# Z80_BMO_V1_2.net
KiCad netlist of a schematic drawn in EAGLE
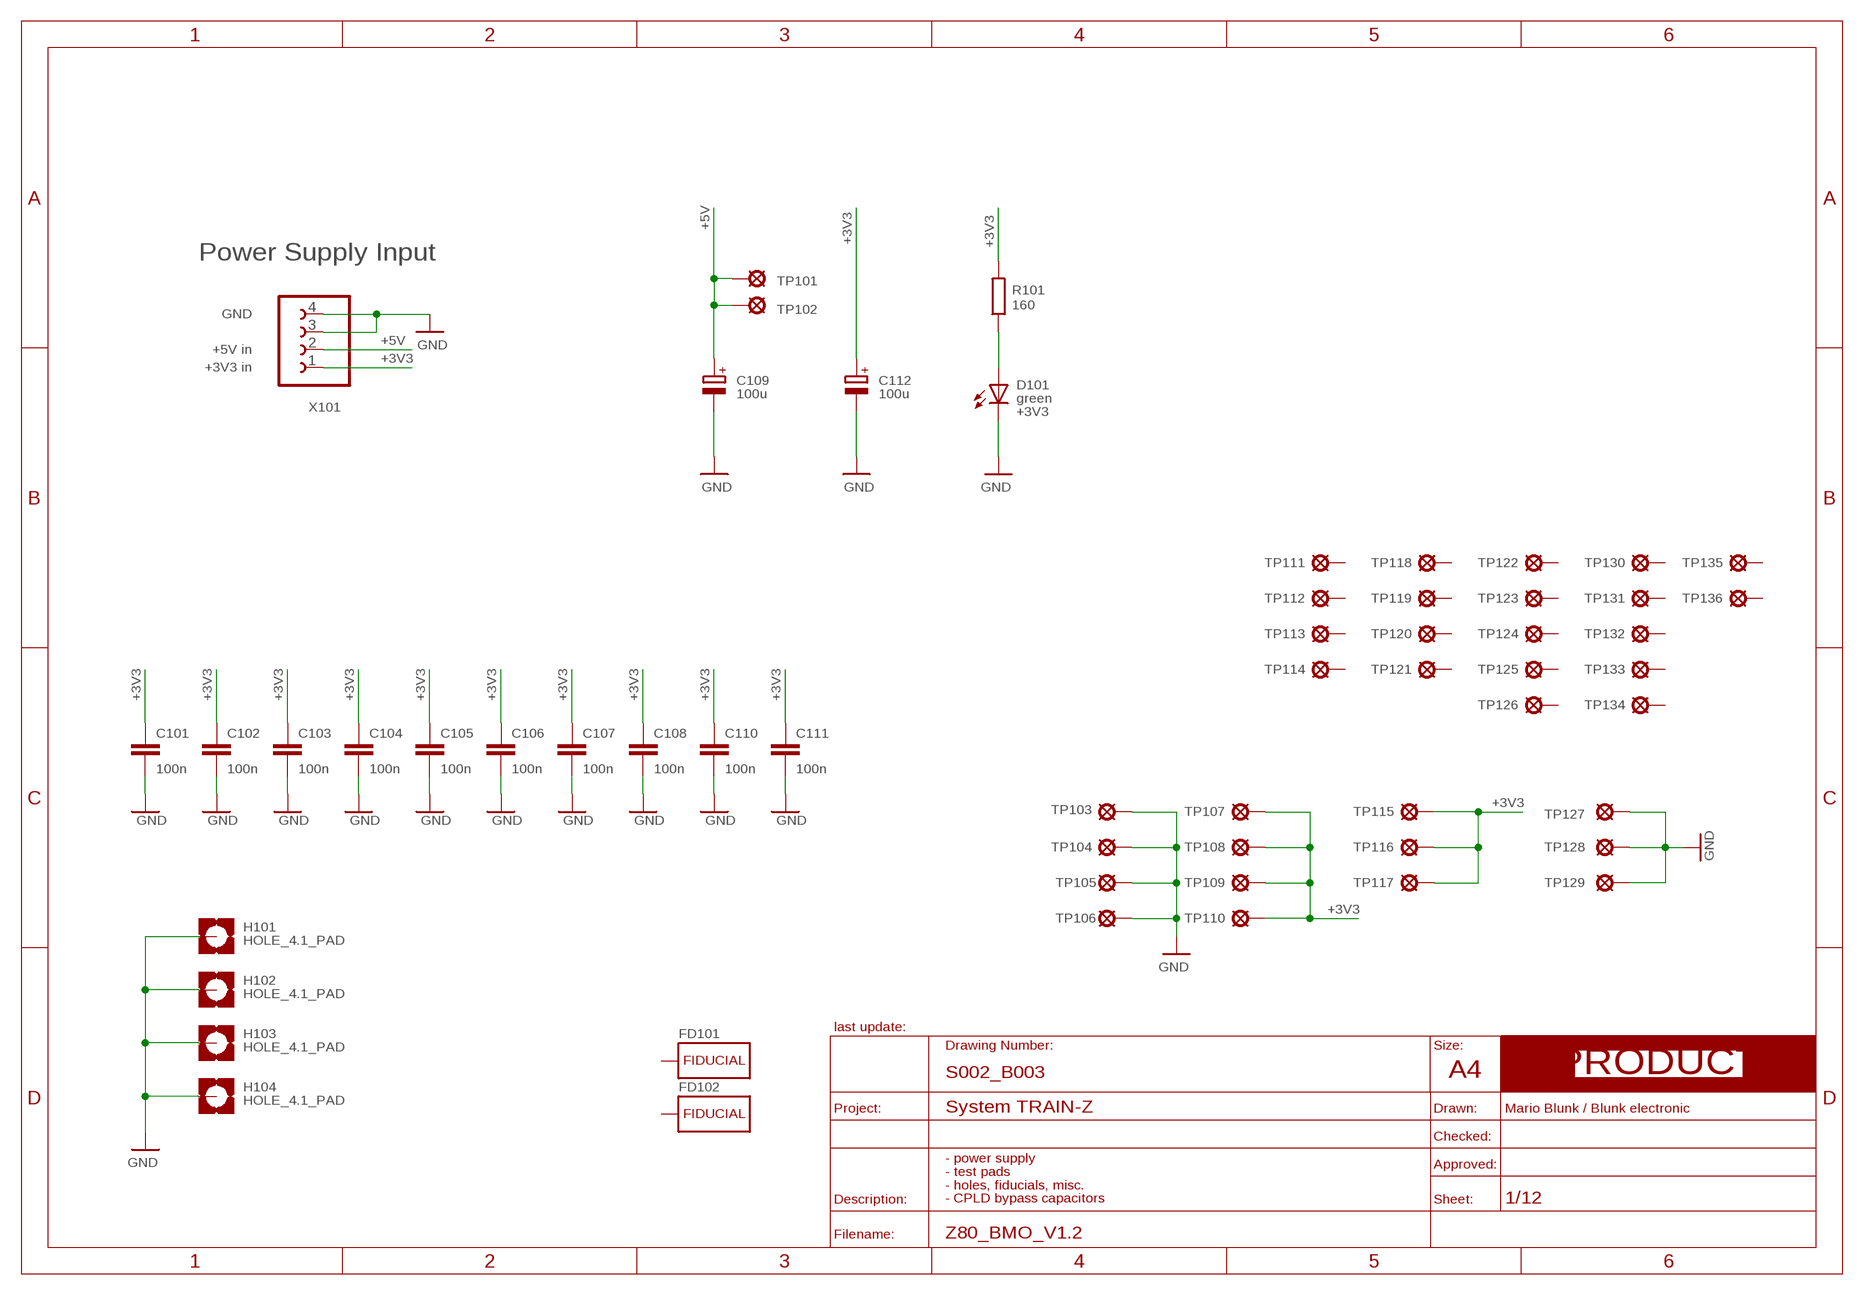
[diagram p0: schematic, sheet 1]
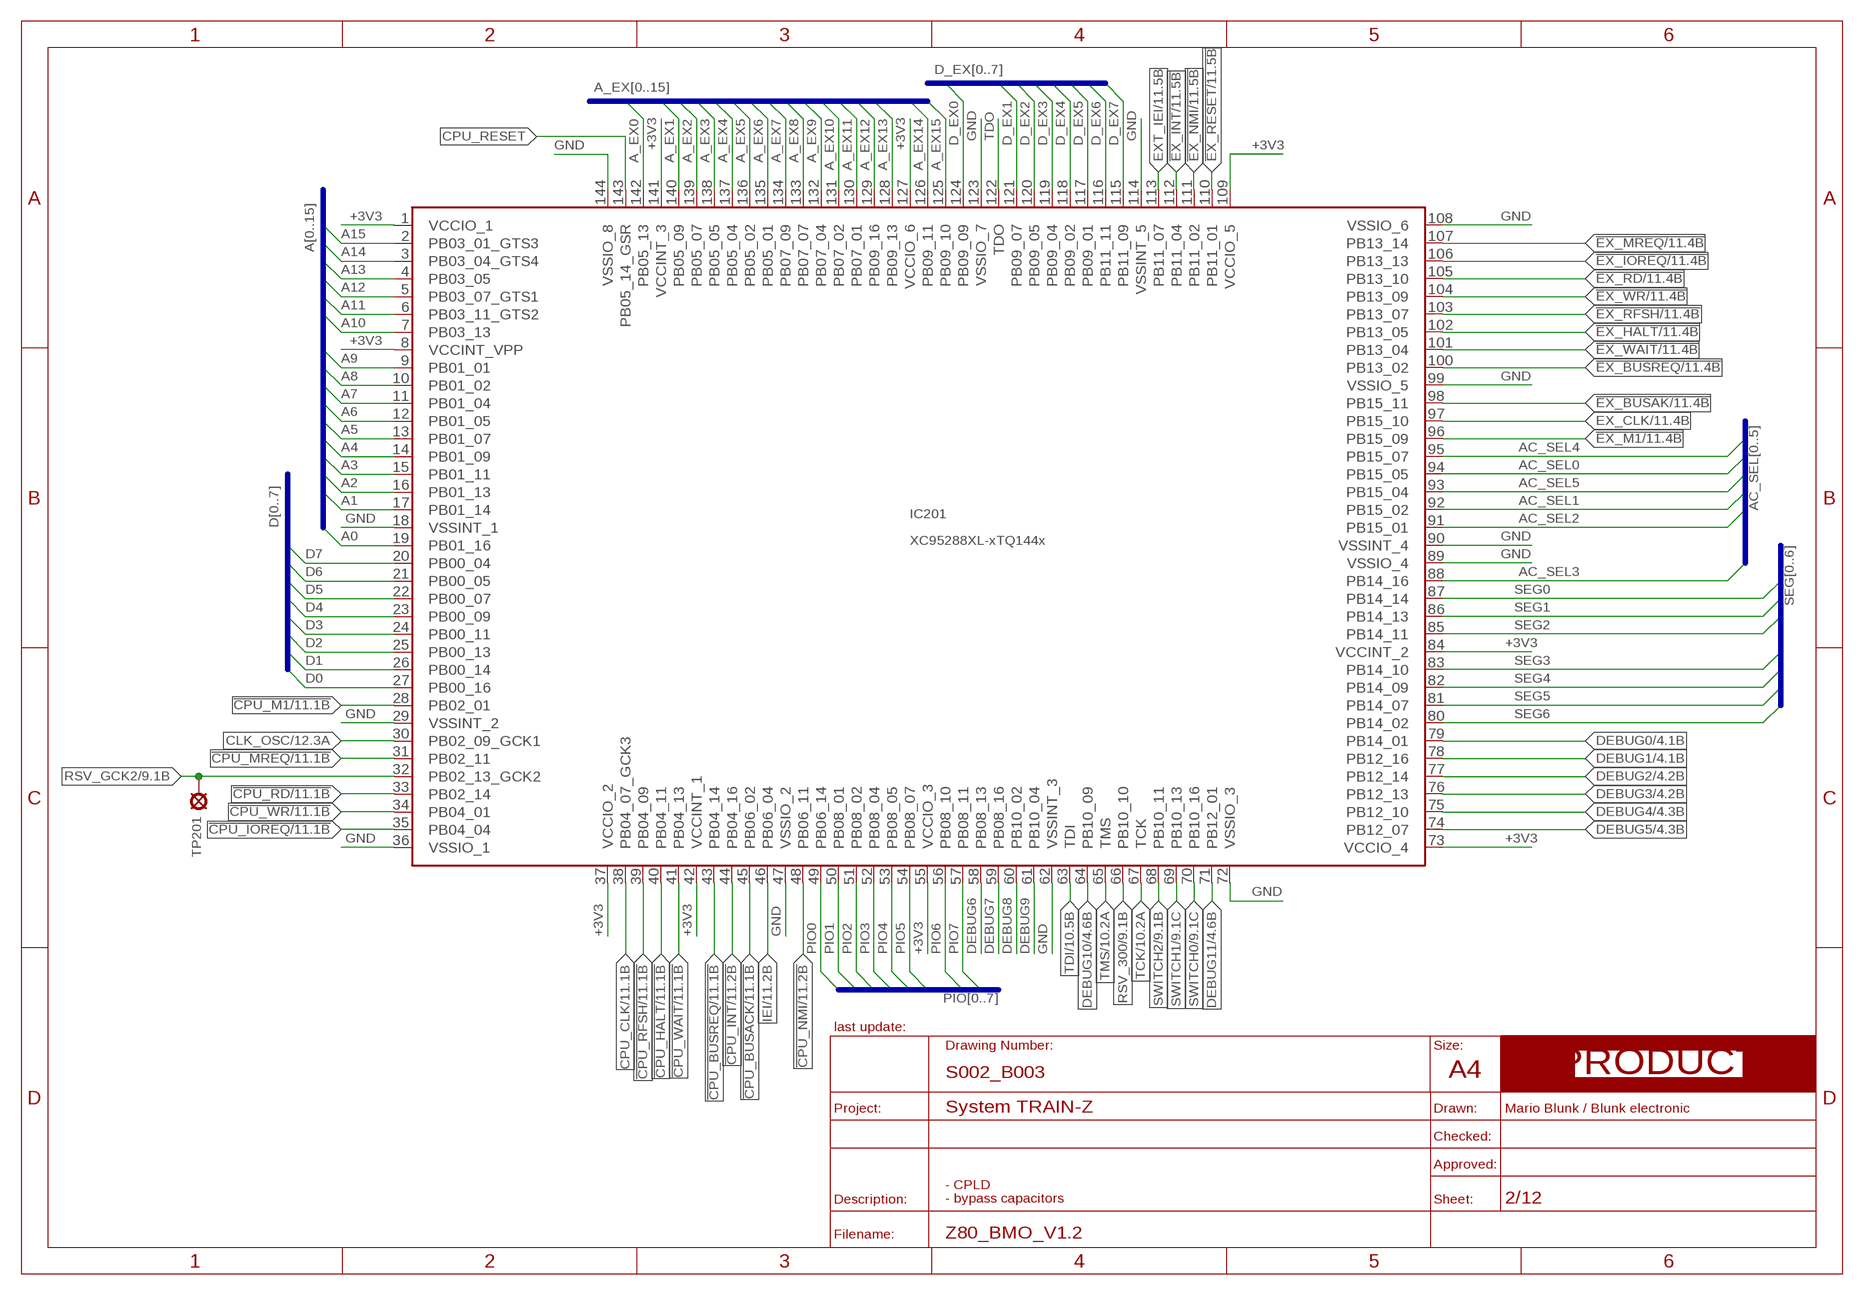
[diagram p1: schematic, sheet 2]
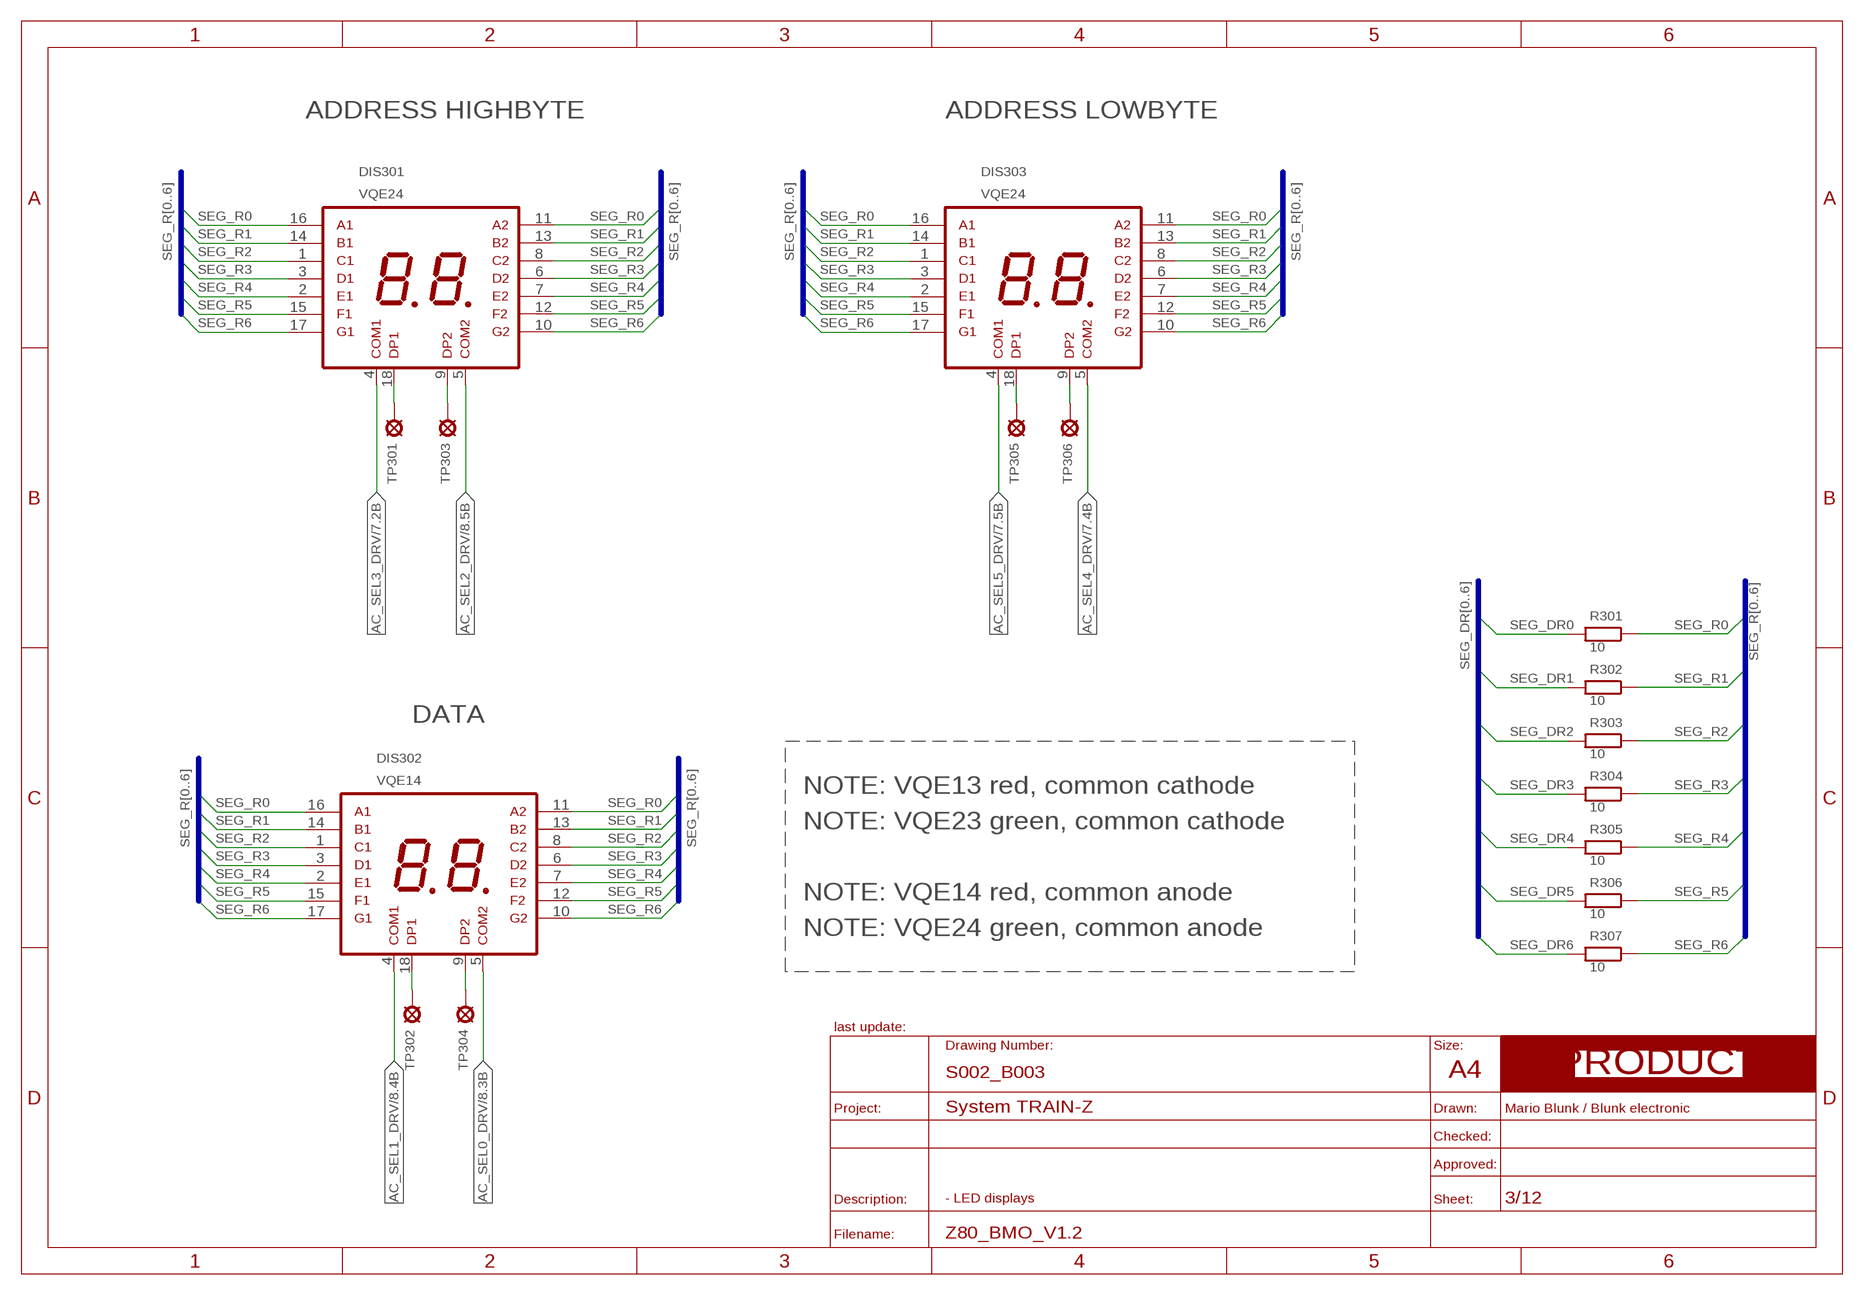
[diagram p2: schematic, sheet 3]
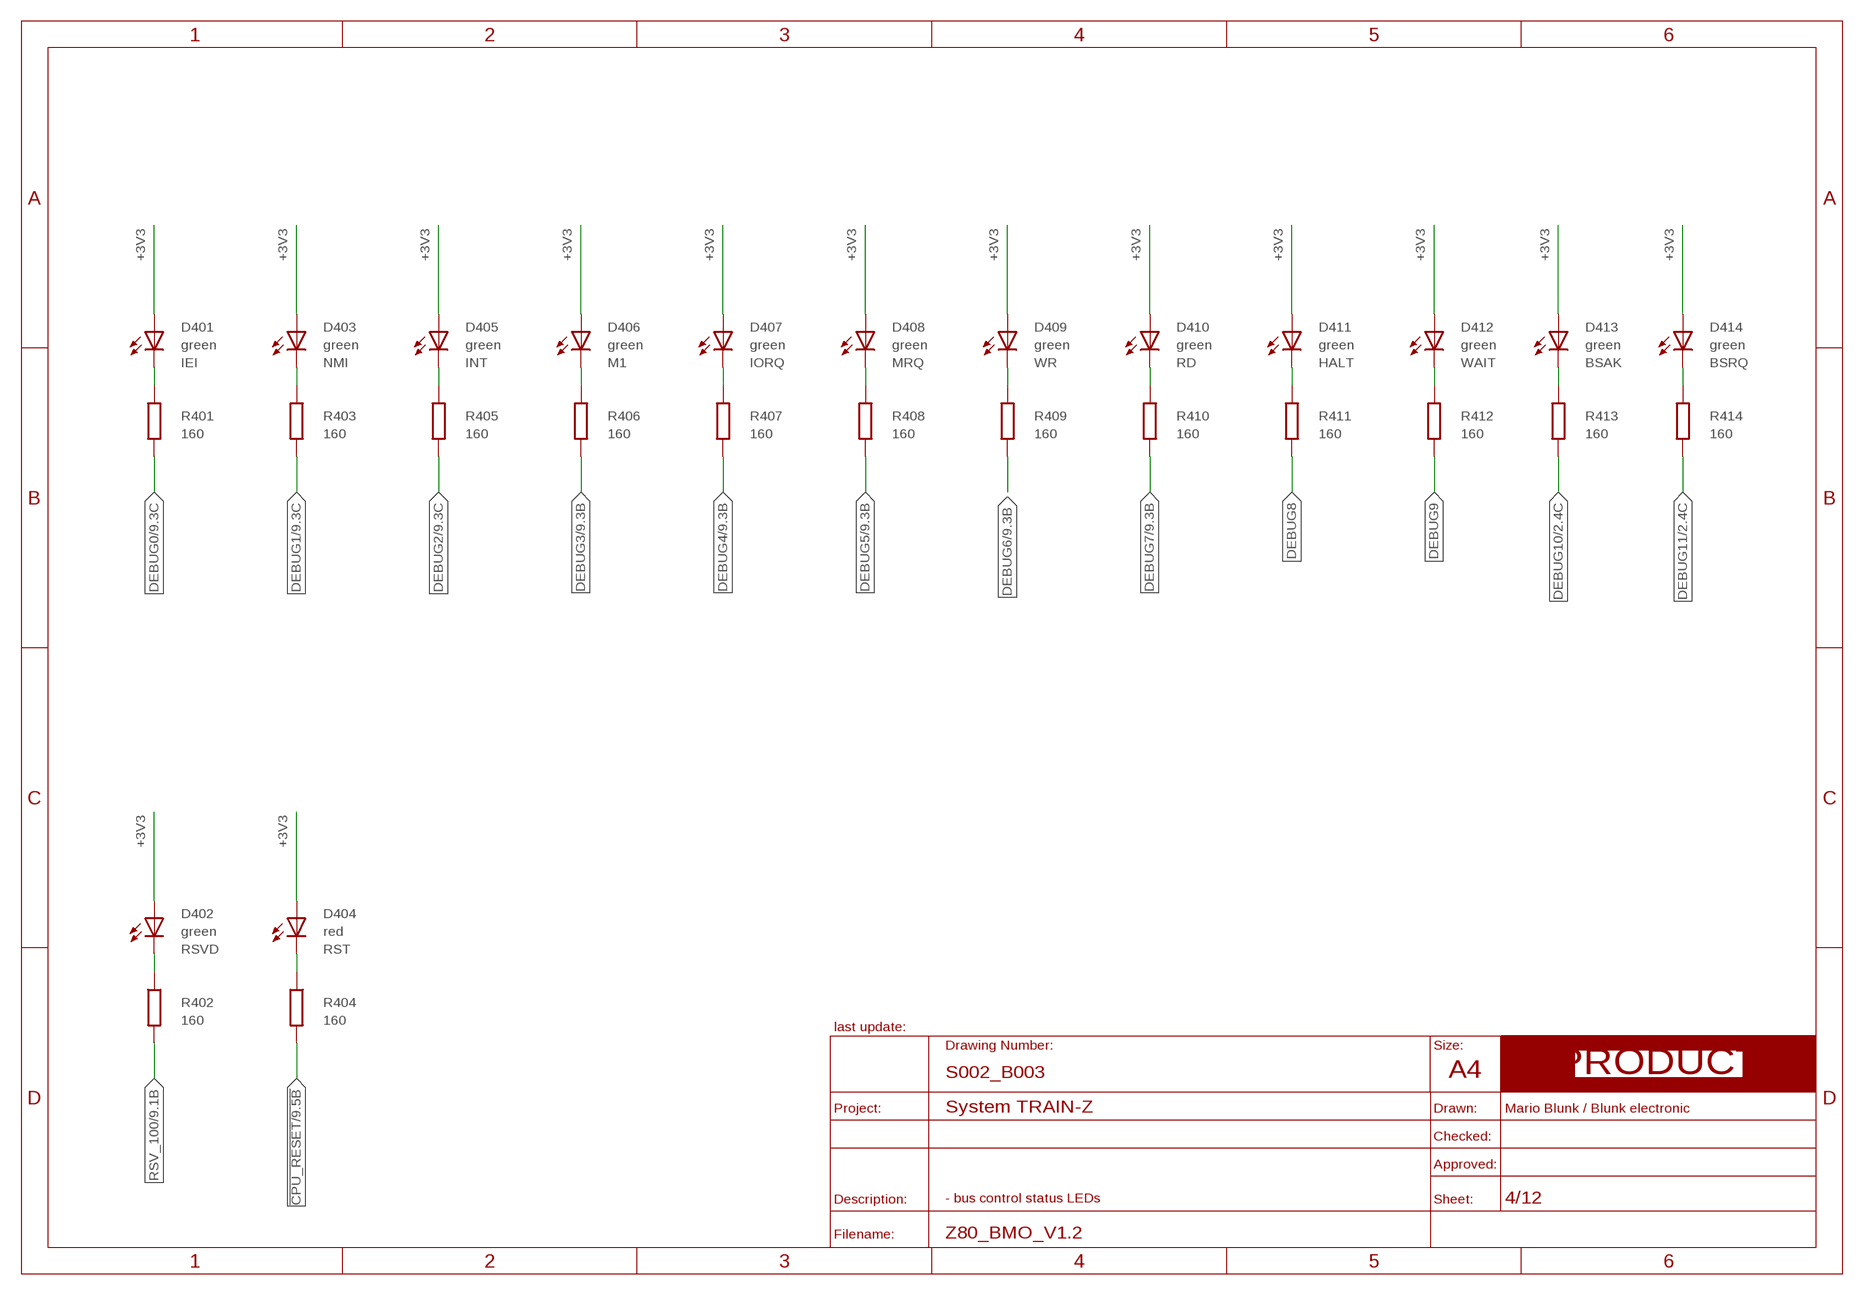
[diagram p3: schematic, sheet 4]
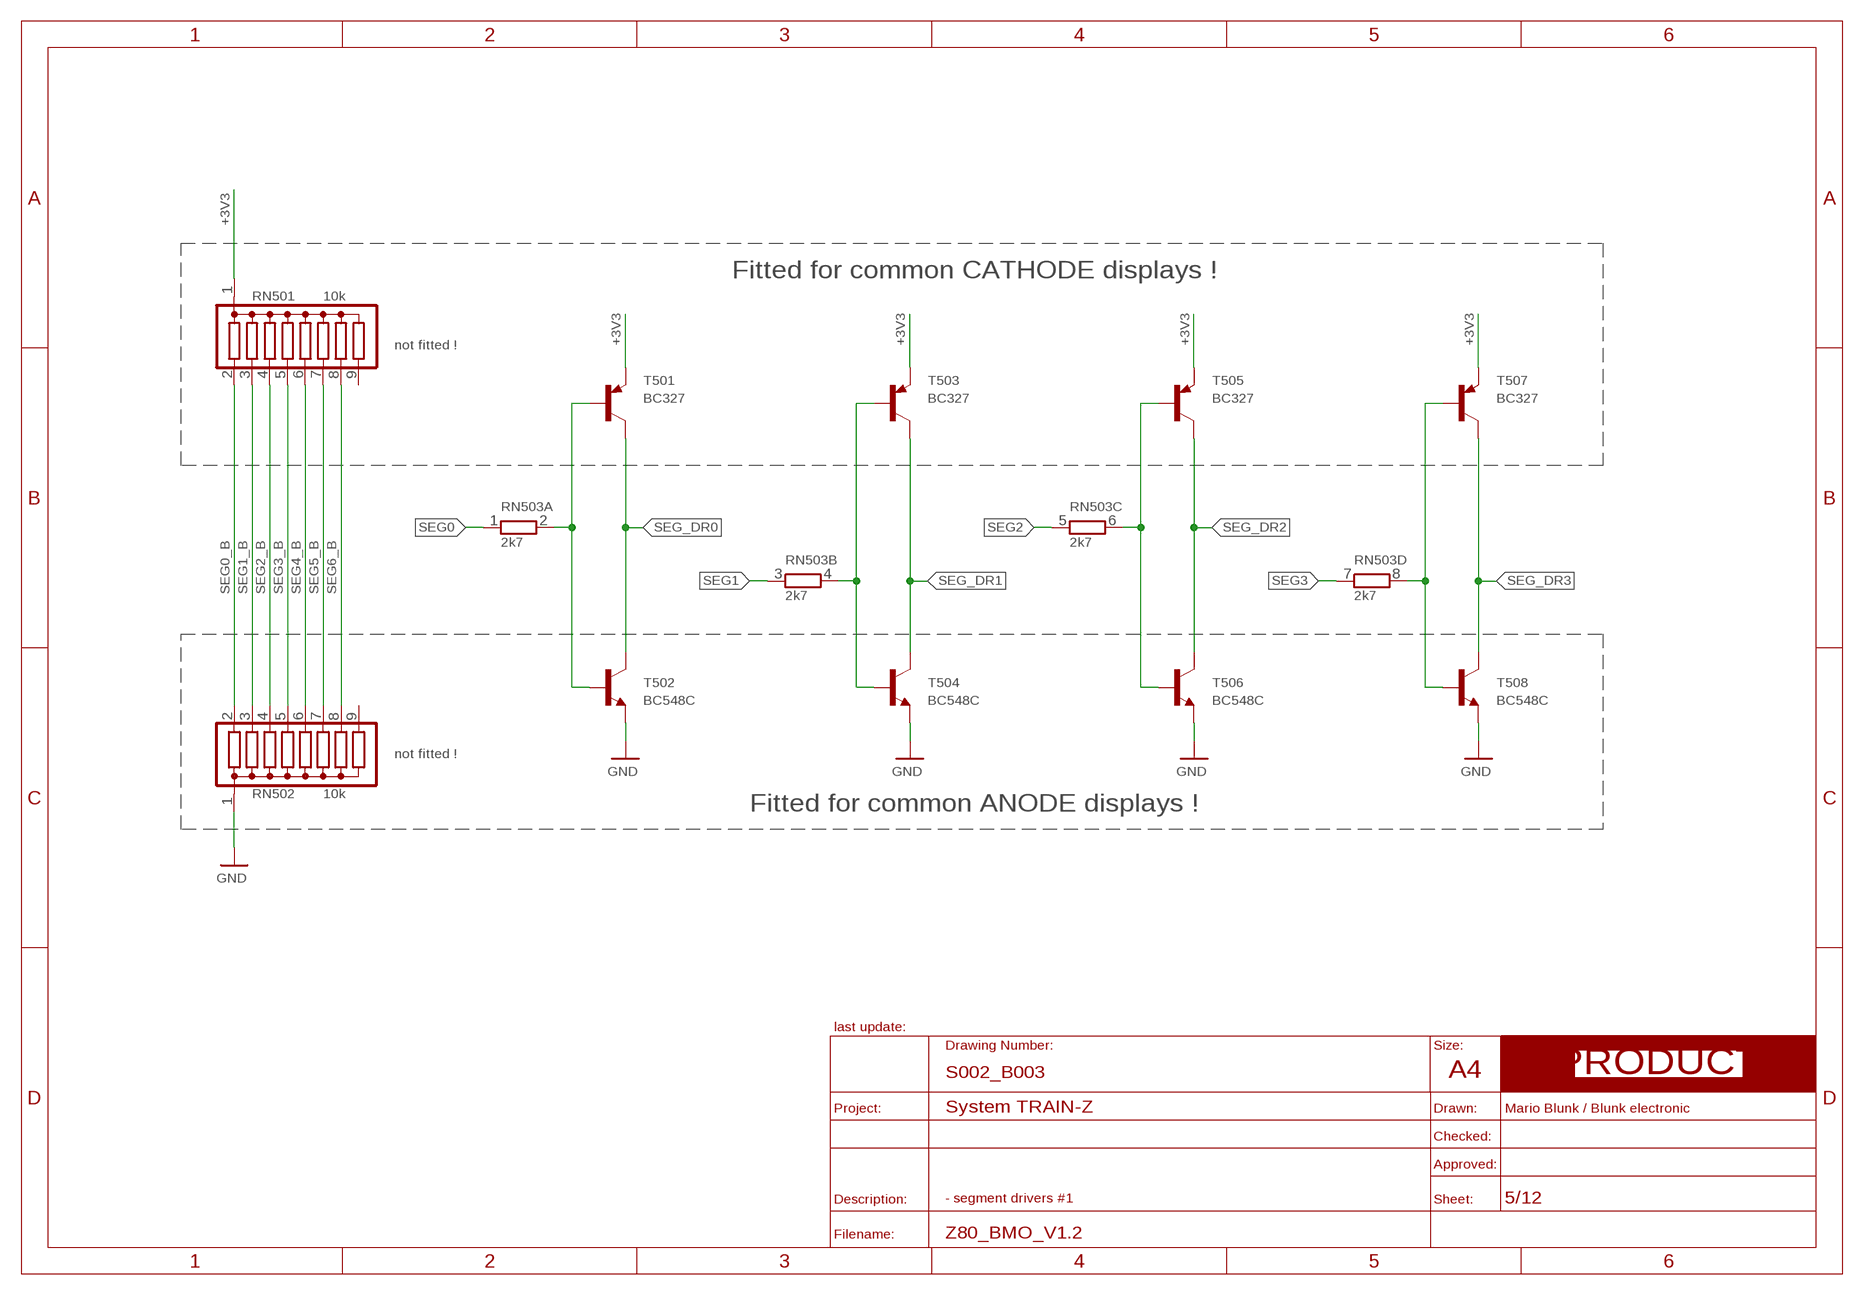
[diagram p4: schematic, sheet 5]
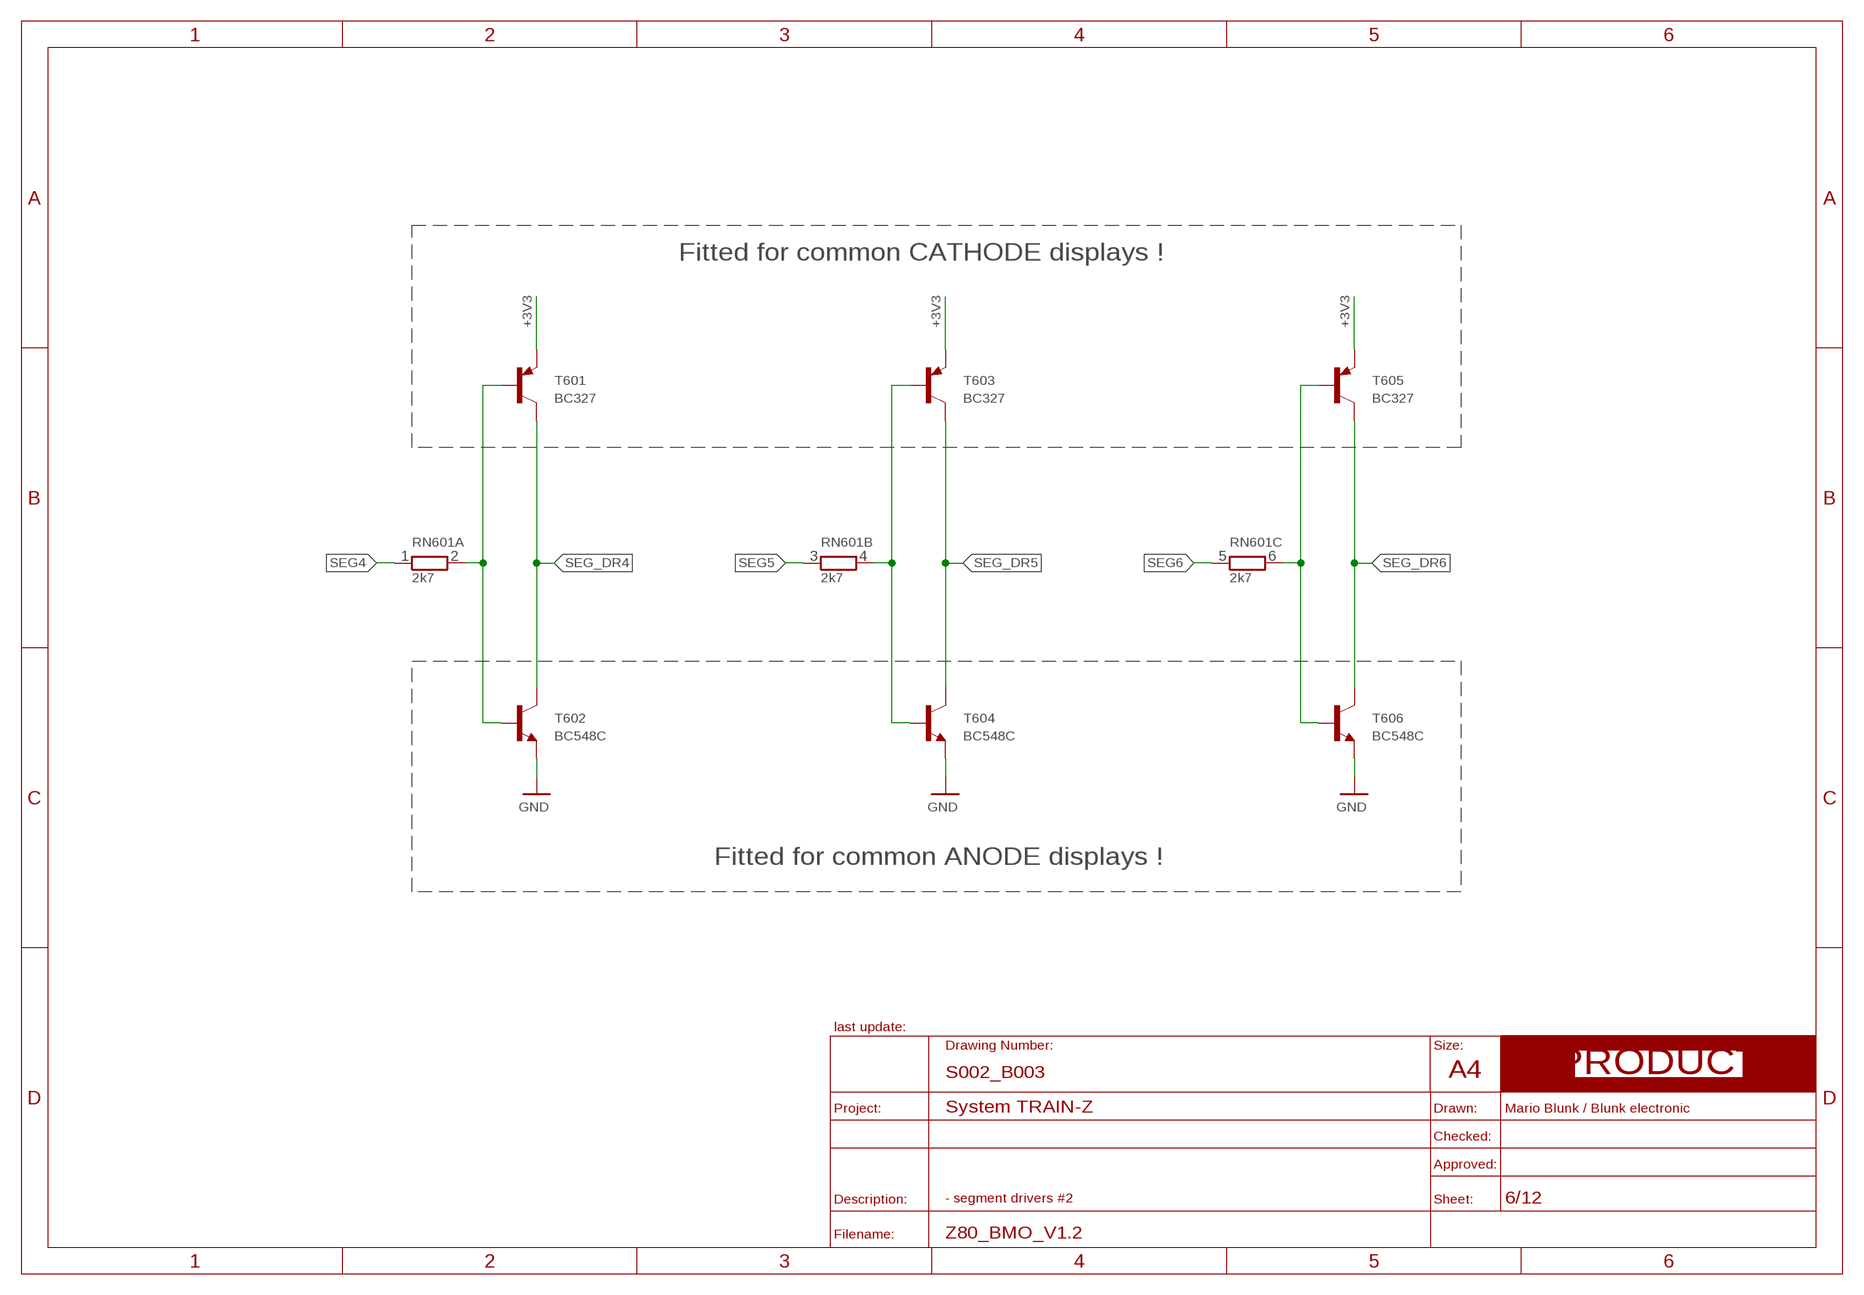
[diagram p5: schematic, sheet 6]
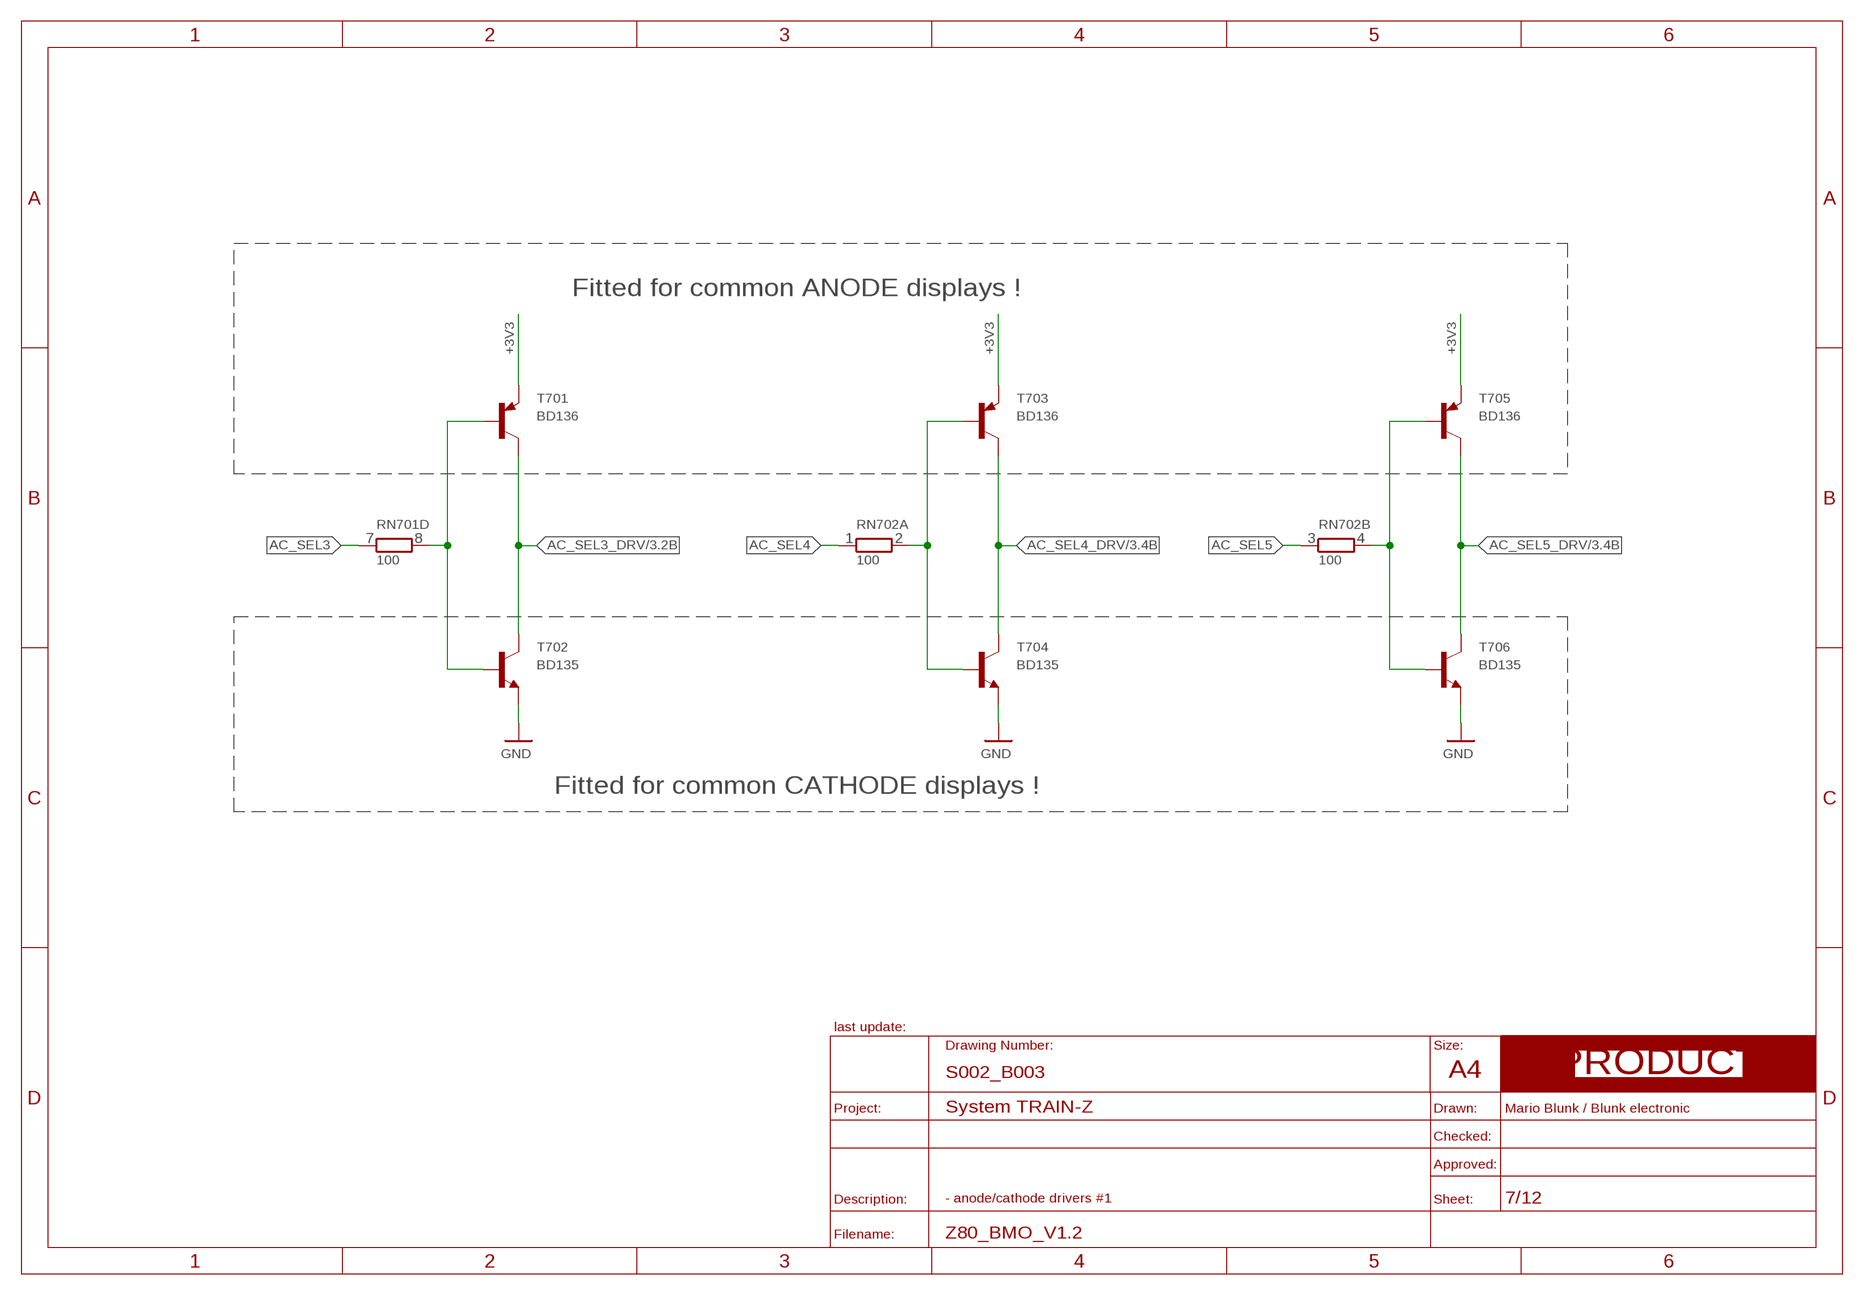
[diagram p6: schematic, sheet 7]
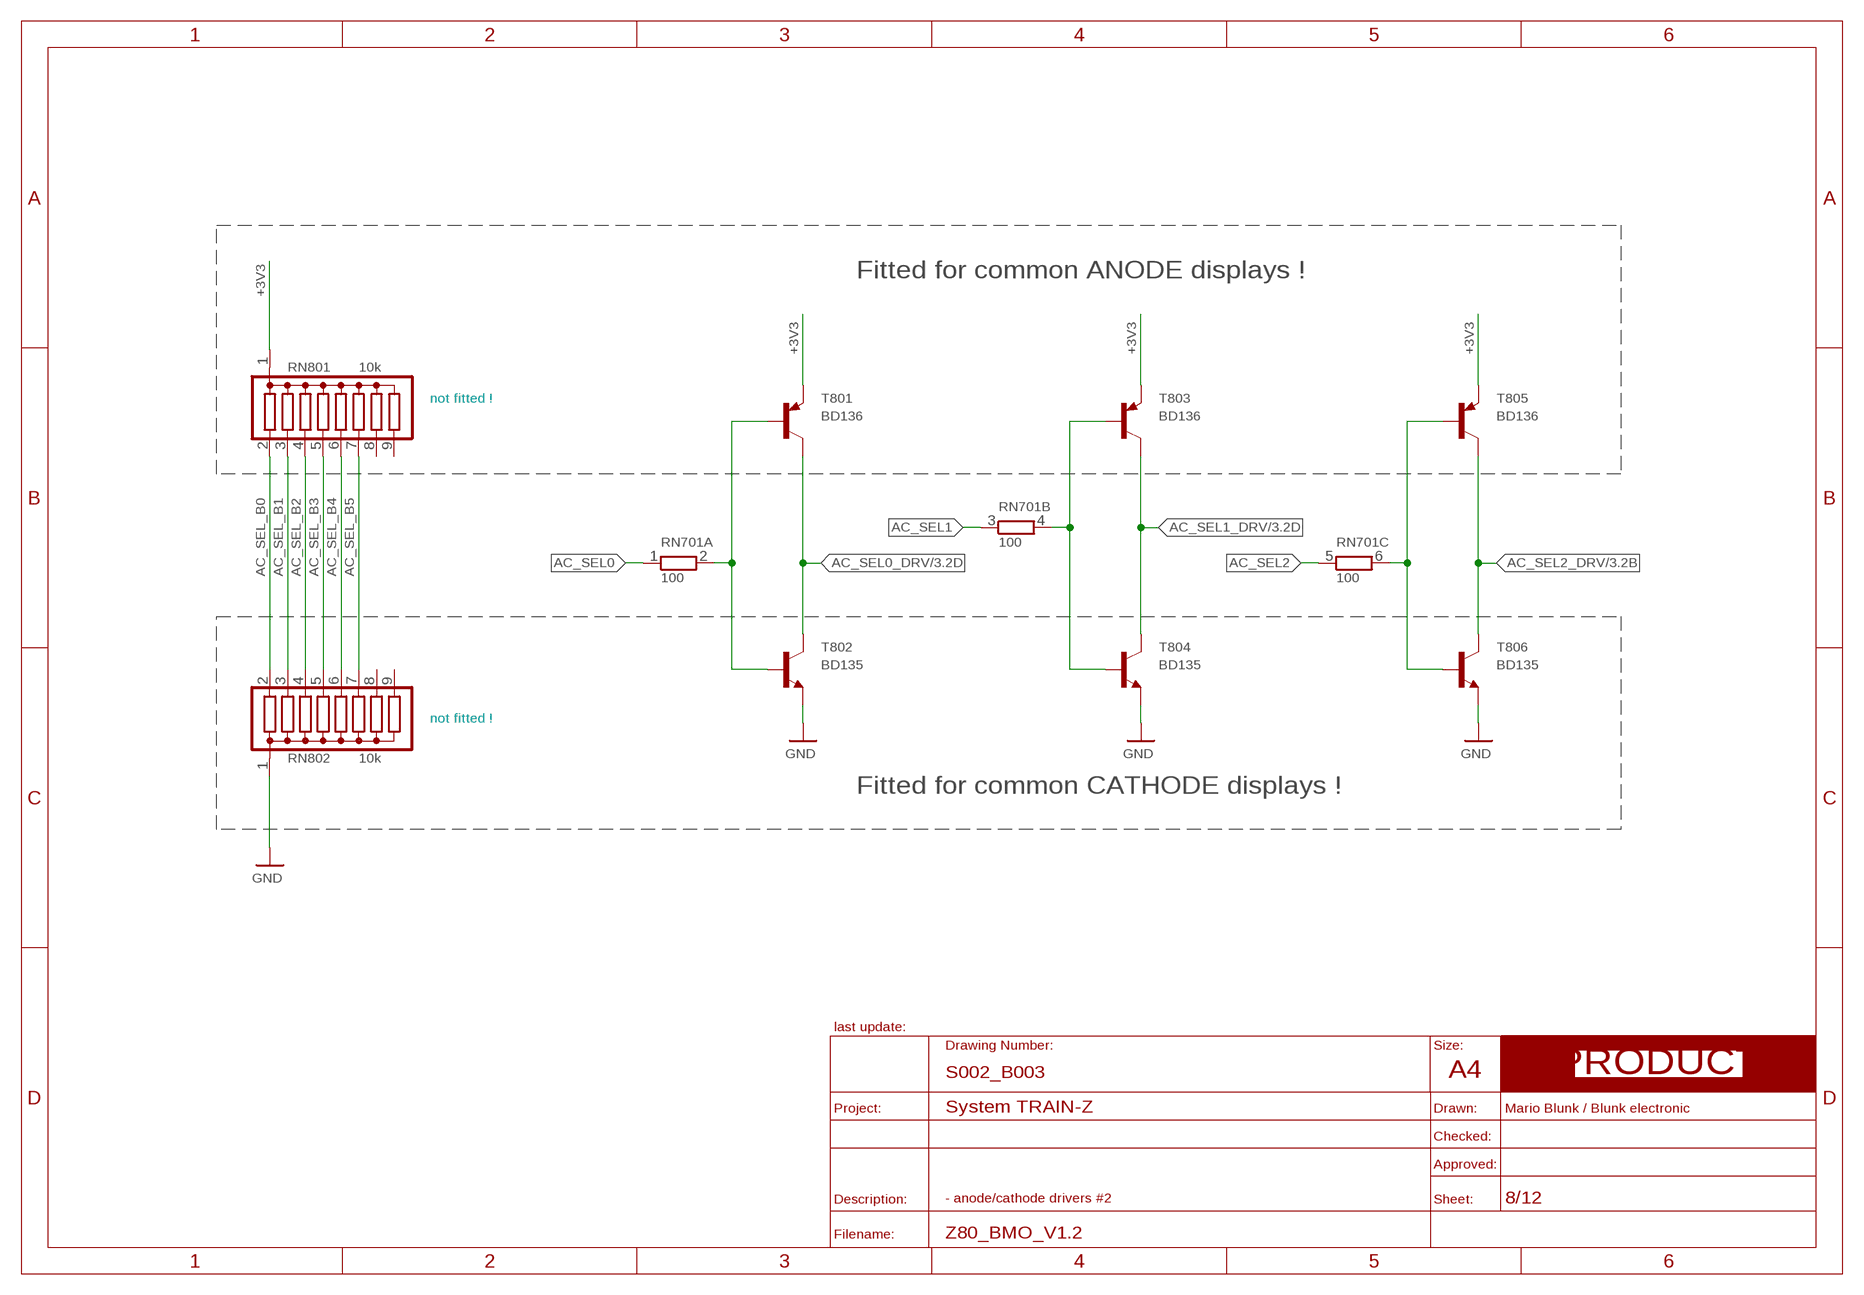
[diagram p7: schematic, sheet 8]
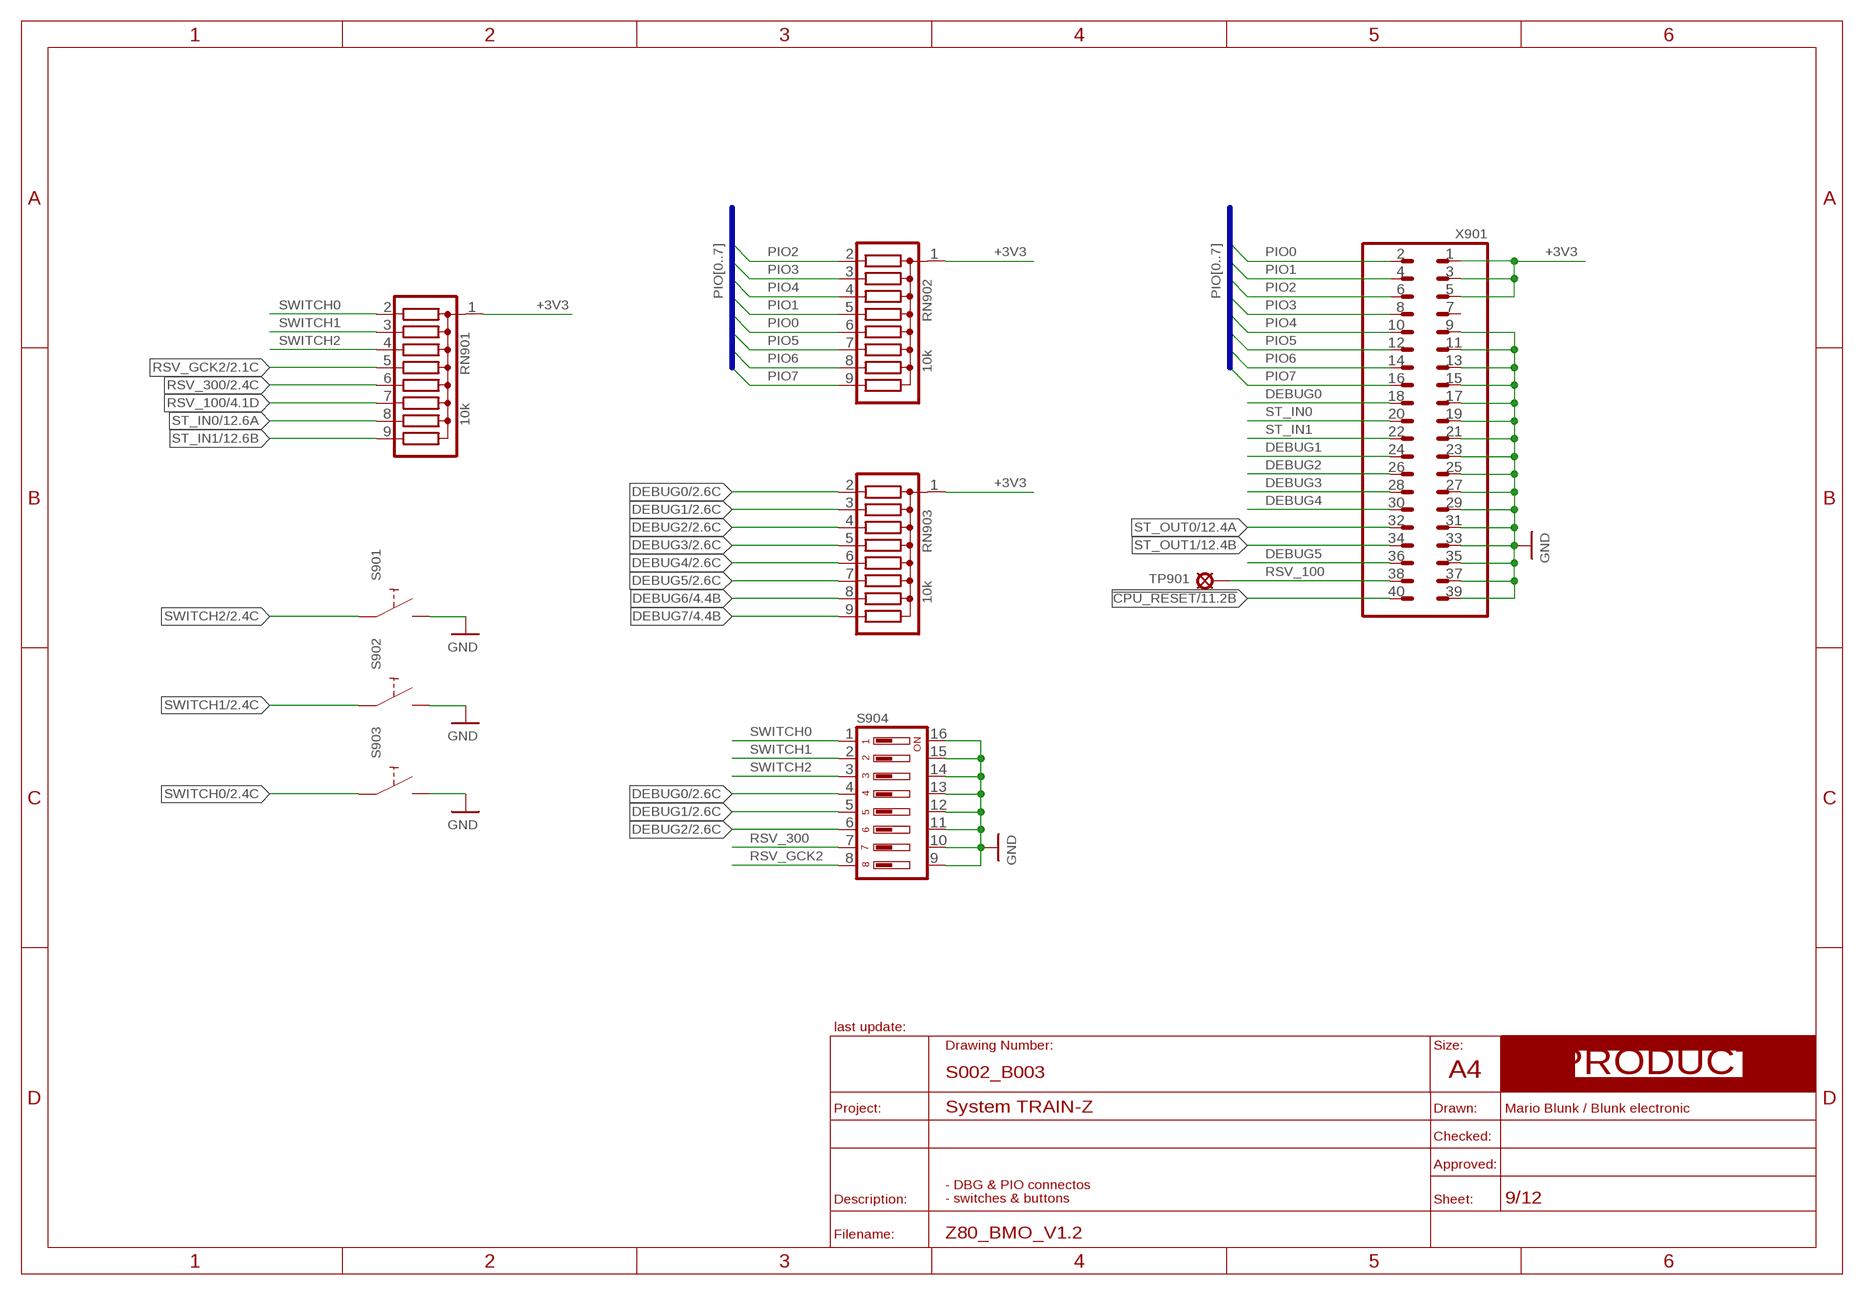
[diagram p8: schematic, sheet 9]
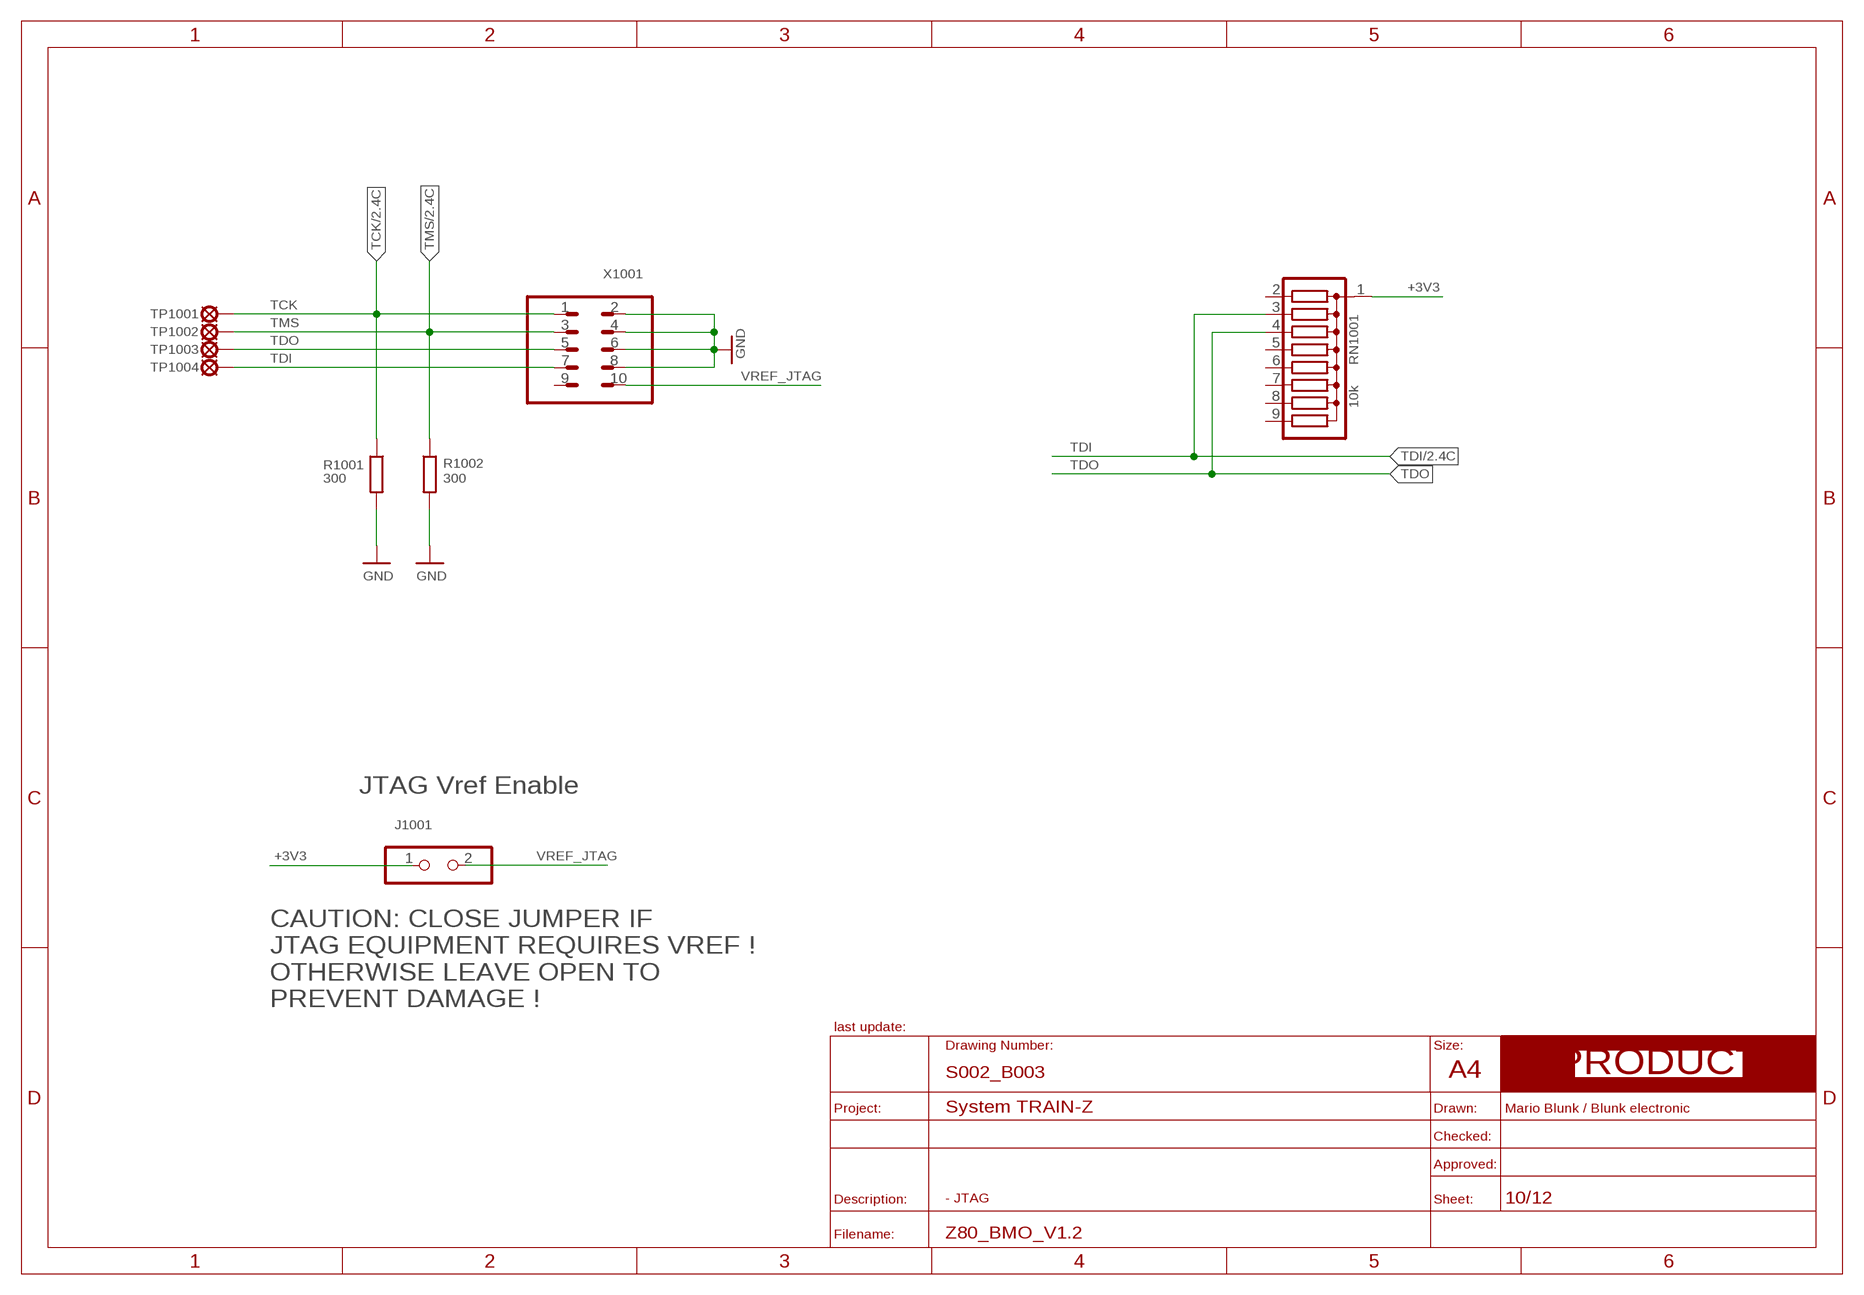
[diagram p9: schematic, sheet 10]
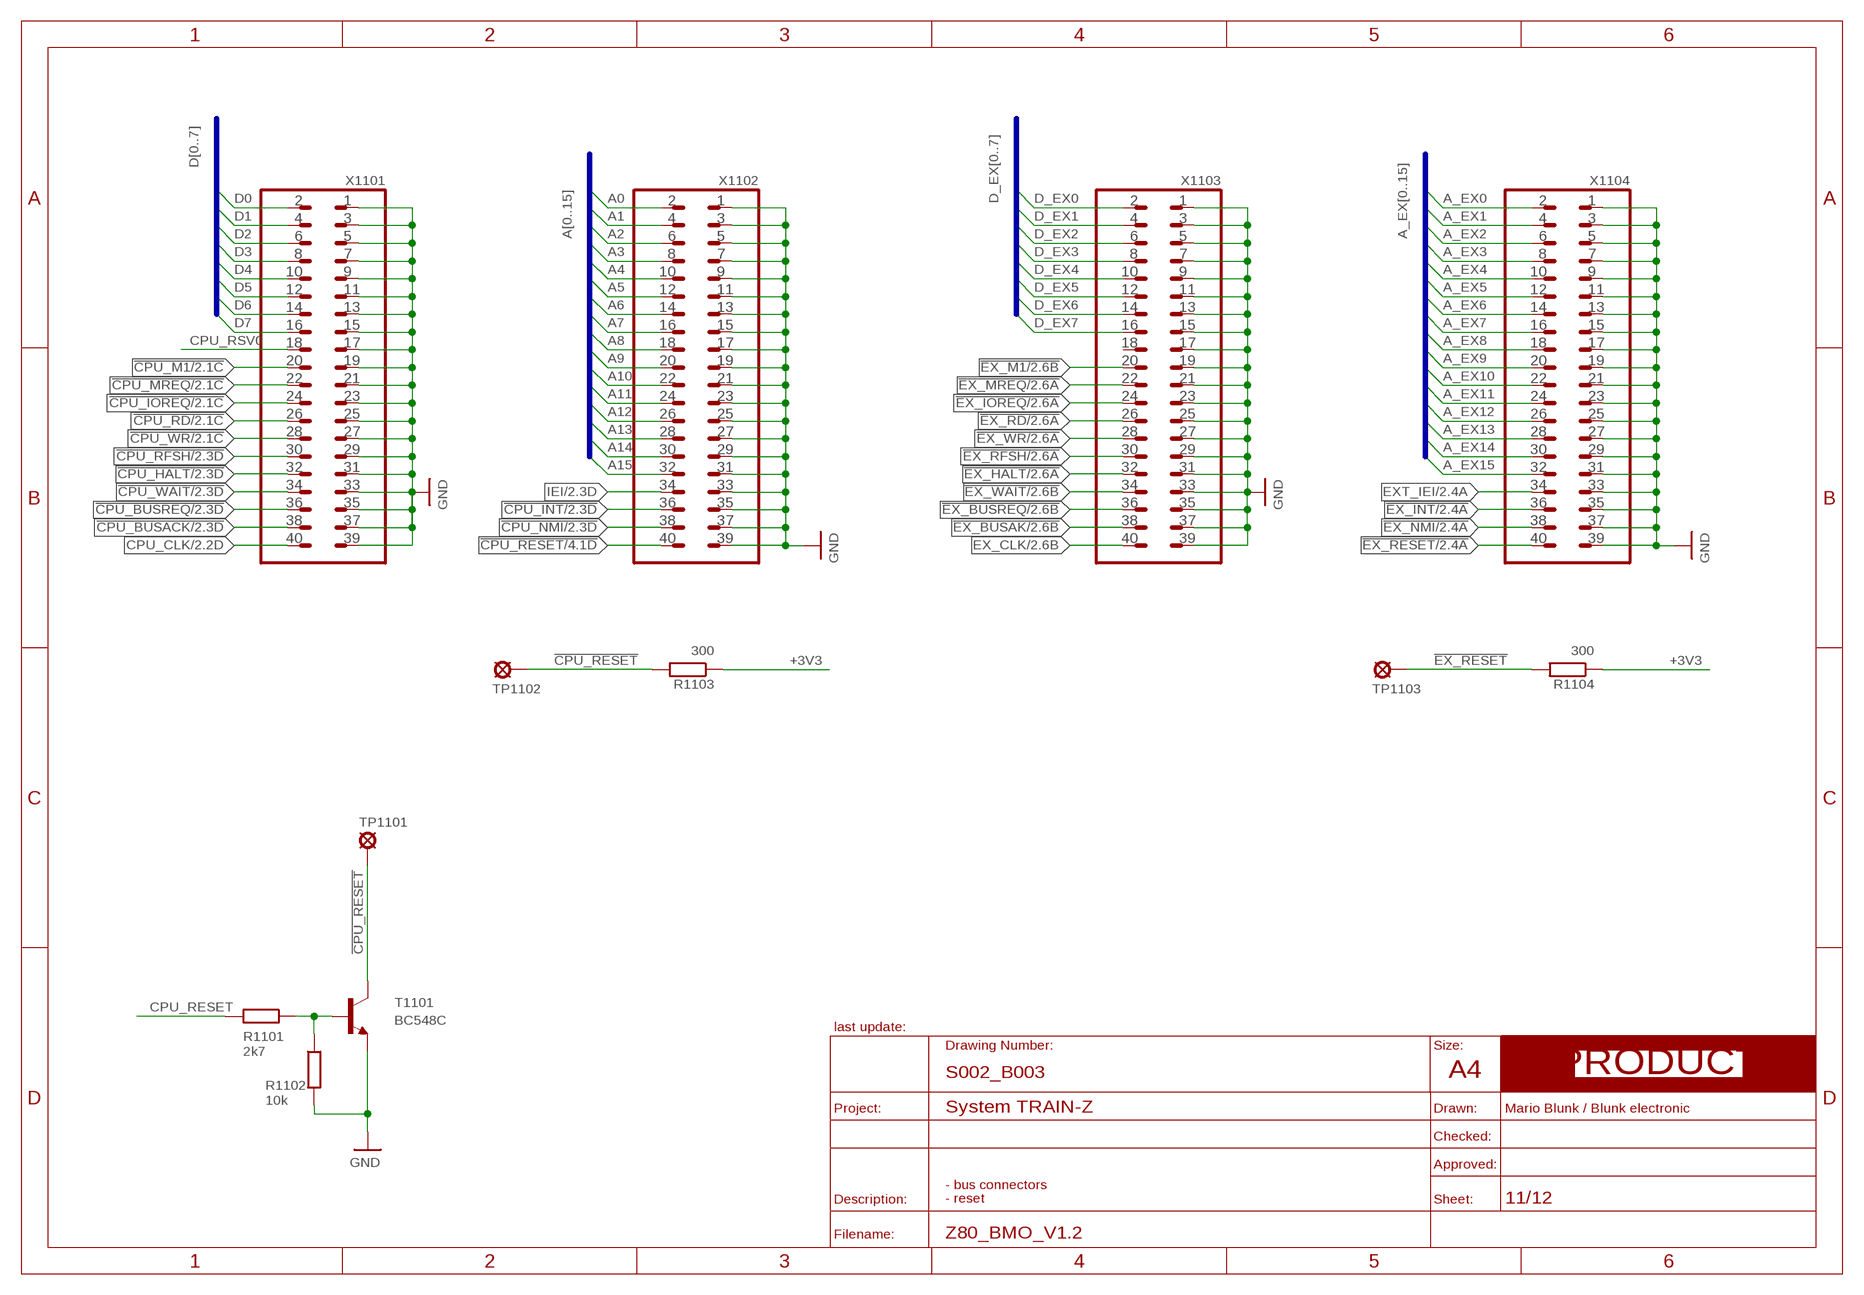
[diagram p10: schematic, sheet 11]
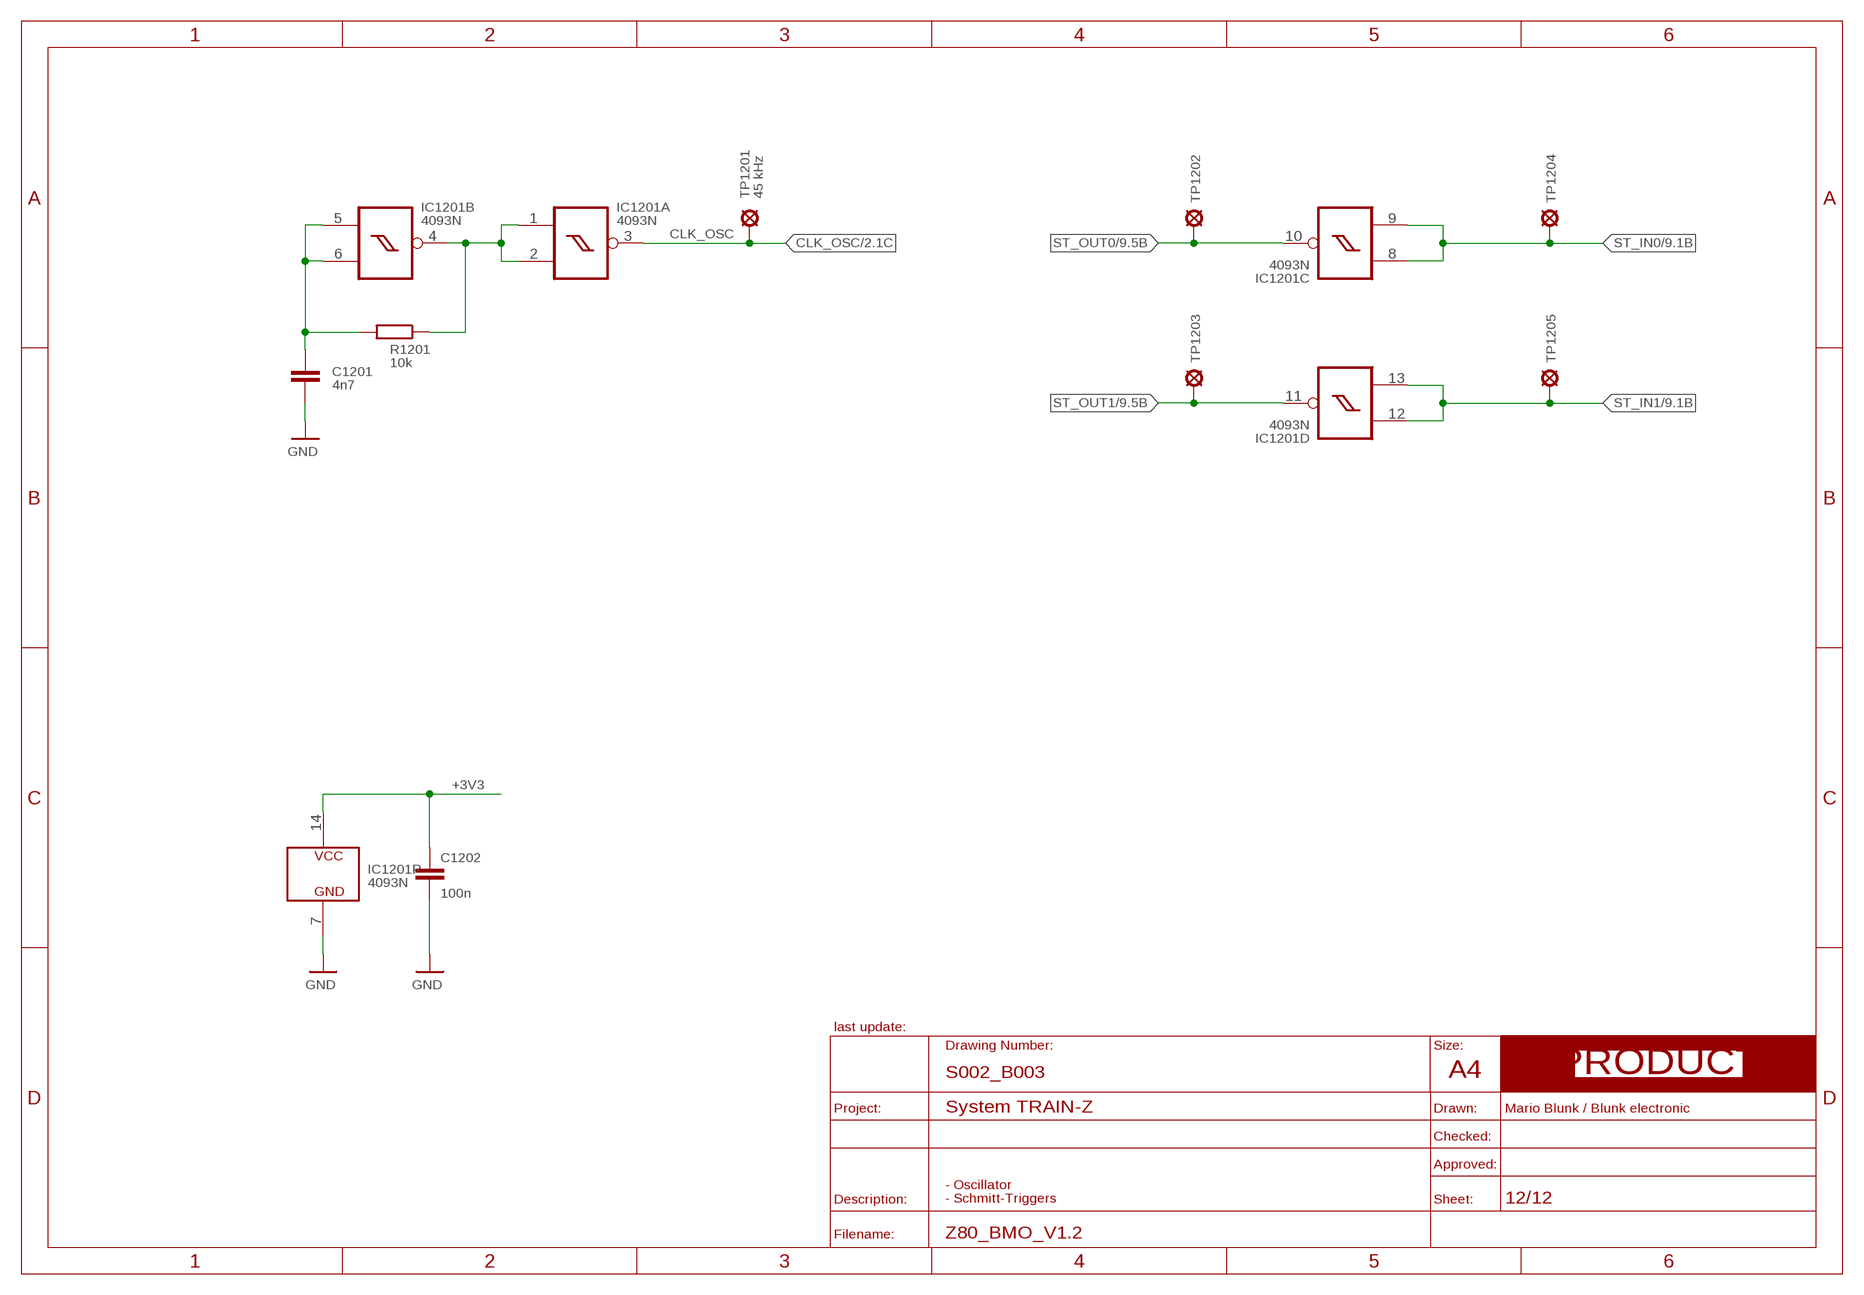
[diagram p11: schematic, sheet 12]

(export (version "E")
  (design (tool "Eeschema 10.0.6"))
  (components
    (comp (ref "RN501")
      (value "10k")
      (footprint "eagle-import:T_SIL9")
      (fields (field (name "PART_CODE_BEL") "RN_PAC_T_SIL9_VAL_10k"))
      (libsource (lib "eagle-import") (part "R_EU_ARRAY_1C_8_T_SIL9"))
    )
    (comp (ref "RN502")
      (value "10k")
      (footprint "eagle-import:T_SIL9")
      (fields (field (name "PART_CODE_BEL") "RN_PAC_T_SIL9_VAL_10k"))
      (libsource (lib "eagle-import") (part "R_EU_ARRAY_1C_8_T_SIL9"))
    )
    (comp (ref "RN503")
      (value "2k7")
      (footprint "eagle-import:T_SIL8")
      (fields (field (name "PART_CODE_BEL") "RN_PAC_T_SIL8_VAL_2k7"))
      (libsource (lib "eagle-import") (part "R_EU_ARRAY_4"))
    )
    (comp (ref "T501")
      (value "BC327")
      (footprint "eagle-import:T_TO92-CBE")
      (fields (field (name "PART_CODE_BEL") "T_PAC_T_TO92-CBE_VAL_BC327"))
      (libsource (lib "eagle-import") (part "PNP_T_TO92-CBE"))
    )
    (comp (ref "T502")
      (value "BC548C")
      (footprint "eagle-import:T_TO92-CBE")
      (fields (field (name "PART_CODE_BEL") "T_PAC_T_TO92-CBE_VAL_BC548C"))
      (libsource (lib "eagle-import") (part "NPN_T_TO92-CBE"))
    )
    (comp (ref "T503")
      (value "BC327")
      (footprint "eagle-import:T_TO92-CBE")
      (fields (field (name "PART_CODE_BEL") "T_PAC_T_TO92-CBE_VAL_BC327"))
      (libsource (lib "eagle-import") (part "PNP_T_TO92-CBE"))
    )
    (comp (ref "T504")
      (value "BC548C")
      (footprint "eagle-import:T_TO92-CBE")
      (fields (field (name "PART_CODE_BEL") "T_PAC_T_TO92-CBE_VAL_BC548C"))
      (libsource (lib "eagle-import") (part "NPN_T_TO92-CBE"))
    )
    (comp (ref "T505")
      (value "BC327")
      (footprint "eagle-import:T_TO92-CBE")
      (fields (field (name "PART_CODE_BEL") "T_PAC_T_TO92-CBE_VAL_BC327"))
      (libsource (lib "eagle-import") (part "PNP_T_TO92-CBE"))
    )
    (comp (ref "T506")
      (value "BC548C")
      (footprint "eagle-import:T_TO92-CBE")
      (fields (field (name "PART_CODE_BEL") "T_PAC_T_TO92-CBE_VAL_BC548C"))
      (libsource (lib "eagle-import") (part "NPN_T_TO92-CBE"))
    )
    (comp (ref "T507")
      (value "BC327")
      (footprint "eagle-import:T_TO92-CBE")
      (fields (field (name "PART_CODE_BEL") "T_PAC_T_TO92-CBE_VAL_BC327"))
      (libsource (lib "eagle-import") (part "PNP_T_TO92-CBE"))
    )
    (comp (ref "T508")
      (value "BC548C")
      (footprint "eagle-import:T_TO92-CBE")
      (fields (field (name "PART_CODE_BEL") "T_PAC_T_TO92-CBE_VAL_BC548C"))
      (libsource (lib "eagle-import") (part "NPN_T_TO92-CBE"))
    )
    (comp (ref "C101")
      (value "100n")
      (footprint "eagle-import:S_0805")
      (fields (field (name "PART_CODE_BEL") "C_PAC_S_0805_VAL_100n"))
      (libsource (lib "eagle-import") (part "C_EU_S_0805"))
    )
    (comp (ref "C102")
      (value "100n")
      (footprint "eagle-import:S_0805")
      (fields (field (name "PART_CODE_BEL") "C_PAC_S_0805_VAL_100n"))
      (libsource (lib "eagle-import") (part "C_EU_S_0805"))
    )
    (comp (ref "C103")
      (value "100n")
      (footprint "eagle-import:S_0805")
      (fields (field (name "PART_CODE_BEL") "C_PAC_S_0805_VAL_100n"))
      (libsource (lib "eagle-import") (part "C_EU_S_0805"))
    )
    (comp (ref "C104")
      (value "100n")
      (footprint "eagle-import:S_0805")
      (fields (field (name "PART_CODE_BEL") "C_PAC_S_0805_VAL_100n"))
      (libsource (lib "eagle-import") (part "C_EU_S_0805"))
    )
    (comp (ref "C105")
      (value "100n")
      (footprint "eagle-import:S_0805")
      (fields (field (name "PART_CODE_BEL") "C_PAC_S_0805_VAL_100n"))
      (libsource (lib "eagle-import") (part "C_EU_S_0805"))
    )
    (comp (ref "C106")
      (value "100n")
      (footprint "eagle-import:S_0805")
      (fields (field (name "PART_CODE_BEL") "C_PAC_S_0805_VAL_100n"))
      (libsource (lib "eagle-import") (part "C_EU_S_0805"))
    )
    (comp (ref "C107")
      (value "100n")
      (footprint "eagle-import:S_0805")
      (fields (field (name "PART_CODE_BEL") "C_PAC_S_0805_VAL_100n"))
      (libsource (lib "eagle-import") (part "C_EU_S_0805"))
    )
    (comp (ref "C108")
      (value "100n")
      (footprint "eagle-import:S_0805")
      (fields (field (name "PART_CODE_BEL") "C_PAC_S_0805_VAL_100n"))
      (libsource (lib "eagle-import") (part "C_EU_S_0805"))
    )
    (comp (ref "C109")
      (value "100u")
      (footprint "eagle-import:T_RADIAL_7MM_GRID_2.54MM")
      (fields (field (name "PART_CODE_BEL") "C_PAC_T_RADIAL_7mm_GRID_2.54mm_VAL_100u_Vmax_35V"))
      (libsource (lib "eagle-import") (part "C_POL_EU_T_RAD7_GR2.54"))
    )
    (comp (ref "C110")
      (value "100n")
      (footprint "eagle-import:S_0805")
      (fields (field (name "PART_CODE_BEL") "C_PAC_S_0805_VAL_100n"))
      (libsource (lib "eagle-import") (part "C_EU_S_0805"))
    )
    (comp (ref "C111")
      (value "100n")
      (footprint "eagle-import:S_0805")
      (fields (field (name "PART_CODE_BEL") "C_PAC_S_0805_VAL_100n"))
      (libsource (lib "eagle-import") (part "C_EU_S_0805"))
    )
    (comp (ref "C112")
      (value "100u")
      (footprint "eagle-import:T_RADIAL_7MM_GRID_2.54MM")
      (fields (field (name "PART_CODE_BEL") "C_PAC_T_RADIAL_7mm_GRID_2.54mm_VAL_100u_Vmax_35V"))
      (libsource (lib "eagle-import") (part "C_POL_EU_T_RAD7_GR2.54"))
    )
    (comp (ref "D101")
      (value "green")
      (footprint "eagle-import:T_LED_3MM")
      (fields (field (name "FUNCTION") "+3V3") (field (name "PART_CODE_BEL") "LED_PAC_T_3mm_VAL_green"))
      (libsource (lib "eagle-import") (part "LED_T_3MM"))
    )
    (comp (ref "FD101")
      (value "FIDUCIAL_CROSSHAIR")
      (footprint "eagle-import:CROSSHAIR")
      (libsource (lib "eagle-import") (part "FIDUCIAL_CROSSHAIR"))
    )
    (comp (ref "FD102")
      (value "FIDUCIAL_CROSSHAIR")
      (footprint "eagle-import:CROSSHAIR")
      (libsource (lib "eagle-import") (part "FIDUCIAL_CROSSHAIR"))
    )
    (comp (ref "H101")
      (value "HOLE_4.1_PAD")
      (footprint "eagle-import:4.1_PAD")
      (libsource (lib "eagle-import") (part "HOLE_4.1_PAD"))
    )
    (comp (ref "H102")
      (value "HOLE_4.1_PAD")
      (footprint "eagle-import:4.1_PAD")
      (libsource (lib "eagle-import") (part "HOLE_4.1_PAD"))
    )
    (comp (ref "H103")
      (value "HOLE_4.1_PAD")
      (footprint "eagle-import:4.1_PAD")
      (libsource (lib "eagle-import") (part "HOLE_4.1_PAD"))
    )
    (comp (ref "H104")
      (value "HOLE_4.1_PAD")
      (footprint "eagle-import:4.1_PAD")
      (libsource (lib "eagle-import") (part "HOLE_4.1_PAD"))
    )
    (comp (ref "R101")
      (value "160")
      (footprint "eagle-import:T_0207_GRID10MM")
      (fields (field (name "PART_CODE_BEL") "R_PAC_T_0207_GRID10mm_VAL_160"))
      (libsource (lib "eagle-import") (part "R_EU_T_0207_GRID10MM"))
    )
    (comp (ref "TP101")
      (value "TEST_POINT_T_SMALL")
      (footprint "eagle-import:T_TEST_POINT_SMALL")
      (libsource (lib "eagle-import") (part "TEST_POINT_T_SMALL"))
    )
    (comp (ref "TP102")
      (value "TEST_POINT_T_SMALL")
      (footprint "eagle-import:T_TEST_POINT_SMALL")
      (libsource (lib "eagle-import") (part "TEST_POINT_T_SMALL"))
    )
    (comp (ref "TP103")
      (value "TEST_POINT_T_SMALL")
      (footprint "eagle-import:T_TEST_POINT_SMALL")
      (libsource (lib "eagle-import") (part "TEST_POINT_T_SMALL"))
    )
    (comp (ref "TP104")
      (value "TEST_POINT_T_SMALL")
      (footprint "eagle-import:T_TEST_POINT_SMALL")
      (libsource (lib "eagle-import") (part "TEST_POINT_T_SMALL"))
    )
    (comp (ref "TP105")
      (value "TEST_POINT_T_SMALL")
      (footprint "eagle-import:T_TEST_POINT_SMALL")
      (libsource (lib "eagle-import") (part "TEST_POINT_T_SMALL"))
    )
    (comp (ref "TP106")
      (value "TEST_POINT_T_SMALL")
      (footprint "eagle-import:T_TEST_POINT_SMALL")
      (libsource (lib "eagle-import") (part "TEST_POINT_T_SMALL"))
    )
    (comp (ref "TP107")
      (value "TEST_POINT_T_SMALL")
      (footprint "eagle-import:T_TEST_POINT_SMALL")
      (libsource (lib "eagle-import") (part "TEST_POINT_T_SMALL"))
    )
    (comp (ref "TP108")
      (value "TEST_POINT_T_SMALL")
      (footprint "eagle-import:T_TEST_POINT_SMALL")
      (libsource (lib "eagle-import") (part "TEST_POINT_T_SMALL"))
    )
    (comp (ref "TP109")
      (value "TEST_POINT_T_SMALL")
      (footprint "eagle-import:T_TEST_POINT_SMALL")
      (libsource (lib "eagle-import") (part "TEST_POINT_T_SMALL"))
    )
    (comp (ref "TP110")
      (value "TEST_POINT_T_SMALL")
      (footprint "eagle-import:T_TEST_POINT_SMALL")
      (libsource (lib "eagle-import") (part "TEST_POINT_T_SMALL"))
    )
    (comp (ref "TP111")
      (value "TEST_POINT_T_SMALL")
      (footprint "eagle-import:T_TEST_POINT_SMALL")
      (libsource (lib "eagle-import") (part "TEST_POINT_T_SMALL"))
    )
    (comp (ref "TP112")
      (value "TEST_POINT_T_SMALL")
      (footprint "eagle-import:T_TEST_POINT_SMALL")
      (libsource (lib "eagle-import") (part "TEST_POINT_T_SMALL"))
    )
    (comp (ref "TP113")
      (value "TEST_POINT_T_SMALL")
      (footprint "eagle-import:T_TEST_POINT_SMALL")
      (libsource (lib "eagle-import") (part "TEST_POINT_T_SMALL"))
    )
    (comp (ref "TP114")
      (value "TEST_POINT_T_SMALL")
      (footprint "eagle-import:T_TEST_POINT_SMALL")
      (libsource (lib "eagle-import") (part "TEST_POINT_T_SMALL"))
    )
    (comp (ref "TP115")
      (value "TEST_POINT_T_SMALL")
      (footprint "eagle-import:T_TEST_POINT_SMALL")
      (libsource (lib "eagle-import") (part "TEST_POINT_T_SMALL"))
    )
    (comp (ref "TP116")
      (value "TEST_POINT_T_SMALL")
      (footprint "eagle-import:T_TEST_POINT_SMALL")
      (libsource (lib "eagle-import") (part "TEST_POINT_T_SMALL"))
    )
    (comp (ref "TP117")
      (value "TEST_POINT_T_SMALL")
      (footprint "eagle-import:T_TEST_POINT_SMALL")
      (libsource (lib "eagle-import") (part "TEST_POINT_T_SMALL"))
    )
    (comp (ref "TP118")
      (value "TEST_POINT_T_SMALL")
      (footprint "eagle-import:T_TEST_POINT_SMALL")
      (libsource (lib "eagle-import") (part "TEST_POINT_T_SMALL"))
    )
    (comp (ref "TP119")
      (value "TEST_POINT_T_SMALL")
      (footprint "eagle-import:T_TEST_POINT_SMALL")
      (libsource (lib "eagle-import") (part "TEST_POINT_T_SMALL"))
    )
    (comp (ref "TP120")
      (value "TEST_POINT_T_SMALL")
      (footprint "eagle-import:T_TEST_POINT_SMALL")
      (libsource (lib "eagle-import") (part "TEST_POINT_T_SMALL"))
    )
    (comp (ref "TP121")
      (value "TEST_POINT_T_SMALL")
      (footprint "eagle-import:T_TEST_POINT_SMALL")
      (libsource (lib "eagle-import") (part "TEST_POINT_T_SMALL"))
    )
    (comp (ref "TP122")
      (value "TEST_POINT_T_SMALL")
      (footprint "eagle-import:T_TEST_POINT_SMALL")
      (libsource (lib "eagle-import") (part "TEST_POINT_T_SMALL"))
    )
    (comp (ref "TP123")
      (value "TEST_POINT_T_SMALL")
      (footprint "eagle-import:T_TEST_POINT_SMALL")
      (libsource (lib "eagle-import") (part "TEST_POINT_T_SMALL"))
    )
    (comp (ref "TP124")
      (value "TEST_POINT_T_SMALL")
      (footprint "eagle-import:T_TEST_POINT_SMALL")
      (libsource (lib "eagle-import") (part "TEST_POINT_T_SMALL"))
    )
    (comp (ref "TP125")
      (value "TEST_POINT_T_SMALL")
      (footprint "eagle-import:T_TEST_POINT_SMALL")
      (libsource (lib "eagle-import") (part "TEST_POINT_T_SMALL"))
    )
    (comp (ref "TP126")
      (value "TEST_POINT_T_SMALL")
      (footprint "eagle-import:T_TEST_POINT_SMALL")
      (libsource (lib "eagle-import") (part "TEST_POINT_T_SMALL"))
    )
    (comp (ref "TP127")
      (value "TEST_POINT_T_SMALL")
      (footprint "eagle-import:T_TEST_POINT_SMALL")
      (libsource (lib "eagle-import") (part "TEST_POINT_T_SMALL"))
    )
    (comp (ref "TP128")
      (value "TEST_POINT_T_SMALL")
      (footprint "eagle-import:T_TEST_POINT_SMALL")
      (libsource (lib "eagle-import") (part "TEST_POINT_T_SMALL"))
    )
    (comp (ref "TP129")
      (value "TEST_POINT_T_SMALL")
      (footprint "eagle-import:T_TEST_POINT_SMALL")
      (libsource (lib "eagle-import") (part "TEST_POINT_T_SMALL"))
    )
    (comp (ref "TP130")
      (value "TEST_POINT_T_SMALL")
      (footprint "eagle-import:T_TEST_POINT_SMALL")
      (libsource (lib "eagle-import") (part "TEST_POINT_T_SMALL"))
    )
    (comp (ref "TP131")
      (value "TEST_POINT_T_SMALL")
      (footprint "eagle-import:T_TEST_POINT_SMALL")
      (libsource (lib "eagle-import") (part "TEST_POINT_T_SMALL"))
    )
    (comp (ref "TP132")
      (value "TEST_POINT_T_SMALL")
      (footprint "eagle-import:T_TEST_POINT_SMALL")
      (libsource (lib "eagle-import") (part "TEST_POINT_T_SMALL"))
    )
    (comp (ref "TP133")
      (value "TEST_POINT_T_SMALL")
      (footprint "eagle-import:T_TEST_POINT_SMALL")
      (libsource (lib "eagle-import") (part "TEST_POINT_T_SMALL"))
    )
    (comp (ref "TP134")
      (value "TEST_POINT_T_SMALL")
      (footprint "eagle-import:T_TEST_POINT_SMALL")
      (libsource (lib "eagle-import") (part "TEST_POINT_T_SMALL"))
    )
    (comp (ref "TP135")
      (value "TEST_POINT_T_SMALL")
      (footprint "eagle-import:T_TEST_POINT_SMALL")
      (libsource (lib "eagle-import") (part "TEST_POINT_T_SMALL"))
    )
    (comp (ref "TP136")
      (value "TEST_POINT_T_SMALL")
      (footprint "eagle-import:T_TEST_POINT_SMALL")
      (libsource (lib "eagle-import") (part "TEST_POINT_T_SMALL"))
    )
    (comp (ref "X101")
      (value "CLAMP_1X4-T-5MM")
      (footprint "eagle-import:T_WIRE_CLAMP_1X4_5MM")
      (fields (field (name "FUNCTION") "Power Supply Input"))
      (libsource (lib "eagle-import") (part "CLAMP_1X4-T-5MM"))
    )
    (comp (ref "DIS301")
      (value "VQE24")
      (footprint "eagle-import:T_VQE_XX_2DIGIT")
      (fields (field (name "PART_CODE_BEL") "DIS_T_PAC_VQExx_2DIGIT_VAL_VQE24"))
      (libsource (lib "eagle-import") (part "VQEXX_2DIGIT_T_VQEXX_2DIGIT"))
    )
    (comp (ref "DIS302")
      (value "VQE14")
      (footprint "eagle-import:T_VQE_XX_2DIGIT")
      (fields (field (name "PART_CODE_BEL") "DIS_T_PAC_VQExx_2DIGIT_VAL_VQE14"))
      (libsource (lib "eagle-import") (part "VQEXX_2DIGIT_T_VQEXX_2DIGIT"))
    )
    (comp (ref "DIS303")
      (value "VQE24")
      (footprint "eagle-import:T_VQE_XX_2DIGIT")
      (fields (field (name "PART_CODE_BEL") "DIS_T_PAC_VQExx_2DIGIT_VAL_VQE24"))
      (libsource (lib "eagle-import") (part "VQEXX_2DIGIT_T_VQEXX_2DIGIT"))
    )
    (comp (ref "R301")
      (value "10")
      (footprint "eagle-import:T_0207_GRID10MM")
      (fields (field (name "PART_CODE_BEL") "R_PAC_T_0207_GRID10mm_VAL_10"))
      (libsource (lib "eagle-import") (part "R_EU_T_0207_GRID10MM"))
    )
    (comp (ref "R302")
      (value "10")
      (footprint "eagle-import:T_0207_GRID10MM")
      (fields (field (name "PART_CODE_BEL") "R_PAC_T_0207_GRID10mm_VAL_10"))
      (libsource (lib "eagle-import") (part "R_EU_T_0207_GRID10MM"))
    )
    (comp (ref "R303")
      (value "10")
      (footprint "eagle-import:T_0207_GRID10MM")
      (fields (field (name "PART_CODE_BEL") "R_PAC_T_0207_GRID10mm_VAL_10"))
      (libsource (lib "eagle-import") (part "R_EU_T_0207_GRID10MM"))
    )
    (comp (ref "R304")
      (value "10")
      (footprint "eagle-import:T_0207_GRID10MM")
      (fields (field (name "PART_CODE_BEL") "R_PAC_T_0207_GRID10mm_VAL_10"))
      (libsource (lib "eagle-import") (part "R_EU_T_0207_GRID10MM"))
    )
    (comp (ref "R305")
      (value "10")
      (footprint "eagle-import:T_0207_GRID10MM")
      (fields (field (name "PART_CODE_BEL") "R_PAC_T_0207_GRID10mm_VAL_10"))
      (libsource (lib "eagle-import") (part "R_EU_T_0207_GRID10MM"))
    )
    (comp (ref "R306")
      (value "10")
      (footprint "eagle-import:T_0207_GRID10MM")
      (fields (field (name "PART_CODE_BEL") "R_PAC_T_0207_GRID10mm_VAL_10"))
      (libsource (lib "eagle-import") (part "R_EU_T_0207_GRID10MM"))
    )
    (comp (ref "R307")
      (value "10")
      (footprint "eagle-import:T_0207_GRID10MM")
      (fields (field (name "PART_CODE_BEL") "R_PAC_T_0207_GRID10mm_VAL_10"))
      (libsource (lib "eagle-import") (part "R_EU_T_0207_GRID10MM"))
    )
    (comp (ref "TP301")
      (value "TEST_POINT_T_SMALL")
      (footprint "eagle-import:T_TEST_POINT_SMALL")
      (libsource (lib "eagle-import") (part "TEST_POINT_T_SMALL"))
    )
    (comp (ref "TP302")
      (value "TEST_POINT_T_SMALL")
      (footprint "eagle-import:T_TEST_POINT_SMALL")
      (libsource (lib "eagle-import") (part "TEST_POINT_T_SMALL"))
    )
    (comp (ref "TP303")
      (value "TEST_POINT_T_SMALL")
      (footprint "eagle-import:T_TEST_POINT_SMALL")
      (libsource (lib "eagle-import") (part "TEST_POINT_T_SMALL"))
    )
    (comp (ref "TP304")
      (value "TEST_POINT_T_SMALL")
      (footprint "eagle-import:T_TEST_POINT_SMALL")
      (libsource (lib "eagle-import") (part "TEST_POINT_T_SMALL"))
    )
    (comp (ref "TP305")
      (value "TEST_POINT_T_SMALL")
      (footprint "eagle-import:T_TEST_POINT_SMALL")
      (libsource (lib "eagle-import") (part "TEST_POINT_T_SMALL"))
    )
    (comp (ref "TP306")
      (value "TEST_POINT_T_SMALL")
      (footprint "eagle-import:T_TEST_POINT_SMALL")
      (libsource (lib "eagle-import") (part "TEST_POINT_T_SMALL"))
    )
    (comp (ref "RN601")
      (value "2k7")
      (footprint "eagle-import:T_SIL8")
      (fields (field (name "PART_CODE_BEL") "RN_PAC_T_SIL8_VAL_2k7"))
      (libsource (lib "eagle-import") (part "R_EU_ARRAY_4"))
    )
    (comp (ref "T601")
      (value "BC327")
      (footprint "eagle-import:T_TO92-CBE")
      (fields (field (name "PART_CODE_BEL") "T_PAC_T_TO92-CBE_VAL_BC327"))
      (libsource (lib "eagle-import") (part "PNP_T_TO92-CBE"))
    )
    (comp (ref "T602")
      (value "BC548C")
      (footprint "eagle-import:T_TO92-CBE")
      (fields (field (name "PART_CODE_BEL") "T_PAC_T_TO92-CBE_VAL_BC548C"))
      (libsource (lib "eagle-import") (part "NPN_T_TO92-CBE"))
    )
    (comp (ref "T603")
      (value "BC327")
      (footprint "eagle-import:T_TO92-CBE")
      (fields (field (name "PART_CODE_BEL") "T_PAC_T_TO92-CBE_VAL_BC327"))
      (libsource (lib "eagle-import") (part "PNP_T_TO92-CBE"))
    )
    (comp (ref "T604")
      (value "BC548C")
      (footprint "eagle-import:T_TO92-CBE")
      (fields (field (name "PART_CODE_BEL") "T_PAC_T_TO92-CBE_VAL_BC548C"))
      (libsource (lib "eagle-import") (part "NPN_T_TO92-CBE"))
    )
    (comp (ref "T605")
      (value "BC327")
      (footprint "eagle-import:T_TO92-CBE")
      (fields (field (name "PART_CODE_BEL") "T_PAC_T_TO92-CBE_VAL_BC327"))
      (libsource (lib "eagle-import") (part "PNP_T_TO92-CBE"))
    )
    (comp (ref "T606")
      (value "BC548C")
      (footprint "eagle-import:T_TO92-CBE")
      (fields (field (name "PART_CODE_BEL") "T_PAC_T_TO92-CBE_VAL_BC548C"))
      (libsource (lib "eagle-import") (part "NPN_T_TO92-CBE"))
    )
    (comp (ref "D401")
      (value "green")
      (footprint "eagle-import:T_LED_3MM")
      (fields (field (name "FUNCTION") "IEI") (field (name "PART_CODE_BEL") "LED_PAC_T_3mm_VAL_green"))
      (libsource (lib "eagle-import") (part "LED_T_3MM"))
    )
    (comp (ref "D402")
      (value "green")
      (footprint "eagle-import:T_LED_3MM")
      (fields (field (name "FUNCTION") "RSVD") (field (name "PART_CODE_BEL") "LED_PAC_T_3mm_VAL_green"))
      (libsource (lib "eagle-import") (part "LED_T_3MM"))
    )
    (comp (ref "D403")
      (value "green")
      (footprint "eagle-import:T_LED_3MM")
      (fields (field (name "FUNCTION") "NMI") (field (name "PART_CODE_BEL") "LED_PAC_T_3mm_VAL_green"))
      (libsource (lib "eagle-import") (part "LED_T_3MM"))
    )
    (comp (ref "D404")
      (value "red")
      (footprint "eagle-import:T_LED_3MM")
      (fields (field (name "FUNCTION") "RST") (field (name "PART_CODE_BEL") "LED_PAC_T_3mm_VAL_red"))
      (libsource (lib "eagle-import") (part "LED_T_3MM"))
    )
    (comp (ref "D405")
      (value "green")
      (footprint "eagle-import:T_LED_3MM")
      (fields (field (name "FUNCTION") "INT") (field (name "PART_CODE_BEL") "LED_PAC_T_3mm_VAL_green"))
      (libsource (lib "eagle-import") (part "LED_T_3MM"))
    )
    (comp (ref "D406")
      (value "green")
      (footprint "eagle-import:T_LED_3MM")
      (fields (field (name "FUNCTION") "M1") (field (name "PART_CODE_BEL") "LED_PAC_T_3mm_VAL_green"))
      (libsource (lib "eagle-import") (part "LED_T_3MM"))
    )
    (comp (ref "D407")
      (value "green")
      (footprint "eagle-import:T_LED_3MM")
      (fields (field (name "FUNCTION") "IORQ") (field (name "PART_CODE_BEL") "LED_PAC_T_3mm_VAL_green"))
      (libsource (lib "eagle-import") (part "LED_T_3MM"))
    )
    (comp (ref "D408")
      (value "green")
      (footprint "eagle-import:T_LED_3MM")
      (fields (field (name "FUNCTION") "MRQ") (field (name "PART_CODE_BEL") "LED_PAC_T_3mm_VAL_green"))
      (libsource (lib "eagle-import") (part "LED_T_3MM"))
    )
    (comp (ref "D409")
      (value "green")
      (footprint "eagle-import:T_LED_3MM")
      (fields (field (name "FUNCTION") "WR") (field (name "PART_CODE_BEL") "LED_PAC_T_3mm_VAL_green"))
      (libsource (lib "eagle-import") (part "LED_T_3MM"))
    )
    (comp (ref "D410")
      (value "green")
      (footprint "eagle-import:T_LED_3MM")
      (fields (field (name "FUNCTION") "RD") (field (name "PART_CODE_BEL") "LED_PAC_T_3mm_VAL_green"))
      (libsource (lib "eagle-import") (part "LED_T_3MM"))
    )
    (comp (ref "D411")
      (value "green")
      (footprint "eagle-import:T_LED_3MM")
      (fields (field (name "FUNCTION") "HALT") (field (name "PART_CODE_BEL") "LED_PAC_T_3mm_VAL_green"))
      (libsource (lib "eagle-import") (part "LED_T_3MM"))
    )
    (comp (ref "D412")
      (value "green")
      (footprint "eagle-import:T_LED_3MM")
      (fields (field (name "FUNCTION") "WAIT") (field (name "PART_CODE_BEL") "LED_PAC_T_3mm_VAL_green"))
      (libsource (lib "eagle-import") (part "LED_T_3MM"))
    )
    (comp (ref "D413")
      (value "green")
      (footprint "eagle-import:T_LED_3MM")
      (fields (field (name "FUNCTION") "BSAK") (field (name "PART_CODE_BEL") "LED_PAC_T_3mm_VAL_green"))
      (libsource (lib "eagle-import") (part "LED_T_3MM"))
    )
    (comp (ref "D414")
      (value "green")
      (footprint "eagle-import:T_LED_3MM")
      (fields (field (name "FUNCTION") "BSRQ") (field (name "PART_CODE_BEL") "LED_PAC_T_3mm_VAL_green"))
      (libsource (lib "eagle-import") (part "LED_T_3MM"))
    )
    (comp (ref "R401")
      (value "160")
      (footprint "eagle-import:T_0207_GRID10MM")
      (fields (field (name "PART_CODE_BEL") "R_PAC_T_0207_GRID10mm_VAL_160"))
      (libsource (lib "eagle-import") (part "R_EU_T_0207_GRID10MM"))
    )
    (comp (ref "R402")
      (value "160")
      (footprint "eagle-import:T_0207_GRID10MM")
      (fields (field (name "PART_CODE_BEL") "R_PAC_T_0207_GRID10mm_VAL_160"))
      (libsource (lib "eagle-import") (part "R_EU_T_0207_GRID10MM"))
    )
    (comp (ref "R403")
      (value "160")
      (footprint "eagle-import:T_0207_GRID10MM")
      (fields (field (name "PART_CODE_BEL") "R_PAC_T_0207_GRID10mm_VAL_160"))
      (libsource (lib "eagle-import") (part "R_EU_T_0207_GRID10MM"))
    )
    (comp (ref "R404")
      (value "160")
      (footprint "eagle-import:T_0207_GRID10MM")
      (fields (field (name "PART_CODE_BEL") "R_PAC_T_0207_GRID10mm_VAL_160"))
      (libsource (lib "eagle-import") (part "R_EU_T_0207_GRID10MM"))
    )
    (comp (ref "R405")
      (value "160")
      (footprint "eagle-import:T_0207_GRID10MM")
      (fields (field (name "PART_CODE_BEL") "R_PAC_T_0207_GRID10mm_VAL_160"))
      (libsource (lib "eagle-import") (part "R_EU_T_0207_GRID10MM"))
    )
    (comp (ref "R406")
      (value "160")
      (footprint "eagle-import:T_0207_GRID10MM")
      (fields (field (name "PART_CODE_BEL") "R_PAC_T_0207_GRID10mm_VAL_160"))
      (libsource (lib "eagle-import") (part "R_EU_T_0207_GRID10MM"))
    )
    (comp (ref "R407")
      (value "160")
      (footprint "eagle-import:T_0207_GRID10MM")
      (fields (field (name "PART_CODE_BEL") "R_PAC_T_0207_GRID10mm_VAL_160"))
      (libsource (lib "eagle-import") (part "R_EU_T_0207_GRID10MM"))
    )
    (comp (ref "R408")
      (value "160")
      (footprint "eagle-import:T_0207_GRID10MM")
      (fields (field (name "PART_CODE_BEL") "R_PAC_T_0207_GRID10mm_VAL_160"))
      (libsource (lib "eagle-import") (part "R_EU_T_0207_GRID10MM"))
    )
    (comp (ref "R409")
      (value "160")
      (footprint "eagle-import:T_0207_GRID10MM")
      (fields (field (name "PART_CODE_BEL") "R_PAC_T_0207_GRID10mm_VAL_160"))
      (libsource (lib "eagle-import") (part "R_EU_T_0207_GRID10MM"))
    )
    (comp (ref "R410")
      (value "160")
      (footprint "eagle-import:T_0207_GRID10MM")
      (fields (field (name "PART_CODE_BEL") "R_PAC_T_0207_GRID10mm_VAL_160"))
      (libsource (lib "eagle-import") (part "R_EU_T_0207_GRID10MM"))
    )
    (comp (ref "R411")
      (value "160")
      (footprint "eagle-import:T_0207_GRID10MM")
      (fields (field (name "PART_CODE_BEL") "R_PAC_T_0207_GRID10mm_VAL_160"))
      (libsource (lib "eagle-import") (part "R_EU_T_0207_GRID10MM"))
    )
    (comp (ref "R412")
      (value "160")
      (footprint "eagle-import:T_0207_GRID10MM")
      (fields (field (name "PART_CODE_BEL") "R_PAC_T_0207_GRID10mm_VAL_160"))
      (libsource (lib "eagle-import") (part "R_EU_T_0207_GRID10MM"))
    )
    (comp (ref "R413")
      (value "160")
      (footprint "eagle-import:T_0207_GRID10MM")
      (fields (field (name "PART_CODE_BEL") "R_PAC_T_0207_GRID10mm_VAL_160"))
      (libsource (lib "eagle-import") (part "R_EU_T_0207_GRID10MM"))
    )
    (comp (ref "R414")
      (value "160")
      (footprint "eagle-import:T_0207_GRID10MM")
      (fields (field (name "PART_CODE_BEL") "R_PAC_T_0207_GRID10mm_VAL_160"))
      (libsource (lib "eagle-import") (part "R_EU_T_0207_GRID10MM"))
    )
    (comp (ref "RN901")
      (value "10k")
      (footprint "eagle-import:T_SIL9")
      (fields (field (name "PART_CODE_BEL") "RN_PAC_T_SIL9_VAL_10k"))
      (libsource (lib "eagle-import") (part "R_EU_ARRAY_1C_8_T_SIL9"))
    )
    (comp (ref "RN902")
      (value "10k")
      (footprint "eagle-import:T_SIL9")
      (fields (field (name "PART_CODE_BEL") "RN_PAC_T_SIL9_VAL_10k"))
      (libsource (lib "eagle-import") (part "R_EU_ARRAY_1C_8_T_SIL9"))
    )
    (comp (ref "RN903")
      (value "10k")
      (footprint "eagle-import:T_SIL9")
      (fields (field (name "PART_CODE_BEL") "RN_PAC_T_SIL9_VAL_10k"))
      (libsource (lib "eagle-import") (part "R_EU_ARRAY_1C_8_T_SIL9"))
    )
    (comp (ref "S901")
      (value "PUSH_BUTTON_T_6X6MM")
      (footprint "eagle-import:T_PUSH_BUTTON_6X6")
      (libsource (lib "eagle-import") (part "PUSH_BUTTON_T_6X6MM"))
    )
    (comp (ref "S902")
      (value "PUSH_BUTTON_T_6X6MM")
      (footprint "eagle-import:T_PUSH_BUTTON_6X6")
      (libsource (lib "eagle-import") (part "PUSH_BUTTON_T_6X6MM"))
    )
    (comp (ref "S903")
      (value "PUSH_BUTTON_T_6X6MM")
      (footprint "eagle-import:T_PUSH_BUTTON_6X6")
      (libsource (lib "eagle-import") (part "PUSH_BUTTON_T_6X6MM"))
    )
    (comp (ref "S904")
      (value "DIP08")
      (footprint "eagle-import:T_DIP08")
      (libsource (lib "eagle-import") (part "DIP08"))
    )
    (comp (ref "TP901")
      (value "TEST_POINT_T_SMALL")
      (footprint "eagle-import:T_TEST_POINT_SMALL")
      (libsource (lib "eagle-import") (part "TEST_POINT_T_SMALL"))
    )
    (comp (ref "X901")
      (value "MALE_2X20-T-VERTICAL")
      (footprint "eagle-import:T_MALE_2X20_VERTICAL")
      (fields (field (name "FUNCTION") "PIO_DBG"))
      (libsource (lib "eagle-import") (part "MALE_2X20-T-VERTICAL"))
    )
    (comp (ref "RN701")
      (value "100")
      (footprint "eagle-import:T_SIL8")
      (fields (field (name "PART_CODE_BEL") "RN_PAC_T_SIL8_VAL_100"))
      (libsource (lib "eagle-import") (part "R_EU_ARRAY_4"))
    )
    (comp (ref "RN702")
      (value "100")
      (footprint "eagle-import:T_SIL8")
      (fields (field (name "PART_CODE_BEL") "RN_PAC_T_SIL8_VAL_100"))
      (libsource (lib "eagle-import") (part "R_EU_ARRAY_4"))
    )
    (comp (ref "T701")
      (value "BD136")
      (footprint "eagle-import:T_TO126_VERTICAL")
      (fields (field (name "PART_CODE_BEL") "T_PAC_T_TO126_VERTICAL_VAL_BD136"))
      (libsource (lib "eagle-import") (part "PNP_T_TO126_VERTICAL"))
    )
    (comp (ref "T702")
      (value "BD135")
      (footprint "eagle-import:T_TO126_VERTICAL")
      (fields (field (name "PART_CODE_BEL") "T_PAC_T_TO126_VERTICAL_VAL_BD135"))
      (libsource (lib "eagle-import") (part "NPN_T_TO126_VERTICAL"))
    )
    (comp (ref "T703")
      (value "BD136")
      (footprint "eagle-import:T_TO126_VERTICAL")
      (fields (field (name "PART_CODE_BEL") "T_PAC_T_TO126_VERTICAL_VAL_BD136"))
      (libsource (lib "eagle-import") (part "PNP_T_TO126_VERTICAL"))
    )
    (comp (ref "T704")
      (value "BD135")
      (footprint "eagle-import:T_TO126_VERTICAL")
      (fields (field (name "PART_CODE_BEL") "T_PAC_T_TO126_VERTICAL_VAL_BD135"))
      (libsource (lib "eagle-import") (part "NPN_T_TO126_VERTICAL"))
    )
    (comp (ref "T705")
      (value "BD136")
      (footprint "eagle-import:T_TO126_VERTICAL")
      (fields (field (name "PART_CODE_BEL") "T_PAC_T_TO126_VERTICAL_VAL_BD136"))
      (libsource (lib "eagle-import") (part "PNP_T_TO126_VERTICAL"))
    )
    (comp (ref "T706")
      (value "BD135")
      (footprint "eagle-import:T_TO126_VERTICAL")
      (fields (field (name "PART_CODE_BEL") "T_PAC_T_TO126_VERTICAL_VAL_BD135"))
      (libsource (lib "eagle-import") (part "NPN_T_TO126_VERTICAL"))
    )
    (comp (ref "J1001")
      (value "JUMPER_1X2-T-VERTICAL")
      (footprint "eagle-import:T_MALE_2X1_VERTICAL")
      (fields (field (name "FUNCTION") "JTAG Vref Enable"))
      (libsource (lib "eagle-import") (part "JUMPER_1X2-T-VERTICAL"))
    )
    (comp (ref "R1001")
      (value "300")
      (footprint "eagle-import:T_0207_GRID10MM")
      (fields (field (name "PART_CODE_BEL") "R_PAC_T_0207_GRID10mm_VAL_300"))
      (libsource (lib "eagle-import") (part "R_EU_T_0207_GRID10MM"))
    )
    (comp (ref "R1002")
      (value "300")
      (footprint "eagle-import:T_0207_GRID10MM")
      (fields (field (name "PART_CODE_BEL") "R_PAC_T_0207_GRID10mm_VAL_300"))
      (libsource (lib "eagle-import") (part "R_EU_T_0207_GRID10MM"))
    )
    (comp (ref "RN1001")
      (value "10k")
      (footprint "eagle-import:T_SIL9")
      (fields (field (name "PART_CODE_BEL") "RN_PAC_T_SIL9_VAL_10k"))
      (libsource (lib "eagle-import") (part "R_EU_ARRAY_1C_8_T_SIL9"))
    )
    (comp (ref "TP1001")
      (value "TEST_POINT_T_SMALL")
      (footprint "eagle-import:T_TEST_POINT_SMALL")
      (libsource (lib "eagle-import") (part "TEST_POINT_T_SMALL"))
    )
    (comp (ref "TP1002")
      (value "TEST_POINT_T_SMALL")
      (footprint "eagle-import:T_TEST_POINT_SMALL")
      (libsource (lib "eagle-import") (part "TEST_POINT_T_SMALL"))
    )
    (comp (ref "TP1003")
      (value "TEST_POINT_T_SMALL")
      (footprint "eagle-import:T_TEST_POINT_SMALL")
      (libsource (lib "eagle-import") (part "TEST_POINT_T_SMALL"))
    )
    (comp (ref "TP1004")
      (value "TEST_POINT_T_SMALL")
      (footprint "eagle-import:T_TEST_POINT_SMALL")
      (libsource (lib "eagle-import") (part "TEST_POINT_T_SMALL"))
    )
    (comp (ref "X1001")
      (value "MALE_2X5-T-VERTICAL_2.54MM")
      (footprint "eagle-import:T_MALE_2X5_VERTICAL")
      (libsource (lib "eagle-import") (part "MALE_2X5-T-VERTICAL_2.54MM"))
    )
    (comp (ref "R1101")
      (value "2k7")
      (footprint "eagle-import:T_0207_GRID10MM")
      (fields (field (name "PART_CODE_BEL") "R_PAC_T_0207_GRID10mm_VAL_2k7"))
      (libsource (lib "eagle-import") (part "R_EU_T_0207_GRID10MM"))
    )
    (comp (ref "R1102")
      (value "10k")
      (footprint "eagle-import:T_0207_GRID10MM")
      (fields (field (name "PART_CODE_BEL") "R_PAC_T_0207_GRID10mm_VAL_10k"))
      (libsource (lib "eagle-import") (part "R_EU_T_0207_GRID10MM"))
    )
    (comp (ref "R1103")
      (value "300")
      (footprint "eagle-import:T_0207_GRID10MM")
      (fields (field (name "PART_CODE_BEL") "R_PAC_T_0207_GRID10mm_VAL_300"))
      (libsource (lib "eagle-import") (part "R_EU_T_0207_GRID10MM"))
    )
    (comp (ref "R1104")
      (value "300")
      (footprint "eagle-import:T_0207_GRID10MM")
      (fields (field (name "PART_CODE_BEL") "R_PAC_T_0207_GRID10mm_VAL_300"))
      (libsource (lib "eagle-import") (part "R_EU_T_0207_GRID10MM"))
    )
    (comp (ref "T1101")
      (value "BC548C")
      (footprint "eagle-import:T_TO92-CBE")
      (fields (field (name "PART_CODE_BEL") "T_PAC_T_TO92-CBE_VAL_BC548C"))
      (libsource (lib "eagle-import") (part "NPN_T_TO92-CBE"))
    )
    (comp (ref "TP1101")
      (value "TEST_POINT_T_SMALL")
      (footprint "eagle-import:T_TEST_POINT_SMALL")
      (libsource (lib "eagle-import") (part "TEST_POINT_T_SMALL"))
    )
    (comp (ref "TP1102")
      (value "TEST_POINT_T_SMALL")
      (footprint "eagle-import:T_TEST_POINT_SMALL")
      (libsource (lib "eagle-import") (part "TEST_POINT_T_SMALL"))
    )
    (comp (ref "TP1103")
      (value "TEST_POINT_T_SMALL")
      (footprint "eagle-import:T_TEST_POINT_SMALL")
      (libsource (lib "eagle-import") (part "TEST_POINT_T_SMALL"))
    )
    (comp (ref "X1101")
      (value "MALE_2X20-T-VERTICAL")
      (footprint "eagle-import:T_MALE_2X20_VERTICAL")
      (fields (field (name "FUNCTION") "CPU_CTRL&DATA"))
      (libsource (lib "eagle-import") (part "MALE_2X20-T-VERTICAL"))
    )
    (comp (ref "X1102")
      (value "MALE_2X20-T-VERTICAL")
      (footprint "eagle-import:T_MALE_2X20_VERTICAL")
      (fields (field (name "FUNCTION") "CPU_CTRL&ADDR"))
      (libsource (lib "eagle-import") (part "MALE_2X20-T-VERTICAL"))
    )
    (comp (ref "X1103")
      (value "MALE_2X20-T-VERTICAL")
      (footprint "eagle-import:T_MALE_2X20_VERTICAL")
      (fields (field (name "FUNCTION") "EXT_CTRL&DATA"))
      (libsource (lib "eagle-import") (part "MALE_2X20-T-VERTICAL"))
    )
    (comp (ref "X1104")
      (value "MALE_2X20-T-VERTICAL")
      (footprint "eagle-import:T_MALE_2X20_VERTICAL")
      (fields (field (name "FUNCTION") "EXT_CTRL&ADDR"))
      (libsource (lib "eagle-import") (part "MALE_2X20-T-VERTICAL"))
    )
    (comp (ref "C1201")
      (value "4n7")
      (footprint "eagle-import:T_7X3MM_GRID_5MM")
      (fields (field (name "PART_CODE_BEL") "C_PAC_T_7x3mm_GRID_5mm_VAL_4n7"))
      (libsource (lib "eagle-import") (part "C_EU_S_7X3MM_GRID_5MM"))
    )
    (comp (ref "C1202")
      (value "100n")
      (footprint "eagle-import:S_0805")
      (fields (field (name "PART_CODE_BEL") "C_PAC_S_0805_VAL_100n"))
      (libsource (lib "eagle-import") (part "C_EU_S_0805"))
    )
    (comp (ref "IC1201")
      (value "4093N")
      (footprint "eagle-import:T_NDIP14")
      (libsource (lib "eagle-import") (part "4093N"))
    )
    (comp (ref "R1201")
      (value "10k")
      (footprint "eagle-import:T_0207_GRID10MM")
      (fields (field (name "PART_CODE_BEL") "R_PAC_T_0207_GRID10mm_VAL_10k"))
      (libsource (lib "eagle-import") (part "R_EU_T_0207_GRID10MM"))
    )
    (comp (ref "TP1201")
      (value "TEST_POINT_T_SMALL")
      (footprint "eagle-import:T_TEST_POINT_SMALL")
      (libsource (lib "eagle-import") (part "TEST_POINT_T_SMALL"))
    )
    (comp (ref "TP1202")
      (value "TEST_POINT_T_SMALL")
      (footprint "eagle-import:T_TEST_POINT_SMALL")
      (libsource (lib "eagle-import") (part "TEST_POINT_T_SMALL"))
    )
    (comp (ref "TP1203")
      (value "TEST_POINT_T_SMALL")
      (footprint "eagle-import:T_TEST_POINT_SMALL")
      (libsource (lib "eagle-import") (part "TEST_POINT_T_SMALL"))
    )
    (comp (ref "TP1204")
      (value "TEST_POINT_T_SMALL")
      (footprint "eagle-import:T_TEST_POINT_SMALL")
      (libsource (lib "eagle-import") (part "TEST_POINT_T_SMALL"))
    )
    (comp (ref "TP1205")
      (value "TEST_POINT_T_SMALL")
      (footprint "eagle-import:T_TEST_POINT_SMALL")
      (libsource (lib "eagle-import") (part "TEST_POINT_T_SMALL"))
    )
    (comp (ref "IC201")
      (value "XC95288XL-xTQ144x")
      (footprint "eagle-import:S_TQFP144")
      (libsource (lib "eagle-import") (part "XC95288XL-TQG144"))
    )
    (comp (ref "TP201")
      (value "TEST_POINT_T_SMALL")
      (footprint "eagle-import:T_TEST_POINT_SMALL")
      (libsource (lib "eagle-import") (part "TEST_POINT_T_SMALL"))
    )
    (comp (ref "RN801")
      (value "10k")
      (footprint "eagle-import:T_SIL9")
      (fields (field (name "PART_CODE_BEL") "RN_PAC_T_SIL9_VAL_10k"))
      (libsource (lib "eagle-import") (part "R_EU_ARRAY_1C_8_T_SIL9"))
    )
    (comp (ref "RN802")
      (value "10k")
      (footprint "eagle-import:T_SIL9")
      (fields (field (name "PART_CODE_BEL") "RN_PAC_T_SIL9_VAL_10k"))
      (libsource (lib "eagle-import") (part "R_EU_ARRAY_1C_8_T_SIL9"))
    )
    (comp (ref "T801")
      (value "BD136")
      (footprint "eagle-import:T_TO126_VERTICAL")
      (fields (field (name "PART_CODE_BEL") "T_PAC_T_TO126_VERTICAL_VAL_BD136"))
      (libsource (lib "eagle-import") (part "PNP_T_TO126_VERTICAL"))
    )
    (comp (ref "T802")
      (value "BD135")
      (footprint "eagle-import:T_TO126_VERTICAL")
      (fields (field (name "PART_CODE_BEL") "T_PAC_T_TO126_VERTICAL_VAL_BD135"))
      (libsource (lib "eagle-import") (part "NPN_T_TO126_VERTICAL"))
    )
    (comp (ref "T803")
      (value "BD136")
      (footprint "eagle-import:T_TO126_VERTICAL")
      (fields (field (name "PART_CODE_BEL") "T_PAC_T_TO126_VERTICAL_VAL_BD136"))
      (libsource (lib "eagle-import") (part "PNP_T_TO126_VERTICAL"))
    )
    (comp (ref "T804")
      (value "BD135")
      (footprint "eagle-import:T_TO126_VERTICAL")
      (fields (field (name "PART_CODE_BEL") "T_PAC_T_TO126_VERTICAL_VAL_BD135"))
      (libsource (lib "eagle-import") (part "NPN_T_TO126_VERTICAL"))
    )
    (comp (ref "T805")
      (value "BD136")
      (footprint "eagle-import:T_TO126_VERTICAL")
      (fields (field (name "PART_CODE_BEL") "T_PAC_T_TO126_VERTICAL_VAL_BD136"))
      (libsource (lib "eagle-import") (part "PNP_T_TO126_VERTICAL"))
    )
    (comp (ref "T806")
      (value "BD135")
      (footprint "eagle-import:T_TO126_VERTICAL")
      (fields (field (name "PART_CODE_BEL") "T_PAC_T_TO126_VERTICAL_VAL_BD135"))
      (libsource (lib "eagle-import") (part "NPN_T_TO126_VERTICAL"))
    )
  )
  (nets
    (net (code "1") (name "+3V3") (class "Default")
      (node (ref "C101") (pin "1") (pinfunction "1_1") (pintype "passive"))
      (node (ref "C102") (pin "1") (pinfunction "1_1") (pintype "passive"))
      (node (ref "C103") (pin "1") (pinfunction "1_1") (pintype "passive"))
      (node (ref "C104") (pin "1") (pinfunction "1_1") (pintype "passive"))
      (node (ref "C105") (pin "1") (pinfunction "1_1") (pintype "passive"))
      (node (ref "C106") (pin "1") (pinfunction "1_1") (pintype "passive"))
      (node (ref "C107") (pin "1") (pinfunction "1_1") (pintype "passive"))
      (node (ref "C108") (pin "1") (pinfunction "1_1") (pintype "passive"))
      (node (ref "C110") (pin "1") (pinfunction "1_1") (pintype "passive"))
      (node (ref "C111") (pin "1") (pinfunction "1_1") (pintype "passive"))
      (node (ref "C112") (pin "+") (pinfunction "+_+") (pintype "passive"))
      (node (ref "C1202") (pin "1") (pinfunction "1_1") (pintype "passive"))
      (node (ref "D401") (pin "A") (pinfunction "A_A") (pintype "passive"))
      (node (ref "D402") (pin "A") (pinfunction "A_A") (pintype "passive"))
      (node (ref "D403") (pin "A") (pinfunction "A_A") (pintype "passive"))
      (node (ref "D404") (pin "A") (pinfunction "A_A") (pintype "passive"))
      (node (ref "D405") (pin "A") (pinfunction "A_A") (pintype "passive"))
      (node (ref "D406") (pin "A") (pinfunction "A_A") (pintype "passive"))
      (node (ref "D407") (pin "A") (pinfunction "A_A") (pintype "passive"))
      (node (ref "D408") (pin "A") (pinfunction "A_A") (pintype "passive"))
      (node (ref "D409") (pin "A") (pinfunction "A_A") (pintype "passive"))
      (node (ref "D410") (pin "A") (pinfunction "A_A") (pintype "passive"))
      (node (ref "D411") (pin "A") (pinfunction "A_A") (pintype "passive"))
      (node (ref "D412") (pin "A") (pinfunction "A_A") (pintype "passive"))
      (node (ref "D413") (pin "A") (pinfunction "A_A") (pintype "passive"))
      (node (ref "D414") (pin "A") (pinfunction "A_A") (pintype "passive"))
      (node (ref "IC1201") (pin "14") (pinfunction "VCC_14") (pintype "power_in"))
      (node (ref "IC201") (pin "1") (pinfunction "VCCIO_1_1") (pintype "power_in"))
      (node (ref "IC201") (pin "109") (pinfunction "VCCIO_5_109") (pintype "power_in"))
      (node (ref "IC201") (pin "127") (pinfunction "VCCIO_6_127") (pintype "power_in"))
      (node (ref "IC201") (pin "141") (pinfunction "VCCINT_3_141") (pintype "power_in"))
      (node (ref "IC201") (pin "37") (pinfunction "VCCIO_2_37") (pintype "power_in"))
      (node (ref "IC201") (pin "42") (pinfunction "VCCINT_1_42") (pintype "power_in"))
      (node (ref "IC201") (pin "55") (pinfunction "VCCIO_3_55") (pintype "passive"))
      (node (ref "IC201") (pin "73") (pinfunction "VCCIO_4_73") (pintype "power_in"))
      (node (ref "IC201") (pin "8") (pinfunction "VCCINT_VPP_8") (pintype "power_in"))
      (node (ref "IC201") (pin "84") (pinfunction "VCCINT_2_84") (pintype "power_in"))
      (node (ref "J1001") (pin "1") (pinfunction "1_1") (pintype "passive"))
      (node (ref "R101") (pin "2") (pinfunction "2_2") (pintype "passive"))
      (node (ref "R1103") (pin "1") (pinfunction "1_1") (pintype "passive"))
      (node (ref "R1104") (pin "1") (pinfunction "1_1") (pintype "passive"))
      (node (ref "RN1001") (pin "1") (pinfunction "1_1") (pintype "passive"))
      (node (ref "RN501") (pin "1") (pinfunction "1_1") (pintype "passive"))
      (node (ref "RN801") (pin "1") (pinfunction "1_1") (pintype "passive"))
      (node (ref "RN901") (pin "1") (pinfunction "1_1") (pintype "passive"))
      (node (ref "RN902") (pin "1") (pinfunction "1_1") (pintype "passive"))
      (node (ref "RN903") (pin "1") (pinfunction "1_1") (pintype "passive"))
      (node (ref "T501") (pin "E") (pinfunction "E_E") (pintype "passive"))
      (node (ref "T503") (pin "E") (pinfunction "E_E") (pintype "passive"))
      (node (ref "T505") (pin "E") (pinfunction "E_E") (pintype "passive"))
      (node (ref "T507") (pin "E") (pinfunction "E_E") (pintype "passive"))
      (node (ref "T601") (pin "E") (pinfunction "E_E") (pintype "passive"))
      (node (ref "T603") (pin "E") (pinfunction "E_E") (pintype "passive"))
      (node (ref "T605") (pin "E") (pinfunction "E_E") (pintype "passive"))
      (node (ref "T701") (pin "E") (pinfunction "E_E") (pintype "passive"))
      (node (ref "T703") (pin "E") (pinfunction "E_E") (pintype "passive"))
      (node (ref "T705") (pin "E") (pinfunction "E_E") (pintype "passive"))
      (node (ref "T801") (pin "E") (pinfunction "E_E") (pintype "passive"))
      (node (ref "T803") (pin "E") (pinfunction "E_E") (pintype "passive"))
      (node (ref "T805") (pin "E") (pinfunction "E_E") (pintype "passive"))
      (node (ref "TP107") (pin "1") (pinfunction "MP_1") (pintype "passive"))
      (node (ref "TP108") (pin "1") (pinfunction "MP_1") (pintype "passive"))
      (node (ref "TP109") (pin "1") (pinfunction "MP_1") (pintype "passive"))
      (node (ref "TP110") (pin "1") (pinfunction "MP_1") (pintype "passive"))
      (node (ref "TP115") (pin "1") (pinfunction "MP_1") (pintype "passive"))
      (node (ref "TP116") (pin "1") (pinfunction "MP_1") (pintype "passive"))
      (node (ref "TP117") (pin "1") (pinfunction "MP_1") (pintype "passive"))
      (node (ref "X101") (pin "1") (pinfunction "1_1") (pintype "passive"))
      (node (ref "X901") (pin "1") (pinfunction "1_1") (pintype "passive"))
      (node (ref "X901") (pin "3") (pinfunction "3_3") (pintype "passive"))
      (node (ref "X901") (pin "5") (pinfunction "5_5") (pintype "passive"))
    )
    (net (code "2") (name "+5V") (class "Default")
      (node (ref "C109") (pin "+") (pinfunction "+_+") (pintype "passive"))
      (node (ref "TP101") (pin "1") (pinfunction "MP_1") (pintype "passive"))
      (node (ref "TP102") (pin "1") (pinfunction "MP_1") (pintype "passive"))
      (node (ref "X101") (pin "2") (pinfunction "2_2") (pintype "passive"))
    )
    (net (code "17") (name "A0") (class "Default")
      (node (ref "IC201") (pin "19") (pinfunction "PB01_16_19") (pintype "bidirectional"))
      (node (ref "X1102") (pin "2") (pinfunction "2_2") (pintype "passive"))
    )
    (net (code "18") (name "A1") (class "Default")
      (node (ref "IC201") (pin "17") (pinfunction "PB01_14_17") (pintype "bidirectional"))
      (node (ref "X1102") (pin "4") (pinfunction "4_4") (pintype "passive"))
    )
    (net (code "19") (name "A2") (class "Default")
      (node (ref "IC201") (pin "16") (pinfunction "PB01_13_16") (pintype "bidirectional"))
      (node (ref "X1102") (pin "6") (pinfunction "6_6") (pintype "passive"))
    )
    (net (code "20") (name "A3") (class "Default")
      (node (ref "IC201") (pin "15") (pinfunction "PB01_11_15") (pintype "bidirectional"))
      (node (ref "X1102") (pin "8") (pinfunction "8_8") (pintype "passive"))
    )
    (net (code "21") (name "A4") (class "Default")
      (node (ref "IC201") (pin "14") (pinfunction "PB01_09_14") (pintype "bidirectional"))
      (node (ref "X1102") (pin "10") (pinfunction "10_10") (pintype "passive"))
    )
    (net (code "22") (name "A5") (class "Default")
      (node (ref "IC201") (pin "13") (pinfunction "PB01_07_13") (pintype "bidirectional"))
      (node (ref "X1102") (pin "12") (pinfunction "12_12") (pintype "passive"))
    )
    (net (code "23") (name "A6") (class "Default")
      (node (ref "IC201") (pin "12") (pinfunction "PB01_05_12") (pintype "bidirectional"))
      (node (ref "X1102") (pin "14") (pinfunction "14_14") (pintype "passive"))
    )
    (net (code "24") (name "A7") (class "Default")
      (node (ref "IC201") (pin "11") (pinfunction "PB01_04_11") (pintype "bidirectional"))
      (node (ref "X1102") (pin "16") (pinfunction "16_16") (pintype "passive"))
    )
    (net (code "25") (name "A8") (class "Default")
      (node (ref "IC201") (pin "10") (pinfunction "PB01_02_10") (pintype "bidirectional"))
      (node (ref "X1102") (pin "18") (pinfunction "18_18") (pintype "passive"))
    )
    (net (code "26") (name "A9") (class "Default")
      (node (ref "IC201") (pin "9") (pinfunction "PB01_01_9") (pintype "bidirectional"))
      (node (ref "X1102") (pin "20") (pinfunction "20_20") (pintype "passive"))
    )
    (net (code "27") (name "A10") (class "Default")
      (node (ref "IC201") (pin "7") (pinfunction "PB03_13_7") (pintype "bidirectional"))
      (node (ref "X1102") (pin "22") (pinfunction "22_22") (pintype "passive"))
    )
    (net (code "28") (name "A11") (class "Default")
      (node (ref "IC201") (pin "6") (pinfunction "PB03_11_GTS2_6") (pintype "bidirectional"))
      (node (ref "X1102") (pin "24") (pinfunction "24_24") (pintype "passive"))
    )
    (net (code "29") (name "A12") (class "Default")
      (node (ref "IC201") (pin "5") (pinfunction "PB03_07_GTS1_5") (pintype "bidirectional"))
      (node (ref "X1102") (pin "26") (pinfunction "26_26") (pintype "passive"))
    )
    (net (code "30") (name "A13") (class "Default")
      (node (ref "IC201") (pin "4") (pinfunction "PB03_05_4") (pintype "bidirectional"))
      (node (ref "X1102") (pin "28") (pinfunction "28_28") (pintype "passive"))
    )
    (net (code "31") (name "A14") (class "Default")
      (node (ref "IC201") (pin "3") (pinfunction "PB03_04_GTS4_3") (pintype "bidirectional"))
      (node (ref "X1102") (pin "30") (pinfunction "30_30") (pintype "passive"))
    )
    (net (code "32") (name "A15") (class "Default")
      (node (ref "IC201") (pin "2") (pinfunction "PB03_01_GTS3_2") (pintype "bidirectional"))
      (node (ref "X1102") (pin "32") (pinfunction "32_32") (pintype "passive"))
    )
    (net (code "33") (name "AC_SEL0") (class "Default")
      (node (ref "IC201") (pin "94") (pinfunction "PB15_05_94") (pintype "bidirectional"))
      (node (ref "RN701") (pin "1") (pinfunction "1_1") (pintype "passive"))
    )
    (net (code "34") (name "AC_SEL0_DRV") (class "Default")
      (node (ref "DIS302") (pin "5") (pinfunction "COM2_5") (pintype "passive"))
      (node (ref "T801") (pin "C") (pinfunction "C_C") (pintype "passive"))
      (node (ref "T802") (pin "C") (pinfunction "C_C") (pintype "passive"))
    )
    (net (code "35") (name "AC_SEL1") (class "Default")
      (node (ref "IC201") (pin "92") (pinfunction "PB15_02_92") (pintype "bidirectional"))
      (node (ref "RN701") (pin "3") (pinfunction "1_3") (pintype "passive"))
    )
    (net (code "36") (name "AC_SEL1_DRV") (class "Default")
      (node (ref "DIS302") (pin "4") (pinfunction "COM1_4") (pintype "passive"))
      (node (ref "T803") (pin "C") (pinfunction "C_C") (pintype "passive"))
      (node (ref "T804") (pin "C") (pinfunction "C_C") (pintype "passive"))
    )
    (net (code "37") (name "AC_SEL2") (class "Default")
      (node (ref "IC201") (pin "91") (pinfunction "PB15_01_91") (pintype "bidirectional"))
      (node (ref "RN701") (pin "5") (pinfunction "1_5") (pintype "passive"))
    )
    (net (code "38") (name "AC_SEL2_DRV") (class "Default")
      (node (ref "DIS301") (pin "5") (pinfunction "COM2_5") (pintype "passive"))
      (node (ref "T805") (pin "C") (pinfunction "C_C") (pintype "passive"))
      (node (ref "T806") (pin "C") (pinfunction "C_C") (pintype "passive"))
    )
    (net (code "39") (name "AC_SEL3") (class "Default")
      (node (ref "IC201") (pin "88") (pinfunction "PB14_16_88") (pintype "bidirectional"))
      (node (ref "RN701") (pin "7") (pinfunction "1_7") (pintype "passive"))
    )
    (net (code "40") (name "AC_SEL3_DRV") (class "Default")
      (node (ref "DIS301") (pin "4") (pinfunction "COM1_4") (pintype "passive"))
      (node (ref "T701") (pin "C") (pinfunction "C_C") (pintype "passive"))
      (node (ref "T702") (pin "C") (pinfunction "C_C") (pintype "passive"))
    )
    (net (code "41") (name "AC_SEL4") (class "Default")
      (node (ref "IC201") (pin "95") (pinfunction "PB15_07_95") (pintype "bidirectional"))
      (node (ref "RN702") (pin "1") (pinfunction "1_1") (pintype "passive"))
    )
    (net (code "42") (name "AC_SEL4_DRV") (class "Default")
      (node (ref "DIS303") (pin "5") (pinfunction "COM2_5") (pintype "passive"))
      (node (ref "T703") (pin "C") (pinfunction "C_C") (pintype "passive"))
      (node (ref "T704") (pin "C") (pinfunction "C_C") (pintype "passive"))
    )
    (net (code "43") (name "AC_SEL5") (class "Default")
      (node (ref "IC201") (pin "93") (pinfunction "PB15_04_93") (pintype "bidirectional"))
      (node (ref "RN702") (pin "3") (pinfunction "1_3") (pintype "passive"))
    )
    (net (code "44") (name "AC_SEL5_DRV") (class "Default")
      (node (ref "DIS303") (pin "4") (pinfunction "COM1_4") (pintype "passive"))
      (node (ref "T705") (pin "C") (pinfunction "C_C") (pintype "passive"))
      (node (ref "T706") (pin "C") (pinfunction "C_C") (pintype "passive"))
    )
    (net (code "45") (name "AC_SEL_B0") (class "Default")
      (node (ref "RN701") (pin "2") (pinfunction "2_2") (pintype "passive"))
      (node (ref "RN801") (pin "2") (pinfunction "2_2") (pintype "passive"))
      (node (ref "RN802") (pin "2") (pinfunction "2_2") (pintype "passive"))
      (node (ref "T801") (pin "B") (pinfunction "B_B") (pintype "passive"))
      (node (ref "T802") (pin "B") (pinfunction "B_B") (pintype "passive"))
    )
    (net (code "46") (name "AC_SEL_B1") (class "Default")
      (node (ref "RN701") (pin "4") (pinfunction "2_4") (pintype "passive"))
      (node (ref "RN801") (pin "3") (pinfunction "3_3") (pintype "passive"))
      (node (ref "RN802") (pin "3") (pinfunction "3_3") (pintype "passive"))
      (node (ref "T803") (pin "B") (pinfunction "B_B") (pintype "passive"))
      (node (ref "T804") (pin "B") (pinfunction "B_B") (pintype "passive"))
    )
    (net (code "47") (name "AC_SEL_B2") (class "Default")
      (node (ref "RN701") (pin "6") (pinfunction "2_6") (pintype "passive"))
      (node (ref "RN801") (pin "4") (pinfunction "4_4") (pintype "passive"))
      (node (ref "RN802") (pin "4") (pinfunction "4_4") (pintype "passive"))
      (node (ref "T805") (pin "B") (pinfunction "B_B") (pintype "passive"))
      (node (ref "T806") (pin "B") (pinfunction "B_B") (pintype "passive"))
    )
    (net (code "48") (name "AC_SEL_B3") (class "Default")
      (node (ref "RN701") (pin "8") (pinfunction "2_8") (pintype "passive"))
      (node (ref "RN801") (pin "5") (pinfunction "5_5") (pintype "passive"))
      (node (ref "RN802") (pin "5") (pinfunction "5_5") (pintype "passive"))
      (node (ref "T701") (pin "B") (pinfunction "B_B") (pintype "passive"))
      (node (ref "T702") (pin "B") (pinfunction "B_B") (pintype "passive"))
    )
    (net (code "49") (name "AC_SEL_B4") (class "Default")
      (node (ref "RN702") (pin "2") (pinfunction "2_2") (pintype "passive"))
      (node (ref "RN801") (pin "6") (pinfunction "6_6") (pintype "passive"))
      (node (ref "RN802") (pin "6") (pinfunction "6_6") (pintype "passive"))
      (node (ref "T703") (pin "B") (pinfunction "B_B") (pintype "passive"))
      (node (ref "T704") (pin "B") (pinfunction "B_B") (pintype "passive"))
    )
    (net (code "50") (name "AC_SEL_B5") (class "Default")
      (node (ref "RN702") (pin "4") (pinfunction "2_4") (pintype "passive"))
      (node (ref "RN801") (pin "7") (pinfunction "7_7") (pintype "passive"))
      (node (ref "RN802") (pin "7") (pinfunction "7_7") (pintype "passive"))
      (node (ref "T705") (pin "B") (pinfunction "B_B") (pintype "passive"))
      (node (ref "T706") (pin "B") (pinfunction "B_B") (pintype "passive"))
    )
    (net (code "51") (name "A_EX0") (class "Default")
      (node (ref "IC201") (pin "142") (pinfunction "PB05_13_142") (pintype "bidirectional"))
      (node (ref "X1104") (pin "2") (pinfunction "2_2") (pintype "passive"))
    )
    (net (code "52") (name "A_EX1") (class "Default")
      (node (ref "IC201") (pin "140") (pinfunction "PB05_09_140") (pintype "bidirectional"))
      (node (ref "X1104") (pin "4") (pinfunction "4_4") (pintype "passive"))
    )
    (net (code "53") (name "A_EX2") (class "Default")
      (node (ref "IC201") (pin "139") (pinfunction "PB05_07_139") (pintype "bidirectional"))
      (node (ref "X1104") (pin "6") (pinfunction "6_6") (pintype "passive"))
    )
    (net (code "54") (name "A_EX3") (class "Default")
      (node (ref "IC201") (pin "138") (pinfunction "PB05_05_138") (pintype "bidirectional"))
      (node (ref "X1104") (pin "8") (pinfunction "8_8") (pintype "passive"))
    )
    (net (code "55") (name "A_EX4") (class "Default")
      (node (ref "IC201") (pin "137") (pinfunction "PB05_04_137") (pintype "bidirectional"))
      (node (ref "X1104") (pin "10") (pinfunction "10_10") (pintype "passive"))
    )
    (net (code "56") (name "A_EX5") (class "Default")
      (node (ref "IC201") (pin "136") (pinfunction "PB05_02_136") (pintype "bidirectional"))
      (node (ref "X1104") (pin "12") (pinfunction "12_12") (pintype "passive"))
    )
    (net (code "57") (name "A_EX6") (class "Default")
      (node (ref "IC201") (pin "135") (pinfunction "PB05_01_135") (pintype "bidirectional"))
      (node (ref "X1104") (pin "14") (pinfunction "14_14") (pintype "passive"))
    )
    (net (code "58") (name "A_EX7") (class "Default")
      (node (ref "IC201") (pin "134") (pinfunction "PB07_09_134") (pintype "bidirectional"))
      (node (ref "X1104") (pin "16") (pinfunction "16_16") (pintype "passive"))
    )
    (net (code "59") (name "A_EX8") (class "Default")
      (node (ref "IC201") (pin "133") (pinfunction "PB07_07_133") (pintype "bidirectional"))
      (node (ref "X1104") (pin "18") (pinfunction "18_18") (pintype "passive"))
    )
    (net (code "60") (name "A_EX9") (class "Default")
      (node (ref "IC201") (pin "132") (pinfunction "PB07_04_132") (pintype "bidirectional"))
      (node (ref "X1104") (pin "20") (pinfunction "20_20") (pintype "passive"))
    )
    (net (code "61") (name "A_EX10") (class "Default")
      (node (ref "IC201") (pin "131") (pinfunction "PB07_02_131") (pintype "bidirectional"))
      (node (ref "X1104") (pin "22") (pinfunction "22_22") (pintype "passive"))
    )
    (net (code "62") (name "A_EX11") (class "Default")
      (node (ref "IC201") (pin "130") (pinfunction "PB07_01_130") (pintype "bidirectional"))
      (node (ref "X1104") (pin "24") (pinfunction "24_24") (pintype "passive"))
    )
    (net (code "63") (name "A_EX12") (class "Default")
      (node (ref "IC201") (pin "129") (pinfunction "PB09_16_129") (pintype "bidirectional"))
      (node (ref "X1104") (pin "26") (pinfunction "26_26") (pintype "passive"))
    )
    (net (code "64") (name "A_EX13") (class "Default")
      (node (ref "IC201") (pin "128") (pinfunction "PB09_13_128") (pintype "bidirectional"))
      (node (ref "X1104") (pin "28") (pinfunction "28_28") (pintype "passive"))
    )
    (net (code "65") (name "A_EX14") (class "Default")
      (node (ref "IC201") (pin "126") (pinfunction "PB09_11_126") (pintype "bidirectional"))
      (node (ref "X1104") (pin "30") (pinfunction "30_30") (pintype "passive"))
    )
    (net (code "66") (name "A_EX15") (class "Default")
      (node (ref "IC201") (pin "125") (pinfunction "PB09_10_125") (pintype "bidirectional"))
      (node (ref "X1104") (pin "32") (pinfunction "32_32") (pintype "passive"))
    )
    (net (code "67") (name "CLK_OSC") (class "Default")
      (node (ref "IC1201") (pin "3") (pinfunction "O_3") (pintype "output"))
      (node (ref "IC201") (pin "30") (pinfunction "PB02_09_GCK1_30") (pintype "bidirectional"))
      (node (ref "TP1201") (pin "1") (pinfunction "MP_1") (pintype "passive"))
    )
    (net (code "68") (name "CPU_CLK") (class "Default")
      (node (ref "IC201") (pin "38") (pinfunction "PB04_07_GCK3_38") (pintype "bidirectional"))
      (node (ref "X1101") (pin "40") (pinfunction "40_40") (pintype "passive"))
    )
    (net (code "69") (name "CPU_RESET") (class "Default")
      (node (ref "IC201") (pin "143") (pinfunction "PB05_14_GSR_143") (pintype "bidirectional"))
      (node (ref "R1101") (pin "2") (pinfunction "2_2") (pintype "passive"))
    )
    (net (code "70") (name "CPU_RSV0") (class "Default")
      (node (ref "X1101") (pin "18") (pinfunction "18_18") (pintype "passive"))
    )
    (net (code "71") (name "D0") (class "Default")
      (node (ref "IC201") (pin "27") (pinfunction "PB00_16_27") (pintype "bidirectional"))
      (node (ref "X1101") (pin "2") (pinfunction "2_2") (pintype "passive"))
    )
    (net (code "72") (name "D1") (class "Default")
      (node (ref "IC201") (pin "26") (pinfunction "PB00_14_26") (pintype "bidirectional"))
      (node (ref "X1101") (pin "4") (pinfunction "4_4") (pintype "passive"))
    )
    (net (code "73") (name "D2") (class "Default")
      (node (ref "IC201") (pin "25") (pinfunction "PB00_13_25") (pintype "bidirectional"))
      (node (ref "X1101") (pin "6") (pinfunction "6_6") (pintype "passive"))
    )
    (net (code "74") (name "D3") (class "Default")
      (node (ref "IC201") (pin "24") (pinfunction "PB00_11_24") (pintype "bidirectional"))
      (node (ref "X1101") (pin "8") (pinfunction "8_8") (pintype "passive"))
    )
    (net (code "75") (name "D4") (class "Default")
      (node (ref "IC201") (pin "23") (pinfunction "PB00_09_23") (pintype "bidirectional"))
      (node (ref "X1101") (pin "10") (pinfunction "10_10") (pintype "passive"))
    )
    (net (code "76") (name "D5") (class "Default")
      (node (ref "IC201") (pin "22") (pinfunction "PB00_07_22") (pintype "bidirectional"))
      (node (ref "X1101") (pin "12") (pinfunction "12_12") (pintype "passive"))
    )
    (net (code "77") (name "D6") (class "Default")
      (node (ref "IC201") (pin "21") (pinfunction "PB00_05_21") (pintype "bidirectional"))
      (node (ref "X1101") (pin "14") (pinfunction "14_14") (pintype "passive"))
    )
    (net (code "78") (name "D7") (class "Default")
      (node (ref "IC201") (pin "20") (pinfunction "PB00_04_20") (pintype "bidirectional"))
      (node (ref "X1101") (pin "16") (pinfunction "16_16") (pintype "passive"))
    )
    (net (code "79") (name "DEBUG0") (class "Default")
      (node (ref "IC201") (pin "79") (pinfunction "PB14_01_79") (pintype "bidirectional"))
      (node (ref "R401") (pin "2") (pinfunction "2_2") (pintype "passive"))
      (node (ref "RN903") (pin "2") (pinfunction "2_2") (pintype "passive"))
      (node (ref "S904") (pin "4") (pinfunction "4_4") (pintype "passive"))
      (node (ref "X901") (pin "18") (pinfunction "18_18") (pintype "passive"))
    )
    (net (code "80") (name "DEBUG1") (class "Default")
      (node (ref "IC201") (pin "78") (pinfunction "PB12_16_78") (pintype "bidirectional"))
      (node (ref "R403") (pin "2") (pinfunction "2_2") (pintype "passive"))
      (node (ref "RN903") (pin "3") (pinfunction "3_3") (pintype "passive"))
      (node (ref "S904") (pin "5") (pinfunction "5_5") (pintype "passive"))
      (node (ref "X901") (pin "24") (pinfunction "24_24") (pintype "passive"))
    )
    (net (code "81") (name "DEBUG2") (class "Default")
      (node (ref "IC201") (pin "77") (pinfunction "PB12_14_77") (pintype "bidirectional"))
      (node (ref "R405") (pin "2") (pinfunction "2_2") (pintype "passive"))
      (node (ref "RN903") (pin "4") (pinfunction "4_4") (pintype "passive"))
      (node (ref "S904") (pin "6") (pinfunction "6_6") (pintype "passive"))
      (node (ref "X901") (pin "26") (pinfunction "26_26") (pintype "passive"))
    )
    (net (code "82") (name "DEBUG3") (class "Default")
      (node (ref "IC201") (pin "76") (pinfunction "PB12_13_76") (pintype "bidirectional"))
      (node (ref "R406") (pin "2") (pinfunction "2_2") (pintype "passive"))
      (node (ref "RN903") (pin "5") (pinfunction "5_5") (pintype "passive"))
      (node (ref "X901") (pin "28") (pinfunction "28_28") (pintype "passive"))
    )
    (net (code "83") (name "DEBUG4") (class "Default")
      (node (ref "IC201") (pin "75") (pinfunction "PB12_10_75") (pintype "bidirectional"))
      (node (ref "R407") (pin "2") (pinfunction "2_2") (pintype "passive"))
      (node (ref "RN903") (pin "6") (pinfunction "6_6") (pintype "passive"))
      (node (ref "X901") (pin "30") (pinfunction "30_30") (pintype "passive"))
    )
    (net (code "84") (name "DEBUG5") (class "Default")
      (node (ref "IC201") (pin "74") (pinfunction "PB12_07_74") (pintype "bidirectional"))
      (node (ref "R408") (pin "2") (pinfunction "2_2") (pintype "passive"))
      (node (ref "RN903") (pin "7") (pinfunction "7_7") (pintype "passive"))
      (node (ref "X901") (pin "36") (pinfunction "36_36") (pintype "passive"))
    )
    (net (code "85") (name "DEBUG6") (class "Default")
      (node (ref "IC201") (pin "58") (pinfunction "PB08_13_58") (pintype "bidirectional"))
      (node (ref "R409") (pin "2") (pinfunction "2_2") (pintype "passive"))
      (node (ref "RN903") (pin "8") (pinfunction "8_8") (pintype "passive"))
    )
    (net (code "86") (name "DEBUG7") (class "Default")
      (node (ref "IC201") (pin "59") (pinfunction "PB08_16_59") (pintype "bidirectional"))
      (node (ref "R410") (pin "2") (pinfunction "2_2") (pintype "passive"))
      (node (ref "RN903") (pin "9") (pinfunction "9_9") (pintype "passive"))
    )
    (net (code "87") (name "DEBUG8") (class "Default")
      (node (ref "IC201") (pin "60") (pinfunction "PB10_02_60") (pintype "bidirectional"))
      (node (ref "R411") (pin "2") (pinfunction "2_2") (pintype "passive"))
    )
    (net (code "88") (name "DEBUG9") (class "Default")
      (node (ref "IC201") (pin "61") (pinfunction "PB10_04_61") (pintype "bidirectional"))
      (node (ref "R412") (pin "2") (pinfunction "2_2") (pintype "passive"))
    )
    (net (code "89") (name "DEBUG10") (class "Default")
      (node (ref "IC201") (pin "64") (pinfunction "PB10_09_64") (pintype "bidirectional"))
      (node (ref "R413") (pin "2") (pinfunction "2_2") (pintype "passive"))
    )
    (net (code "90") (name "DEBUG11") (class "Default")
      (node (ref "IC201") (pin "71") (pinfunction "PB12_01_71") (pintype "bidirectional"))
      (node (ref "R414") (pin "2") (pinfunction "2_2") (pintype "passive"))
    )
    (net (code "91") (name "D_EX0") (class "Default")
      (node (ref "IC201") (pin "124") (pinfunction "PB09_09_124") (pintype "bidirectional"))
      (node (ref "X1103") (pin "2") (pinfunction "2_2") (pintype "passive"))
    )
    (net (code "92") (name "D_EX1") (class "Default")
      (node (ref "IC201") (pin "121") (pinfunction "PB09_07_121") (pintype "bidirectional"))
      (node (ref "X1103") (pin "4") (pinfunction "4_4") (pintype "passive"))
    )
    (net (code "93") (name "D_EX2") (class "Default")
      (node (ref "IC201") (pin "120") (pinfunction "PB09_05_120") (pintype "bidirectional"))
      (node (ref "X1103") (pin "6") (pinfunction "6_6") (pintype "passive"))
    )
    (net (code "94") (name "D_EX3") (class "Default")
      (node (ref "IC201") (pin "119") (pinfunction "PB09_04_119") (pintype "bidirectional"))
      (node (ref "X1103") (pin "8") (pinfunction "8_8") (pintype "passive"))
    )
    (net (code "95") (name "D_EX4") (class "Default")
      (node (ref "IC201") (pin "118") (pinfunction "PB09_02_118") (pintype "bidirectional"))
      (node (ref "X1103") (pin "10") (pinfunction "10_10") (pintype "passive"))
    )
    (net (code "96") (name "D_EX5") (class "Default")
      (node (ref "IC201") (pin "117") (pinfunction "PB09_01_117") (pintype "bidirectional"))
      (node (ref "X1103") (pin "12") (pinfunction "12_12") (pintype "passive"))
    )
    (net (code "97") (name "D_EX6") (class "Default")
      (node (ref "IC201") (pin "116") (pinfunction "PB11_11_116") (pintype "bidirectional"))
      (node (ref "X1103") (pin "14") (pinfunction "14_14") (pintype "passive"))
    )
    (net (code "98") (name "D_EX7") (class "Default")
      (node (ref "IC201") (pin "115") (pinfunction "PB11_09_115") (pintype "bidirectional"))
      (node (ref "X1103") (pin "16") (pinfunction "16_16") (pintype "passive"))
    )
    (net (code "99") (name "EXT_IEI") (class "Default")
      (node (ref "IC201") (pin "113") (pinfunction "PB11_07_113") (pintype "bidirectional"))
      (node (ref "X1104") (pin "34") (pinfunction "34_34") (pintype "passive"))
    )
    (net (code "100") (name "EX_CLK") (class "Default")
      (node (ref "IC201") (pin "97") (pinfunction "PB15_10_97") (pintype "bidirectional"))
      (node (ref "X1103") (pin "40") (pinfunction "40_40") (pintype "passive"))
    )
    (net (code "101") (name "GND") (class "Default")
      (node (ref "C101") (pin "2") (pinfunction "2_2") (pintype "passive"))
      (node (ref "C102") (pin "2") (pinfunction "2_2") (pintype "passive"))
      (node (ref "C103") (pin "2") (pinfunction "2_2") (pintype "passive"))
      (node (ref "C104") (pin "2") (pinfunction "2_2") (pintype "passive"))
      (node (ref "C105") (pin "2") (pinfunction "2_2") (pintype "passive"))
      (node (ref "C106") (pin "2") (pinfunction "2_2") (pintype "passive"))
      (node (ref "C107") (pin "2") (pinfunction "2_2") (pintype "passive"))
      (node (ref "C108") (pin "2") (pinfunction "2_2") (pintype "passive"))
      (node (ref "C109") (pin "-") (pinfunction "-_-") (pintype "passive"))
      (node (ref "C110") (pin "2") (pinfunction "2_2") (pintype "passive"))
      (node (ref "C111") (pin "2") (pinfunction "2_2") (pintype "passive"))
      (node (ref "C112") (pin "-") (pinfunction "-_-") (pintype "passive"))
      (node (ref "C1201") (pin "2") (pinfunction "2_2") (pintype "passive"))
      (node (ref "C1202") (pin "2") (pinfunction "2_2") (pintype "passive"))
      (node (ref "D101") (pin "C") (pinfunction "C_C") (pintype "passive"))
      (node (ref "H101") (pin "H1") (pinfunction "MOUNT_H1") (pintype "passive"))
      (node (ref "H102") (pin "H1") (pinfunction "MOUNT_H1") (pintype "passive"))
      (node (ref "H103") (pin "H1") (pinfunction "MOUNT_H1") (pintype "passive"))
      (node (ref "H104") (pin "H1") (pinfunction "MOUNT_H1") (pintype "passive"))
      (node (ref "IC1201") (pin "7") (pinfunction "GND_7") (pintype "power_in"))
      (node (ref "IC201") (pin "108") (pinfunction "VSSIO_6_108") (pintype "power_in"))
      (node (ref "IC201") (pin "114") (pinfunction "VSSINT_5_114") (pintype "power_in"))
      (node (ref "IC201") (pin "123") (pinfunction "VSSIO_7_123") (pintype "power_in"))
      (node (ref "IC201") (pin "144") (pinfunction "VSSIO_8_144") (pintype "power_in"))
      (node (ref "IC201") (pin "18") (pinfunction "VSSINT_1_18") (pintype "power_in"))
      (node (ref "IC201") (pin "29") (pinfunction "VSSINT_2_29") (pintype "power_in"))
      (node (ref "IC201") (pin "36") (pinfunction "VSSIO_1_36") (pintype "power_in"))
      (node (ref "IC201") (pin "47") (pinfunction "VSSIO_2_47") (pintype "power_in"))
      (node (ref "IC201") (pin "62") (pinfunction "VSSINT_3_62") (pintype "power_in"))
      (node (ref "IC201") (pin "72") (pinfunction "VSSIO_3_72") (pintype "power_in"))
      (node (ref "IC201") (pin "89") (pinfunction "VSSIO_4_89") (pintype "power_in"))
      (node (ref "IC201") (pin "90") (pinfunction "VSSINT_4_90") (pintype "power_in"))
      (node (ref "IC201") (pin "99") (pinfunction "VSSIO_5_99") (pintype "power_in"))
      (node (ref "R1001") (pin "2") (pinfunction "2_2") (pintype "passive"))
      (node (ref "R1002") (pin "2") (pinfunction "2_2") (pintype "passive"))
      (node (ref "R1102") (pin "2") (pinfunction "2_2") (pintype "passive"))
      (node (ref "RN502") (pin "1") (pinfunction "1_1") (pintype "passive"))
      (node (ref "RN802") (pin "1") (pinfunction "1_1") (pintype "passive"))
      (node (ref "S901") (pin "2") (pinfunction "B1_2") (pintype "passive"))
      (node (ref "S901") (pin "4") (pinfunction "B1_4") (pintype "passive"))
      (node (ref "S902") (pin "2") (pinfunction "B1_2") (pintype "passive"))
      (node (ref "S902") (pin "4") (pinfunction "B1_4") (pintype "passive"))
      (node (ref "S903") (pin "2") (pinfunction "B1_2") (pintype "passive"))
      (node (ref "S903") (pin "4") (pinfunction "B1_4") (pintype "passive"))
      (node (ref "S904") (pin "10") (pinfunction "10_10") (pintype "passive"))
      (node (ref "S904") (pin "11") (pinfunction "11_11") (pintype "passive"))
      (node (ref "S904") (pin "12") (pinfunction "12_12") (pintype "passive"))
      (node (ref "S904") (pin "13") (pinfunction "13_13") (pintype "passive"))
      (node (ref "S904") (pin "14") (pinfunction "14_14") (pintype "passive"))
      (node (ref "S904") (pin "15") (pinfunction "15_15") (pintype "passive"))
      (node (ref "S904") (pin "16") (pinfunction "16_16") (pintype "passive"))
      (node (ref "S904") (pin "9") (pinfunction "9_9") (pintype "passive"))
      (node (ref "T1101") (pin "E") (pinfunction "E_E") (pintype "passive"))
      (node (ref "T502") (pin "E") (pinfunction "E_E") (pintype "passive"))
      (node (ref "T504") (pin "E") (pinfunction "E_E") (pintype "passive"))
      (node (ref "T506") (pin "E") (pinfunction "E_E") (pintype "passive"))
      (node (ref "T508") (pin "E") (pinfunction "E_E") (pintype "passive"))
      (node (ref "T602") (pin "E") (pinfunction "E_E") (pintype "passive"))
      (node (ref "T604") (pin "E") (pinfunction "E_E") (pintype "passive"))
      (node (ref "T606") (pin "E") (pinfunction "E_E") (pintype "passive"))
      (node (ref "T702") (pin "E") (pinfunction "E_E") (pintype "passive"))
      (node (ref "T704") (pin "E") (pinfunction "E_E") (pintype "passive"))
      (node (ref "T706") (pin "E") (pinfunction "E_E") (pintype "passive"))
      (node (ref "T802") (pin "E") (pinfunction "E_E") (pintype "passive"))
      (node (ref "T804") (pin "E") (pinfunction "E_E") (pintype "passive"))
      (node (ref "T806") (pin "E") (pinfunction "E_E") (pintype "passive"))
      (node (ref "TP103") (pin "1") (pinfunction "MP_1") (pintype "passive"))
      (node (ref "TP104") (pin "1") (pinfunction "MP_1") (pintype "passive"))
      (node (ref "TP105") (pin "1") (pinfunction "MP_1") (pintype "passive"))
      (node (ref "TP106") (pin "1") (pinfunction "MP_1") (pintype "passive"))
      (node (ref "TP127") (pin "1") (pinfunction "MP_1") (pintype "passive"))
      (node (ref "TP128") (pin "1") (pinfunction "MP_1") (pintype "passive"))
      (node (ref "TP129") (pin "1") (pinfunction "MP_1") (pintype "passive"))
      (node (ref "X1001") (pin "2") (pinfunction "2_2") (pintype "passive"))
      (node (ref "X1001") (pin "4") (pinfunction "4_4") (pintype "passive"))
      (node (ref "X1001") (pin "6") (pinfunction "6_6") (pintype "passive"))
      (node (ref "X1001") (pin "8") (pinfunction "8_8") (pintype "passive"))
      (node (ref "X101") (pin "3") (pinfunction "3_3") (pintype "passive"))
      (node (ref "X101") (pin "4") (pinfunction "4_4") (pintype "passive"))
      (node (ref "X1101") (pin "1") (pinfunction "1_1") (pintype "passive"))
      (node (ref "X1101") (pin "11") (pinfunction "11_11") (pintype "passive"))
      (node (ref "X1101") (pin "13") (pinfunction "13_13") (pintype "passive"))
      (node (ref "X1101") (pin "15") (pinfunction "15_15") (pintype "passive"))
      (node (ref "X1101") (pin "17") (pinfunction "17_17") (pintype "passive"))
      (node (ref "X1101") (pin "19") (pinfunction "19_19") (pintype "passive"))
      (node (ref "X1101") (pin "21") (pinfunction "21_21") (pintype "passive"))
      (node (ref "X1101") (pin "23") (pinfunction "23_23") (pintype "passive"))
      (node (ref "X1101") (pin "25") (pinfunction "25_25") (pintype "passive"))
      (node (ref "X1101") (pin "27") (pinfunction "27_27") (pintype "passive"))
      (node (ref "X1101") (pin "29") (pinfunction "29_29") (pintype "passive"))
      (node (ref "X1101") (pin "3") (pinfunction "3_3") (pintype "passive"))
      (node (ref "X1101") (pin "31") (pinfunction "31_31") (pintype "passive"))
      (node (ref "X1101") (pin "33") (pinfunction "33_33") (pintype "passive"))
      (node (ref "X1101") (pin "35") (pinfunction "35_35") (pintype "passive"))
      (node (ref "X1101") (pin "37") (pinfunction "37_37") (pintype "passive"))
      (node (ref "X1101") (pin "39") (pinfunction "39_39") (pintype "passive"))
      (node (ref "X1101") (pin "5") (pinfunction "5_5") (pintype "passive"))
      (node (ref "X1101") (pin "7") (pinfunction "7_7") (pintype "passive"))
      (node (ref "X1101") (pin "9") (pinfunction "9_9") (pintype "passive"))
      (node (ref "X1102") (pin "1") (pinfunction "1_1") (pintype "passive"))
      (node (ref "X1102") (pin "11") (pinfunction "11_11") (pintype "passive"))
      (node (ref "X1102") (pin "13") (pinfunction "13_13") (pintype "passive"))
      (node (ref "X1102") (pin "15") (pinfunction "15_15") (pintype "passive"))
      (node (ref "X1102") (pin "17") (pinfunction "17_17") (pintype "passive"))
      (node (ref "X1102") (pin "19") (pinfunction "19_19") (pintype "passive"))
      (node (ref "X1102") (pin "21") (pinfunction "21_21") (pintype "passive"))
      (node (ref "X1102") (pin "23") (pinfunction "23_23") (pintype "passive"))
      (node (ref "X1102") (pin "25") (pinfunction "25_25") (pintype "passive"))
      (node (ref "X1102") (pin "27") (pinfunction "27_27") (pintype "passive"))
      (node (ref "X1102") (pin "29") (pinfunction "29_29") (pintype "passive"))
      (node (ref "X1102") (pin "3") (pinfunction "3_3") (pintype "passive"))
      (node (ref "X1102") (pin "31") (pinfunction "31_31") (pintype "passive"))
      (node (ref "X1102") (pin "33") (pinfunction "33_33") (pintype "passive"))
      (node (ref "X1102") (pin "35") (pinfunction "35_35") (pintype "passive"))
      (node (ref "X1102") (pin "37") (pinfunction "37_37") (pintype "passive"))
      (node (ref "X1102") (pin "39") (pinfunction "39_39") (pintype "passive"))
      (node (ref "X1102") (pin "5") (pinfunction "5_5") (pintype "passive"))
      (node (ref "X1102") (pin "7") (pinfunction "7_7") (pintype "passive"))
      (node (ref "X1102") (pin "9") (pinfunction "9_9") (pintype "passive"))
      (node (ref "X1103") (pin "1") (pinfunction "1_1") (pintype "passive"))
      (node (ref "X1103") (pin "11") (pinfunction "11_11") (pintype "passive"))
      (node (ref "X1103") (pin "13") (pinfunction "13_13") (pintype "passive"))
      (node (ref "X1103") (pin "15") (pinfunction "15_15") (pintype "passive"))
      (node (ref "X1103") (pin "17") (pinfunction "17_17") (pintype "passive"))
      (node (ref "X1103") (pin "19") (pinfunction "19_19") (pintype "passive"))
      (node (ref "X1103") (pin "21") (pinfunction "21_21") (pintype "passive"))
      (node (ref "X1103") (pin "23") (pinfunction "23_23") (pintype "passive"))
      (node (ref "X1103") (pin "25") (pinfunction "25_25") (pintype "passive"))
      (node (ref "X1103") (pin "27") (pinfunction "27_27") (pintype "passive"))
      (node (ref "X1103") (pin "29") (pinfunction "29_29") (pintype "passive"))
      (node (ref "X1103") (pin "3") (pinfunction "3_3") (pintype "passive"))
      (node (ref "X1103") (pin "31") (pinfunction "31_31") (pintype "passive"))
      (node (ref "X1103") (pin "33") (pinfunction "33_33") (pintype "passive"))
      (node (ref "X1103") (pin "35") (pinfunction "35_35") (pintype "passive"))
      (node (ref "X1103") (pin "37") (pinfunction "37_37") (pintype "passive"))
      (node (ref "X1103") (pin "39") (pinfunction "39_39") (pintype "passive"))
      (node (ref "X1103") (pin "5") (pinfunction "5_5") (pintype "passive"))
      (node (ref "X1103") (pin "7") (pinfunction "7_7") (pintype "passive"))
      (node (ref "X1103") (pin "9") (pinfunction "9_9") (pintype "passive"))
      (node (ref "X1104") (pin "1") (pinfunction "1_1") (pintype "passive"))
      (node (ref "X1104") (pin "11") (pinfunction "11_11") (pintype "passive"))
      (node (ref "X1104") (pin "13") (pinfunction "13_13") (pintype "passive"))
      (node (ref "X1104") (pin "15") (pinfunction "15_15") (pintype "passive"))
      (node (ref "X1104") (pin "17") (pinfunction "17_17") (pintype "passive"))
      (node (ref "X1104") (pin "19") (pinfunction "19_19") (pintype "passive"))
      (node (ref "X1104") (pin "21") (pinfunction "21_21") (pintype "passive"))
      (node (ref "X1104") (pin "23") (pinfunction "23_23") (pintype "passive"))
      (node (ref "X1104") (pin "25") (pinfunction "25_25") (pintype "passive"))
      (node (ref "X1104") (pin "27") (pinfunction "27_27") (pintype "passive"))
      (node (ref "X1104") (pin "29") (pinfunction "29_29") (pintype "passive"))
      (node (ref "X1104") (pin "3") (pinfunction "3_3") (pintype "passive"))
      (node (ref "X1104") (pin "31") (pinfunction "31_31") (pintype "passive"))
      (node (ref "X1104") (pin "33") (pinfunction "33_33") (pintype "passive"))
      (node (ref "X1104") (pin "35") (pinfunction "35_35") (pintype "passive"))
      (node (ref "X1104") (pin "37") (pinfunction "37_37") (pintype "passive"))
      (node (ref "X1104") (pin "39") (pinfunction "39_39") (pintype "passive"))
      (node (ref "X1104") (pin "5") (pinfunction "5_5") (pintype "passive"))
      (node (ref "X1104") (pin "7") (pinfunction "7_7") (pintype "passive"))
      (node (ref "X1104") (pin "9") (pinfunction "9_9") (pintype "passive"))
      (node (ref "X901") (pin "11") (pinfunction "11_11") (pintype "passive"))
      (node (ref "X901") (pin "13") (pinfunction "13_13") (pintype "passive"))
      (node (ref "X901") (pin "15") (pinfunction "15_15") (pintype "passive"))
      (node (ref "X901") (pin "17") (pinfunction "17_17") (pintype "passive"))
      (node (ref "X901") (pin "19") (pinfunction "19_19") (pintype "passive"))
      (node (ref "X901") (pin "21") (pinfunction "21_21") (pintype "passive"))
      (node (ref "X901") (pin "23") (pinfunction "23_23") (pintype "passive"))
      (node (ref "X901") (pin "25") (pinfunction "25_25") (pintype "passive"))
      (node (ref "X901") (pin "27") (pinfunction "27_27") (pintype "passive"))
      (node (ref "X901") (pin "29") (pinfunction "29_29") (pintype "passive"))
      (node (ref "X901") (pin "31") (pinfunction "31_31") (pintype "passive"))
      (node (ref "X901") (pin "33") (pinfunction "33_33") (pintype "passive"))
      (node (ref "X901") (pin "35") (pinfunction "35_35") (pintype "passive"))
      (node (ref "X901") (pin "37") (pinfunction "37_37") (pintype "passive"))
      (node (ref "X901") (pin "39") (pinfunction "39_39") (pintype "passive"))
      (node (ref "X901") (pin "9") (pinfunction "9_9") (pintype "passive"))
    )
    (net (code "102") (name "IEI") (class "Default")
      (node (ref "IC201") (pin "46") (pinfunction "PB06_04_46") (pintype "bidirectional"))
      (node (ref "X1102") (pin "34") (pinfunction "34_34") (pintype "passive"))
    )
    (net (code "103") (name "Net-(D101-PadA)") (class "Default")
      (node (ref "D101") (pin "A") (pinfunction "A_A") (pintype "passive"))
      (node (ref "R101") (pin "1") (pinfunction "1_1") (pintype "passive"))
    )
    (net (code "104") (name "Net-(D401-PadC)") (class "Default")
      (node (ref "D401") (pin "C") (pinfunction "C_C") (pintype "passive"))
      (node (ref "R401") (pin "1") (pinfunction "1_1") (pintype "passive"))
    )
    (net (code "105") (name "Net-(D402-PadC)") (class "Default")
      (node (ref "D402") (pin "C") (pinfunction "C_C") (pintype "passive"))
      (node (ref "R402") (pin "1") (pinfunction "1_1") (pintype "passive"))
    )
    (net (code "106") (name "Net-(D403-PadC)") (class "Default")
      (node (ref "D403") (pin "C") (pinfunction "C_C") (pintype "passive"))
      (node (ref "R403") (pin "1") (pinfunction "1_1") (pintype "passive"))
    )
    (net (code "107") (name "Net-(D404-PadC)") (class "Default")
      (node (ref "D404") (pin "C") (pinfunction "C_C") (pintype "passive"))
      (node (ref "R404") (pin "1") (pinfunction "1_1") (pintype "passive"))
    )
    (net (code "108") (name "Net-(D405-PadC)") (class "Default")
      (node (ref "D405") (pin "C") (pinfunction "C_C") (pintype "passive"))
      (node (ref "R405") (pin "1") (pinfunction "1_1") (pintype "passive"))
    )
    (net (code "109") (name "Net-(D406-PadC)") (class "Default")
      (node (ref "D406") (pin "C") (pinfunction "C_C") (pintype "passive"))
      (node (ref "R406") (pin "1") (pinfunction "1_1") (pintype "passive"))
    )
    (net (code "110") (name "Net-(D407-PadC)") (class "Default")
      (node (ref "D407") (pin "C") (pinfunction "C_C") (pintype "passive"))
      (node (ref "R407") (pin "1") (pinfunction "1_1") (pintype "passive"))
    )
    (net (code "111") (name "Net-(D408-PadC)") (class "Default")
      (node (ref "D408") (pin "C") (pinfunction "C_C") (pintype "passive"))
      (node (ref "R408") (pin "1") (pinfunction "1_1") (pintype "passive"))
    )
    (net (code "112") (name "Net-(D409-PadC)") (class "Default")
      (node (ref "D409") (pin "C") (pinfunction "C_C") (pintype "passive"))
      (node (ref "R409") (pin "1") (pinfunction "1_1") (pintype "passive"))
    )
    (net (code "113") (name "Net-(D410-PadC)") (class "Default")
      (node (ref "D410") (pin "C") (pinfunction "C_C") (pintype "passive"))
      (node (ref "R410") (pin "1") (pinfunction "1_1") (pintype "passive"))
    )
    (net (code "114") (name "Net-(D411-PadC)") (class "Default")
      (node (ref "D411") (pin "C") (pinfunction "C_C") (pintype "passive"))
      (node (ref "R411") (pin "1") (pinfunction "1_1") (pintype "passive"))
    )
    (net (code "115") (name "Net-(D412-PadC)") (class "Default")
      (node (ref "D412") (pin "C") (pinfunction "C_C") (pintype "passive"))
      (node (ref "R412") (pin "1") (pinfunction "1_1") (pintype "passive"))
    )
    (net (code "116") (name "Net-(D413-PadC)") (class "Default")
      (node (ref "D413") (pin "C") (pinfunction "C_C") (pintype "passive"))
      (node (ref "R413") (pin "1") (pinfunction "1_1") (pintype "passive"))
    )
    (net (code "117") (name "Net-(D414-PadC)") (class "Default")
      (node (ref "D414") (pin "C") (pinfunction "C_C") (pintype "passive"))
      (node (ref "R414") (pin "1") (pinfunction "1_1") (pintype "passive"))
    )
    (net (code "118") (name "Net-(DIS301-DP1)") (class "Default")
      (node (ref "DIS301") (pin "18") (pinfunction "DP1_18") (pintype "passive"))
      (node (ref "TP301") (pin "1") (pinfunction "MP_1") (pintype "passive"))
    )
    (net (code "119") (name "Net-(DIS301-DP2)") (class "Default")
      (node (ref "DIS301") (pin "9") (pinfunction "DP2_9") (pintype "passive"))
      (node (ref "TP303") (pin "1") (pinfunction "MP_1") (pintype "passive"))
    )
    (net (code "120") (name "Net-(DIS302-DP1)") (class "Default")
      (node (ref "DIS302") (pin "18") (pinfunction "DP1_18") (pintype "passive"))
      (node (ref "TP302") (pin "1") (pinfunction "MP_1") (pintype "passive"))
    )
    (net (code "121") (name "Net-(DIS302-DP2)") (class "Default")
      (node (ref "DIS302") (pin "9") (pinfunction "DP2_9") (pintype "passive"))
      (node (ref "TP304") (pin "1") (pinfunction "MP_1") (pintype "passive"))
    )
    (net (code "122") (name "Net-(DIS303-DP1)") (class "Default")
      (node (ref "DIS303") (pin "18") (pinfunction "DP1_18") (pintype "passive"))
      (node (ref "TP305") (pin "1") (pinfunction "MP_1") (pintype "passive"))
    )
    (net (code "123") (name "Net-(DIS303-DP2)") (class "Default")
      (node (ref "DIS303") (pin "9") (pinfunction "DP2_9") (pintype "passive"))
      (node (ref "TP306") (pin "1") (pinfunction "MP_1") (pintype "passive"))
    )
    (net (code "124") (name "Net-(IC1201A-I0)") (class "Default")
      (node (ref "IC1201") (pin "1") (pinfunction "I0_1") (pintype "input"))
      (node (ref "IC1201") (pin "2") (pinfunction "I1_2") (pintype "input"))
      (node (ref "IC1201") (pin "4") (pinfunction "O_4") (pintype "output"))
      (node (ref "R1201") (pin "1") (pinfunction "1_1") (pintype "passive"))
    )
    (net (code "125") (name "Net-(IC1201B-I0)") (class "Default")
      (node (ref "C1201") (pin "1") (pinfunction "1_1") (pintype "passive"))
      (node (ref "IC1201") (pin "5") (pinfunction "I0_5") (pintype "input"))
      (node (ref "IC1201") (pin "6") (pinfunction "I1_6") (pintype "input"))
      (node (ref "R1201") (pin "2") (pinfunction "2_2") (pintype "passive"))
    )
    (net (code "126") (name "Net-(R1101-Pad1)") (class "Default")
      (node (ref "R1101") (pin "1") (pinfunction "1_1") (pintype "passive"))
      (node (ref "R1102") (pin "1") (pinfunction "1_1") (pintype "passive"))
      (node (ref "T1101") (pin "B") (pinfunction "B_B") (pintype "passive"))
    )
    (net (code "127") (name "PIO0") (class "Default")
      (node (ref "IC201") (pin "49") (pinfunction "PB06_14_49") (pintype "bidirectional"))
      (node (ref "RN902") (pin "6") (pinfunction "6_6") (pintype "passive"))
      (node (ref "X901") (pin "2") (pinfunction "2_2") (pintype "passive"))
    )
    (net (code "128") (name "PIO1") (class "Default")
      (node (ref "IC201") (pin "50") (pinfunction "PB08_01_50") (pintype "bidirectional"))
      (node (ref "RN902") (pin "5") (pinfunction "5_5") (pintype "passive"))
      (node (ref "X901") (pin "4") (pinfunction "4_4") (pintype "passive"))
    )
    (net (code "129") (name "PIO2") (class "Default")
      (node (ref "IC201") (pin "51") (pinfunction "PB08_02_51") (pintype "bidirectional"))
      (node (ref "RN902") (pin "2") (pinfunction "2_2") (pintype "passive"))
      (node (ref "X901") (pin "6") (pinfunction "6_6") (pintype "passive"))
    )
    (net (code "130") (name "PIO3") (class "Default")
      (node (ref "IC201") (pin "52") (pinfunction "PB08_04_52") (pintype "bidirectional"))
      (node (ref "RN902") (pin "3") (pinfunction "3_3") (pintype "passive"))
      (node (ref "X901") (pin "8") (pinfunction "8_8") (pintype "passive"))
    )
    (net (code "131") (name "PIO4") (class "Default")
      (node (ref "IC201") (pin "53") (pinfunction "PB08_05_53") (pintype "bidirectional"))
      (node (ref "RN902") (pin "4") (pinfunction "4_4") (pintype "passive"))
      (node (ref "X901") (pin "10") (pinfunction "10_10") (pintype "passive"))
    )
    (net (code "132") (name "PIO5") (class "Default")
      (node (ref "IC201") (pin "54") (pinfunction "PB08_07_54") (pintype "bidirectional"))
      (node (ref "RN902") (pin "7") (pinfunction "7_7") (pintype "passive"))
      (node (ref "X901") (pin "12") (pinfunction "12_12") (pintype "passive"))
    )
    (net (code "133") (name "PIO6") (class "Default")
      (node (ref "IC201") (pin "56") (pinfunction "PB08_10_56") (pintype "bidirectional"))
      (node (ref "RN902") (pin "8") (pinfunction "8_8") (pintype "passive"))
      (node (ref "X901") (pin "14") (pinfunction "14_14") (pintype "passive"))
    )
    (net (code "134") (name "PIO7") (class "Default")
      (node (ref "IC201") (pin "57") (pinfunction "PB08_11_57") (pintype "bidirectional"))
      (node (ref "RN902") (pin "9") (pinfunction "9_9") (pintype "passive"))
      (node (ref "X901") (pin "16") (pinfunction "16_16") (pintype "passive"))
    )
    (net (code "135") (name "RSV_100") (class "Default")
      (node (ref "R402") (pin "2") (pinfunction "2_2") (pintype "passive"))
      (node (ref "RN901") (pin "7") (pinfunction "7_7") (pintype "passive"))
      (node (ref "TP901") (pin "1") (pinfunction "MP_1") (pintype "passive"))
      (node (ref "X901") (pin "38") (pinfunction "38_38") (pintype "passive"))
    )
    (net (code "136") (name "RSV_300") (class "Default")
      (node (ref "IC201") (pin "66") (pinfunction "PB10_10_66") (pintype "bidirectional"))
      (node (ref "RN901") (pin "6") (pinfunction "6_6") (pintype "passive"))
      (node (ref "S904") (pin "7") (pinfunction "7_7") (pintype "passive"))
    )
    (net (code "137") (name "RSV_GCK2") (class "Default")
      (node (ref "IC201") (pin "32") (pinfunction "PB02_13_GCK2_32") (pintype "bidirectional"))
      (node (ref "RN901") (pin "5") (pinfunction "5_5") (pintype "passive"))
      (node (ref "S904") (pin "8") (pinfunction "8_8") (pintype "passive"))
      (node (ref "TP201") (pin "1") (pinfunction "MP_1") (pintype "passive"))
    )
    (net (code "138") (name "SEG0") (class "Default")
      (node (ref "IC201") (pin "87") (pinfunction "PB14_14_87") (pintype "bidirectional"))
      (node (ref "RN503") (pin "1") (pinfunction "1_1") (pintype "passive"))
    )
    (net (code "139") (name "SEG0_B") (class "Default")
      (node (ref "RN501") (pin "2") (pinfunction "2_2") (pintype "passive"))
      (node (ref "RN502") (pin "2") (pinfunction "2_2") (pintype "passive"))
      (node (ref "RN503") (pin "2") (pinfunction "2_2") (pintype "passive"))
      (node (ref "T501") (pin "B") (pinfunction "B_B") (pintype "passive"))
      (node (ref "T502") (pin "B") (pinfunction "B_B") (pintype "passive"))
    )
    (net (code "140") (name "SEG1") (class "Default")
      (node (ref "IC201") (pin "86") (pinfunction "PB14_13_86") (pintype "bidirectional"))
      (node (ref "RN503") (pin "3") (pinfunction "1_3") (pintype "passive"))
    )
    (net (code "141") (name "SEG1_B") (class "Default")
      (node (ref "RN501") (pin "3") (pinfunction "3_3") (pintype "passive"))
      (node (ref "RN502") (pin "3") (pinfunction "3_3") (pintype "passive"))
      (node (ref "RN503") (pin "4") (pinfunction "2_4") (pintype "passive"))
      (node (ref "T503") (pin "B") (pinfunction "B_B") (pintype "passive"))
      (node (ref "T504") (pin "B") (pinfunction "B_B") (pintype "passive"))
    )
    (net (code "142") (name "SEG2") (class "Default")
      (node (ref "IC201") (pin "85") (pinfunction "PB14_11_85") (pintype "bidirectional"))
      (node (ref "RN503") (pin "5") (pinfunction "1_5") (pintype "passive"))
    )
    (net (code "143") (name "SEG2_B") (class "Default")
      (node (ref "RN501") (pin "4") (pinfunction "4_4") (pintype "passive"))
      (node (ref "RN502") (pin "4") (pinfunction "4_4") (pintype "passive"))
      (node (ref "RN503") (pin "6") (pinfunction "2_6") (pintype "passive"))
      (node (ref "T505") (pin "B") (pinfunction "B_B") (pintype "passive"))
      (node (ref "T506") (pin "B") (pinfunction "B_B") (pintype "passive"))
    )
    (net (code "144") (name "SEG3") (class "Default")
      (node (ref "IC201") (pin "83") (pinfunction "PB14_10_83") (pintype "bidirectional"))
      (node (ref "RN503") (pin "7") (pinfunction "1_7") (pintype "passive"))
    )
    (net (code "145") (name "SEG3_B") (class "Default")
      (node (ref "RN501") (pin "5") (pinfunction "5_5") (pintype "passive"))
      (node (ref "RN502") (pin "5") (pinfunction "5_5") (pintype "passive"))
      (node (ref "RN503") (pin "8") (pinfunction "2_8") (pintype "passive"))
      (node (ref "T507") (pin "B") (pinfunction "B_B") (pintype "passive"))
      (node (ref "T508") (pin "B") (pinfunction "B_B") (pintype "passive"))
    )
    (net (code "146") (name "SEG4") (class "Default")
      (node (ref "IC201") (pin "82") (pinfunction "PB14_09_82") (pintype "bidirectional"))
      (node (ref "RN601") (pin "1") (pinfunction "1_1") (pintype "passive"))
    )
    (net (code "147") (name "SEG4_B") (class "Default")
      (node (ref "RN501") (pin "6") (pinfunction "6_6") (pintype "passive"))
      (node (ref "RN502") (pin "6") (pinfunction "6_6") (pintype "passive"))
      (node (ref "RN601") (pin "2") (pinfunction "2_2") (pintype "passive"))
      (node (ref "T601") (pin "B") (pinfunction "B_B") (pintype "passive"))
      (node (ref "T602") (pin "B") (pinfunction "B_B") (pintype "passive"))
    )
    (net (code "148") (name "SEG5") (class "Default")
      (node (ref "IC201") (pin "81") (pinfunction "PB14_07_81") (pintype "bidirectional"))
      (node (ref "RN601") (pin "3") (pinfunction "1_3") (pintype "passive"))
    )
    (net (code "149") (name "SEG5_B") (class "Default")
      (node (ref "RN501") (pin "7") (pinfunction "7_7") (pintype "passive"))
      (node (ref "RN502") (pin "7") (pinfunction "7_7") (pintype "passive"))
      (node (ref "RN601") (pin "4") (pinfunction "2_4") (pintype "passive"))
      (node (ref "T603") (pin "B") (pinfunction "B_B") (pintype "passive"))
      (node (ref "T604") (pin "B") (pinfunction "B_B") (pintype "passive"))
    )
    (net (code "150") (name "SEG6") (class "Default")
      (node (ref "IC201") (pin "80") (pinfunction "PB14_02_80") (pintype "bidirectional"))
      (node (ref "RN601") (pin "5") (pinfunction "1_5") (pintype "passive"))
    )
    (net (code "151") (name "SEG6_B") (class "Default")
      (node (ref "RN501") (pin "8") (pinfunction "8_8") (pintype "passive"))
      (node (ref "RN502") (pin "8") (pinfunction "8_8") (pintype "passive"))
      (node (ref "RN601") (pin "6") (pinfunction "2_6") (pintype "passive"))
      (node (ref "T605") (pin "B") (pinfunction "B_B") (pintype "passive"))
      (node (ref "T606") (pin "B") (pinfunction "B_B") (pintype "passive"))
    )
    (net (code "152") (name "SEG_DR0") (class "Default")
      (node (ref "R301") (pin "2") (pinfunction "2_2") (pintype "passive"))
      (node (ref "T501") (pin "C") (pinfunction "C_C") (pintype "passive"))
      (node (ref "T502") (pin "C") (pinfunction "C_C") (pintype "passive"))
    )
    (net (code "153") (name "SEG_DR1") (class "Default")
      (node (ref "R302") (pin "2") (pinfunction "2_2") (pintype "passive"))
      (node (ref "T503") (pin "C") (pinfunction "C_C") (pintype "passive"))
      (node (ref "T504") (pin "C") (pinfunction "C_C") (pintype "passive"))
    )
    (net (code "154") (name "SEG_DR2") (class "Default")
      (node (ref "R303") (pin "2") (pinfunction "2_2") (pintype "passive"))
      (node (ref "T505") (pin "C") (pinfunction "C_C") (pintype "passive"))
      (node (ref "T506") (pin "C") (pinfunction "C_C") (pintype "passive"))
    )
    (net (code "155") (name "SEG_DR3") (class "Default")
      (node (ref "R304") (pin "2") (pinfunction "2_2") (pintype "passive"))
      (node (ref "T507") (pin "C") (pinfunction "C_C") (pintype "passive"))
      (node (ref "T508") (pin "C") (pinfunction "C_C") (pintype "passive"))
    )
    (net (code "156") (name "SEG_DR4") (class "Default")
      (node (ref "R305") (pin "2") (pinfunction "2_2") (pintype "passive"))
      (node (ref "T601") (pin "C") (pinfunction "C_C") (pintype "passive"))
      (node (ref "T602") (pin "C") (pinfunction "C_C") (pintype "passive"))
    )
    (net (code "157") (name "SEG_DR5") (class "Default")
      (node (ref "R306") (pin "2") (pinfunction "2_2") (pintype "passive"))
      (node (ref "T603") (pin "C") (pinfunction "C_C") (pintype "passive"))
      (node (ref "T604") (pin "C") (pinfunction "C_C") (pintype "passive"))
    )
    (net (code "158") (name "SEG_DR6") (class "Default")
      (node (ref "R307") (pin "2") (pinfunction "2_2") (pintype "passive"))
      (node (ref "T605") (pin "C") (pinfunction "C_C") (pintype "passive"))
      (node (ref "T606") (pin "C") (pinfunction "C_C") (pintype "passive"))
    )
    (net (code "159") (name "SEG_R0") (class "Default")
      (node (ref "DIS301") (pin "11") (pinfunction "A2_11") (pintype "passive"))
      (node (ref "DIS301") (pin "16") (pinfunction "A1_16") (pintype "passive"))
      (node (ref "DIS302") (pin "11") (pinfunction "A2_11") (pintype "passive"))
      (node (ref "DIS302") (pin "16") (pinfunction "A1_16") (pintype "passive"))
      (node (ref "DIS303") (pin "11") (pinfunction "A2_11") (pintype "passive"))
      (node (ref "DIS303") (pin "16") (pinfunction "A1_16") (pintype "passive"))
      (node (ref "R301") (pin "1") (pinfunction "1_1") (pintype "passive"))
    )
    (net (code "160") (name "SEG_R1") (class "Default")
      (node (ref "DIS301") (pin "13") (pinfunction "B2_13") (pintype "passive"))
      (node (ref "DIS301") (pin "14") (pinfunction "B1_14") (pintype "passive"))
      (node (ref "DIS302") (pin "13") (pinfunction "B2_13") (pintype "passive"))
      (node (ref "DIS302") (pin "14") (pinfunction "B1_14") (pintype "passive"))
      (node (ref "DIS303") (pin "13") (pinfunction "B2_13") (pintype "passive"))
      (node (ref "DIS303") (pin "14") (pinfunction "B1_14") (pintype "passive"))
      (node (ref "R302") (pin "1") (pinfunction "1_1") (pintype "passive"))
    )
    (net (code "161") (name "SEG_R2") (class "Default")
      (node (ref "DIS301") (pin "1") (pinfunction "C1_1") (pintype "passive"))
      (node (ref "DIS301") (pin "8") (pinfunction "C2_8") (pintype "passive"))
      (node (ref "DIS302") (pin "1") (pinfunction "C1_1") (pintype "passive"))
      (node (ref "DIS302") (pin "8") (pinfunction "C2_8") (pintype "passive"))
      (node (ref "DIS303") (pin "1") (pinfunction "C1_1") (pintype "passive"))
      (node (ref "DIS303") (pin "8") (pinfunction "C2_8") (pintype "passive"))
      (node (ref "R303") (pin "1") (pinfunction "1_1") (pintype "passive"))
    )
    (net (code "162") (name "SEG_R3") (class "Default")
      (node (ref "DIS301") (pin "3") (pinfunction "D1_3") (pintype "passive"))
      (node (ref "DIS301") (pin "6") (pinfunction "D2_6") (pintype "passive"))
      (node (ref "DIS302") (pin "3") (pinfunction "D1_3") (pintype "passive"))
      (node (ref "DIS302") (pin "6") (pinfunction "D2_6") (pintype "passive"))
      (node (ref "DIS303") (pin "3") (pinfunction "D1_3") (pintype "passive"))
      (node (ref "DIS303") (pin "6") (pinfunction "D2_6") (pintype "passive"))
      (node (ref "R304") (pin "1") (pinfunction "1_1") (pintype "passive"))
    )
    (net (code "163") (name "SEG_R4") (class "Default")
      (node (ref "DIS301") (pin "2") (pinfunction "E1_2") (pintype "passive"))
      (node (ref "DIS301") (pin "7") (pinfunction "E2_7") (pintype "passive"))
      (node (ref "DIS302") (pin "2") (pinfunction "E1_2") (pintype "passive"))
      (node (ref "DIS302") (pin "7") (pinfunction "E2_7") (pintype "passive"))
      (node (ref "DIS303") (pin "2") (pinfunction "E1_2") (pintype "passive"))
      (node (ref "DIS303") (pin "7") (pinfunction "E2_7") (pintype "passive"))
      (node (ref "R305") (pin "1") (pinfunction "1_1") (pintype "passive"))
    )
    (net (code "164") (name "SEG_R5") (class "Default")
      (node (ref "DIS301") (pin "12") (pinfunction "F2_12") (pintype "passive"))
      (node (ref "DIS301") (pin "15") (pinfunction "F1_15") (pintype "passive"))
      (node (ref "DIS302") (pin "12") (pinfunction "F2_12") (pintype "passive"))
      (node (ref "DIS302") (pin "15") (pinfunction "F1_15") (pintype "passive"))
      (node (ref "DIS303") (pin "12") (pinfunction "F2_12") (pintype "passive"))
      (node (ref "DIS303") (pin "15") (pinfunction "F1_15") (pintype "passive"))
      (node (ref "R306") (pin "1") (pinfunction "1_1") (pintype "passive"))
    )
    (net (code "165") (name "SEG_R6") (class "Default")
      (node (ref "DIS301") (pin "10") (pinfunction "G2_10") (pintype "passive"))
      (node (ref "DIS301") (pin "17") (pinfunction "G1_17") (pintype "passive"))
      (node (ref "DIS302") (pin "10") (pinfunction "G2_10") (pintype "passive"))
      (node (ref "DIS302") (pin "17") (pinfunction "G1_17") (pintype "passive"))
      (node (ref "DIS303") (pin "10") (pinfunction "G2_10") (pintype "passive"))
      (node (ref "DIS303") (pin "17") (pinfunction "G1_17") (pintype "passive"))
      (node (ref "R307") (pin "1") (pinfunction "1_1") (pintype "passive"))
    )
    (net (code "166") (name "ST_IN0") (class "Default")
      (node (ref "IC1201") (pin "8") (pinfunction "I0_8") (pintype "input"))
      (node (ref "IC1201") (pin "9") (pinfunction "I1_9") (pintype "input"))
      (node (ref "RN901") (pin "8") (pinfunction "8_8") (pintype "passive"))
      (node (ref "TP1204") (pin "1") (pinfunction "MP_1") (pintype "passive"))
      (node (ref "X901") (pin "20") (pinfunction "20_20") (pintype "passive"))
    )
    (net (code "167") (name "ST_IN1") (class "Default")
      (node (ref "IC1201") (pin "12") (pinfunction "I0_12") (pintype "input"))
      (node (ref "IC1201") (pin "13") (pinfunction "I1_13") (pintype "input"))
      (node (ref "RN901") (pin "9") (pinfunction "9_9") (pintype "passive"))
      (node (ref "TP1205") (pin "1") (pinfunction "MP_1") (pintype "passive"))
      (node (ref "X901") (pin "22") (pinfunction "22_22") (pintype "passive"))
    )
    (net (code "168") (name "ST_OUT0") (class "Default")
      (node (ref "IC1201") (pin "10") (pinfunction "O_10") (pintype "output"))
      (node (ref "TP1202") (pin "1") (pinfunction "MP_1") (pintype "passive"))
      (node (ref "X901") (pin "32") (pinfunction "32_32") (pintype "passive"))
    )
    (net (code "169") (name "ST_OUT1") (class "Default")
      (node (ref "IC1201") (pin "11") (pinfunction "O_11") (pintype "output"))
      (node (ref "TP1203") (pin "1") (pinfunction "MP_1") (pintype "passive"))
      (node (ref "X901") (pin "34") (pinfunction "34_34") (pintype "passive"))
    )
    (net (code "170") (name "SWITCH0") (class "Default")
      (node (ref "IC201") (pin "70") (pinfunction "PB10_16_70") (pintype "bidirectional"))
      (node (ref "RN901") (pin "2") (pinfunction "2_2") (pintype "passive"))
      (node (ref "S903") (pin "1") (pinfunction "A1_1") (pintype "passive"))
      (node (ref "S903") (pin "3") (pinfunction "A1_3") (pintype "passive"))
      (node (ref "S904") (pin "1") (pinfunction "1_1") (pintype "passive"))
    )
    (net (code "171") (name "SWITCH1") (class "Default")
      (node (ref "IC201") (pin "69") (pinfunction "PB10_13_69") (pintype "bidirectional"))
      (node (ref "RN901") (pin "3") (pinfunction "3_3") (pintype "passive"))
      (node (ref "S902") (pin "1") (pinfunction "A1_1") (pintype "passive"))
      (node (ref "S902") (pin "3") (pinfunction "A1_3") (pintype "passive"))
      (node (ref "S904") (pin "2") (pinfunction "2_2") (pintype "passive"))
    )
    (net (code "172") (name "SWITCH2") (class "Default")
      (node (ref "IC201") (pin "68") (pinfunction "PB10_11_68") (pintype "bidirectional"))
      (node (ref "RN901") (pin "4") (pinfunction "4_4") (pintype "passive"))
      (node (ref "S901") (pin "1") (pinfunction "A1_1") (pintype "passive"))
      (node (ref "S901") (pin "3") (pinfunction "A1_3") (pintype "passive"))
      (node (ref "S904") (pin "3") (pinfunction "3_3") (pintype "passive"))
    )
    (net (code "173") (name "TCK") (class "Default")
      (node (ref "IC201") (pin "67") (pinfunction "TCK_67") (pintype "input"))
      (node (ref "R1001") (pin "1") (pinfunction "1_1") (pintype "passive"))
      (node (ref "TP1001") (pin "1") (pinfunction "MP_1") (pintype "passive"))
      (node (ref "X1001") (pin "1") (pinfunction "1_1") (pintype "passive"))
    )
    (net (code "174") (name "TDI") (class "Default")
      (node (ref "IC201") (pin "63") (pinfunction "TDI_63") (pintype "input"))
      (node (ref "RN1001") (pin "3") (pinfunction "3_3") (pintype "passive"))
      (node (ref "TP1004") (pin "1") (pinfunction "MP_1") (pintype "passive"))
      (node (ref "X1001") (pin "7") (pinfunction "7_7") (pintype "passive"))
    )
    (net (code "175") (name "TDO") (class "Default")
      (node (ref "IC201") (pin "122") (pinfunction "TDO_122") (pintype "output"))
      (node (ref "RN1001") (pin "4") (pinfunction "4_4") (pintype "passive"))
      (node (ref "TP1003") (pin "1") (pinfunction "MP_1") (pintype "passive"))
      (node (ref "X1001") (pin "5") (pinfunction "5_5") (pintype "passive"))
    )
    (net (code "176") (name "TMS") (class "Default")
      (node (ref "IC201") (pin "65") (pinfunction "TMS_65") (pintype "input"))
      (node (ref "R1002") (pin "1") (pinfunction "1_1") (pintype "passive"))
      (node (ref "TP1002") (pin "1") (pinfunction "MP_1") (pintype "passive"))
      (node (ref "X1001") (pin "3") (pinfunction "3_3") (pintype "passive"))
    )
    (net (code "177") (name "VREF_JTAG") (class "Default")
      (node (ref "J1001") (pin "2") (pinfunction "2_2") (pintype "passive"))
      (node (ref "X1001") (pin "10") (pinfunction "10_10") (pintype "passive"))
    )
    (net (code "178") (name "unconnected-(FD101-NC-Pad1)") (class "Default")
      (node (ref "FD101") (pin "1") (pinfunction "NC_1") (pintype "no_connect"))
    )
    (net (code "179") (name "unconnected-(FD102-NC-Pad1)") (class "Default")
      (node (ref "FD102") (pin "1") (pinfunction "NC_1") (pintype "no_connect"))
    )
    (net (code "180") (name "unconnected-(RN501-Pad9)") (class "Default")
      (node (ref "RN501") (pin "9") (pinfunction "9_9") (pintype "passive"))
    )
    (net (code "181") (name "unconnected-(RN502-Pad9)") (class "Default")
      (node (ref "RN502") (pin "9") (pinfunction "9_9") (pintype "passive"))
    )
    (net (code "182") (name "unconnected-(RN801-Pad8)") (class "Default")
      (node (ref "RN801") (pin "8") (pinfunction "8_8") (pintype "passive"))
    )
    (net (code "183") (name "unconnected-(RN801-Pad9)") (class "Default")
      (node (ref "RN801") (pin "9") (pinfunction "9_9") (pintype "passive"))
    )
    (net (code "184") (name "unconnected-(RN802-Pad8)") (class "Default")
      (node (ref "RN802") (pin "8") (pinfunction "8_8") (pintype "passive"))
    )
    (net (code "185") (name "unconnected-(RN802-Pad9)") (class "Default")
      (node (ref "RN802") (pin "9") (pinfunction "9_9") (pintype "passive"))
    )
    (net (code "186") (name "unconnected-(RN1001-Pad2)") (class "Default")
      (node (ref "RN1001") (pin "2") (pinfunction "2_2") (pintype "passive"))
    )
    (net (code "187") (name "unconnected-(RN1001-Pad5)") (class "Default")
      (node (ref "RN1001") (pin "5") (pinfunction "5_5") (pintype "passive"))
    )
    (net (code "188") (name "unconnected-(RN1001-Pad6)") (class "Default")
      (node (ref "RN1001") (pin "6") (pinfunction "6_6") (pintype "passive"))
    )
    (net (code "189") (name "unconnected-(RN1001-Pad7)") (class "Default")
      (node (ref "RN1001") (pin "7") (pinfunction "7_7") (pintype "passive"))
    )
    (net (code "190") (name "unconnected-(RN1001-Pad8)") (class "Default")
      (node (ref "RN1001") (pin "8") (pinfunction "8_8") (pintype "passive"))
    )
    (net (code "191") (name "unconnected-(RN1001-Pad9)") (class "Default")
      (node (ref "RN1001") (pin "9") (pinfunction "9_9") (pintype "passive"))
    )
    (net (code "192") (name "unconnected-(TP111-MP-Pad1)") (class "Default")
      (node (ref "TP111") (pin "1") (pinfunction "MP_1") (pintype "passive"))
    )
    (net (code "193") (name "unconnected-(TP112-MP-Pad1)") (class "Default")
      (node (ref "TP112") (pin "1") (pinfunction "MP_1") (pintype "passive"))
    )
    (net (code "194") (name "unconnected-(TP113-MP-Pad1)") (class "Default")
      (node (ref "TP113") (pin "1") (pinfunction "MP_1") (pintype "passive"))
    )
    (net (code "195") (name "unconnected-(TP114-MP-Pad1)") (class "Default")
      (node (ref "TP114") (pin "1") (pinfunction "MP_1") (pintype "passive"))
    )
    (net (code "196") (name "unconnected-(TP118-MP-Pad1)") (class "Default")
      (node (ref "TP118") (pin "1") (pinfunction "MP_1") (pintype "passive"))
    )
    (net (code "197") (name "unconnected-(TP119-MP-Pad1)") (class "Default")
      (node (ref "TP119") (pin "1") (pinfunction "MP_1") (pintype "passive"))
    )
    (net (code "198") (name "unconnected-(TP120-MP-Pad1)") (class "Default")
      (node (ref "TP120") (pin "1") (pinfunction "MP_1") (pintype "passive"))
    )
    (net (code "199") (name "unconnected-(TP121-MP-Pad1)") (class "Default")
      (node (ref "TP121") (pin "1") (pinfunction "MP_1") (pintype "passive"))
    )
    (net (code "200") (name "unconnected-(TP122-MP-Pad1)") (class "Default")
      (node (ref "TP122") (pin "1") (pinfunction "MP_1") (pintype "passive"))
    )
    (net (code "201") (name "unconnected-(TP123-MP-Pad1)") (class "Default")
      (node (ref "TP123") (pin "1") (pinfunction "MP_1") (pintype "passive"))
    )
    (net (code "202") (name "unconnected-(TP124-MP-Pad1)") (class "Default")
      (node (ref "TP124") (pin "1") (pinfunction "MP_1") (pintype "passive"))
    )
    (net (code "203") (name "unconnected-(TP125-MP-Pad1)") (class "Default")
      (node (ref "TP125") (pin "1") (pinfunction "MP_1") (pintype "passive"))
    )
    (net (code "204") (name "unconnected-(TP126-MP-Pad1)") (class "Default")
      (node (ref "TP126") (pin "1") (pinfunction "MP_1") (pintype "passive"))
    )
    (net (code "205") (name "unconnected-(TP130-MP-Pad1)") (class "Default")
      (node (ref "TP130") (pin "1") (pinfunction "MP_1") (pintype "passive"))
    )
    (net (code "206") (name "unconnected-(TP131-MP-Pad1)") (class "Default")
      (node (ref "TP131") (pin "1") (pinfunction "MP_1") (pintype "passive"))
    )
    (net (code "207") (name "unconnected-(TP132-MP-Pad1)") (class "Default")
      (node (ref "TP132") (pin "1") (pinfunction "MP_1") (pintype "passive"))
    )
    (net (code "208") (name "unconnected-(TP133-MP-Pad1)") (class "Default")
      (node (ref "TP133") (pin "1") (pinfunction "MP_1") (pintype "passive"))
    )
    (net (code "209") (name "unconnected-(TP134-MP-Pad1)") (class "Default")
      (node (ref "TP134") (pin "1") (pinfunction "MP_1") (pintype "passive"))
    )
    (net (code "210") (name "unconnected-(TP135-MP-Pad1)") (class "Default")
      (node (ref "TP135") (pin "1") (pinfunction "MP_1") (pintype "passive"))
    )
    (net (code "211") (name "unconnected-(TP136-MP-Pad1)") (class "Default")
      (node (ref "TP136") (pin "1") (pinfunction "MP_1") (pintype "passive"))
    )
    (net (code "212") (name "unconnected-(X901-Pad7)") (class "Default")
      (node (ref "X901") (pin "7") (pinfunction "7_7") (pintype "passive"))
    )
    (net (code "213") (name "unconnected-(X1001-Pad9)") (class "Default")
      (node (ref "X1001") (pin "9") (pinfunction "9_9") (pintype "passive"))
    )
    (net (code "214") (name "unconnected-(X1103-Pad18)") (class "Default")
      (node (ref "X1103") (pin "18") (pinfunction "18_18") (pintype "passive"))
    )
    (net (code "215") (name "~{CPU_BUSACK}") (class "Default")
      (node (ref "IC201") (pin "45") (pinfunction "PB06_02_45") (pintype "bidirectional"))
      (node (ref "X1101") (pin "38") (pinfunction "38_38") (pintype "passive"))
    )
    (net (code "216") (name "~{CPU_BUSREQ}") (class "Default")
      (node (ref "IC201") (pin "43") (pinfunction "PB04_14_43") (pintype "bidirectional"))
      (node (ref "X1101") (pin "36") (pinfunction "36_36") (pintype "passive"))
    )
    (net (code "217") (name "~{CPU_HALT}") (class "Default")
      (node (ref "IC201") (pin "40") (pinfunction "PB04_11_40") (pintype "bidirectional"))
      (node (ref "X1101") (pin "32") (pinfunction "32_32") (pintype "passive"))
    )
    (net (code "218") (name "~{CPU_INT}") (class "Default")
      (node (ref "IC201") (pin "44") (pinfunction "PB04_16_44") (pintype "bidirectional"))
      (node (ref "X1102") (pin "36") (pinfunction "36_36") (pintype "passive"))
    )
    (net (code "219") (name "~{CPU_IOREQ}") (class "Default")
      (node (ref "IC201") (pin "35") (pinfunction "PB04_04_35") (pintype "bidirectional"))
      (node (ref "X1101") (pin "24") (pinfunction "24_24") (pintype "passive"))
    )
    (net (code "220") (name "~{CPU_M1}") (class "Default")
      (node (ref "IC201") (pin "28") (pinfunction "PB02_01_28") (pintype "bidirectional"))
      (node (ref "X1101") (pin "20") (pinfunction "20_20") (pintype "passive"))
    )
    (net (code "221") (name "~{CPU_MREQ}") (class "Default")
      (node (ref "IC201") (pin "31") (pinfunction "PB02_11_31") (pintype "bidirectional"))
      (node (ref "X1101") (pin "22") (pinfunction "22_22") (pintype "passive"))
    )
    (net (code "222") (name "~{CPU_NMI}") (class "Default")
      (node (ref "IC201") (pin "48") (pinfunction "PB06_11_48") (pintype "bidirectional"))
      (node (ref "X1102") (pin "38") (pinfunction "38_38") (pintype "passive"))
    )
    (net (code "223") (name "~{CPU_RD}") (class "Default")
      (node (ref "IC201") (pin "33") (pinfunction "PB02_14_33") (pintype "bidirectional"))
      (node (ref "X1101") (pin "26") (pinfunction "26_26") (pintype "passive"))
    )
    (net (code "224") (name "~{CPU_RESET}") (class "Default")
      (node (ref "R1103") (pin "2") (pinfunction "2_2") (pintype "passive"))
      (node (ref "R404") (pin "2") (pinfunction "2_2") (pintype "passive"))
      (node (ref "T1101") (pin "C") (pinfunction "C_C") (pintype "passive"))
      (node (ref "TP1101") (pin "1") (pinfunction "MP_1") (pintype "passive"))
      (node (ref "TP1102") (pin "1") (pinfunction "MP_1") (pintype "passive"))
      (node (ref "X1102") (pin "40") (pinfunction "40_40") (pintype "passive"))
      (node (ref "X901") (pin "40") (pinfunction "40_40") (pintype "passive"))
    )
    (net (code "225") (name "~{CPU_RFSH}") (class "Default")
      (node (ref "IC201") (pin "39") (pinfunction "PB04_09_39") (pintype "bidirectional"))
      (node (ref "X1101") (pin "30") (pinfunction "30_30") (pintype "passive"))
    )
    (net (code "226") (name "~{CPU_WAIT}") (class "Default")
      (node (ref "IC201") (pin "41") (pinfunction "PB04_13_41") (pintype "bidirectional"))
      (node (ref "X1101") (pin "34") (pinfunction "34_34") (pintype "passive"))
    )
    (net (code "227") (name "~{CPU_WR}") (class "Default")
      (node (ref "IC201") (pin "34") (pinfunction "PB04_01_34") (pintype "bidirectional"))
      (node (ref "X1101") (pin "28") (pinfunction "28_28") (pintype "passive"))
    )
    (net (code "228") (name "~{EX_BUSAK}") (class "Default")
      (node (ref "IC201") (pin "98") (pinfunction "PB15_11_98") (pintype "bidirectional"))
      (node (ref "X1103") (pin "38") (pinfunction "38_38") (pintype "passive"))
    )
    (net (code "229") (name "~{EX_BUSREQ}") (class "Default")
      (node (ref "IC201") (pin "100") (pinfunction "PB13_02_100") (pintype "bidirectional"))
      (node (ref "X1103") (pin "36") (pinfunction "36_36") (pintype "passive"))
    )
    (net (code "230") (name "~{EX_HALT}") (class "Default")
      (node (ref "IC201") (pin "102") (pinfunction "PB13_05_102") (pintype "bidirectional"))
      (node (ref "X1103") (pin "32") (pinfunction "32_32") (pintype "passive"))
    )
    (net (code "231") (name "~{EX_INT}") (class "Default")
      (node (ref "IC201") (pin "112") (pinfunction "PB11_04_112") (pintype "bidirectional"))
      (node (ref "X1104") (pin "36") (pinfunction "36_36") (pintype "passive"))
    )
    (net (code "232") (name "~{EX_IOREQ}") (class "Default")
      (node (ref "IC201") (pin "106") (pinfunction "PB13_13_106") (pintype "bidirectional"))
      (node (ref "X1103") (pin "24") (pinfunction "24_24") (pintype "passive"))
    )
    (net (code "233") (name "~{EX_M1}") (class "Default")
      (node (ref "IC201") (pin "96") (pinfunction "PB15_09_96") (pintype "bidirectional"))
      (node (ref "X1103") (pin "20") (pinfunction "20_20") (pintype "passive"))
    )
    (net (code "234") (name "~{EX_MREQ}") (class "Default")
      (node (ref "IC201") (pin "107") (pinfunction "PB13_14_107") (pintype "bidirectional"))
      (node (ref "X1103") (pin "22") (pinfunction "22_22") (pintype "passive"))
    )
    (net (code "235") (name "~{EX_NMI}") (class "Default")
      (node (ref "IC201") (pin "111") (pinfunction "PB11_02_111") (pintype "bidirectional"))
      (node (ref "X1104") (pin "38") (pinfunction "38_38") (pintype "passive"))
    )
    (net (code "236") (name "~{EX_RD}") (class "Default")
      (node (ref "IC201") (pin "105") (pinfunction "PB13_10_105") (pintype "bidirectional"))
      (node (ref "X1103") (pin "26") (pinfunction "26_26") (pintype "passive"))
    )
    (net (code "237") (name "~{EX_RESET}") (class "Default")
      (node (ref "IC201") (pin "110") (pinfunction "PB11_01_110") (pintype "bidirectional"))
      (node (ref "R1104") (pin "2") (pinfunction "2_2") (pintype "passive"))
      (node (ref "TP1103") (pin "1") (pinfunction "MP_1") (pintype "passive"))
      (node (ref "X1104") (pin "40") (pinfunction "40_40") (pintype "passive"))
    )
    (net (code "238") (name "~{EX_RFSH}") (class "Default")
      (node (ref "IC201") (pin "103") (pinfunction "PB13_07_103") (pintype "bidirectional"))
      (node (ref "X1103") (pin "30") (pinfunction "30_30") (pintype "passive"))
    )
    (net (code "239") (name "~{EX_WAIT}") (class "Default")
      (node (ref "IC201") (pin "101") (pinfunction "PB13_04_101") (pintype "bidirectional"))
      (node (ref "X1103") (pin "34") (pinfunction "34_34") (pintype "passive"))
    )
    (net (code "240") (name "~{EX_WR}") (class "Default")
      (node (ref "IC201") (pin "104") (pinfunction "PB13_09_104") (pintype "bidirectional"))
      (node (ref "X1103") (pin "28") (pinfunction "28_28") (pintype "passive"))
    )
  )
)
